# STM32-PROX.net
KiCad netlist of a schematic drawn in EAGLE
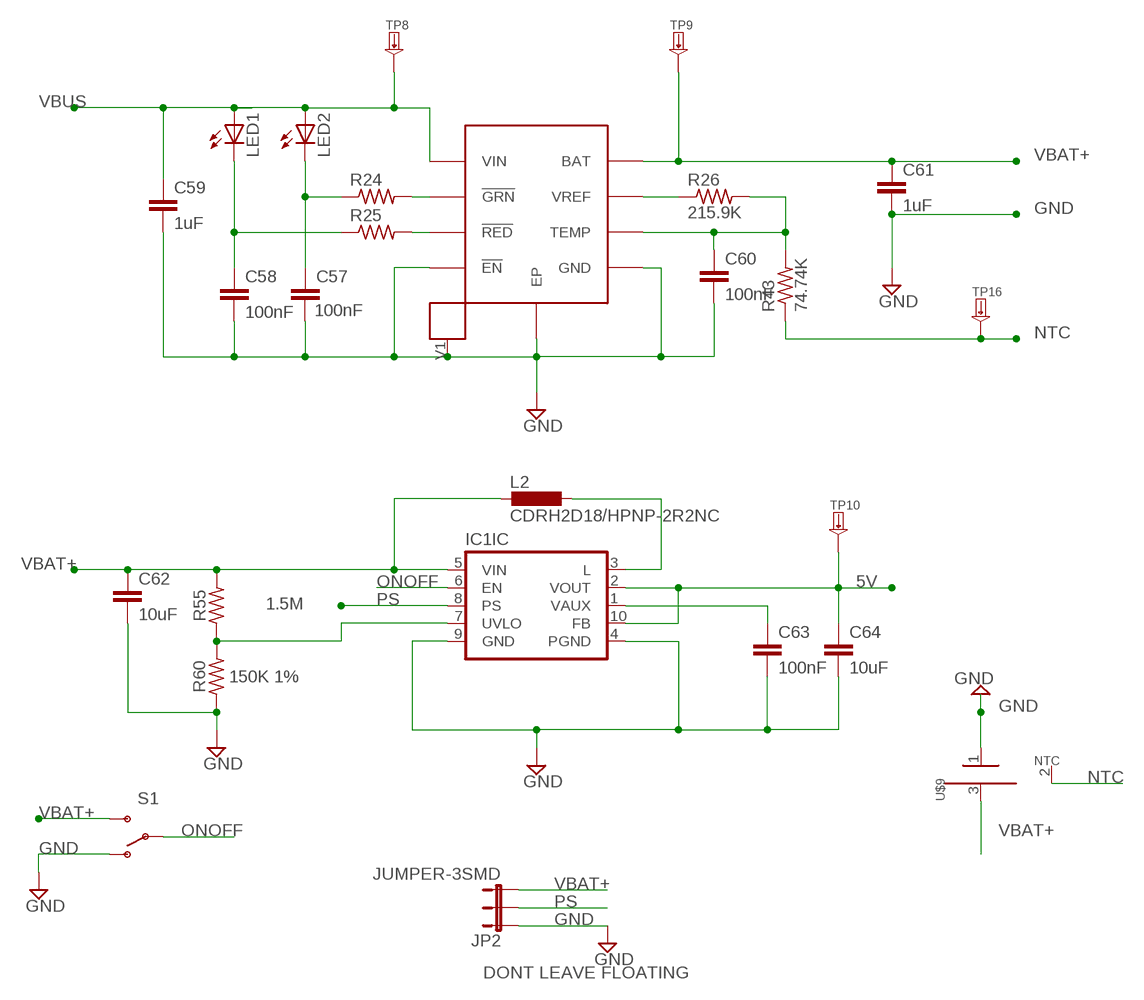
[diagram p0: schematic, sheet 1]
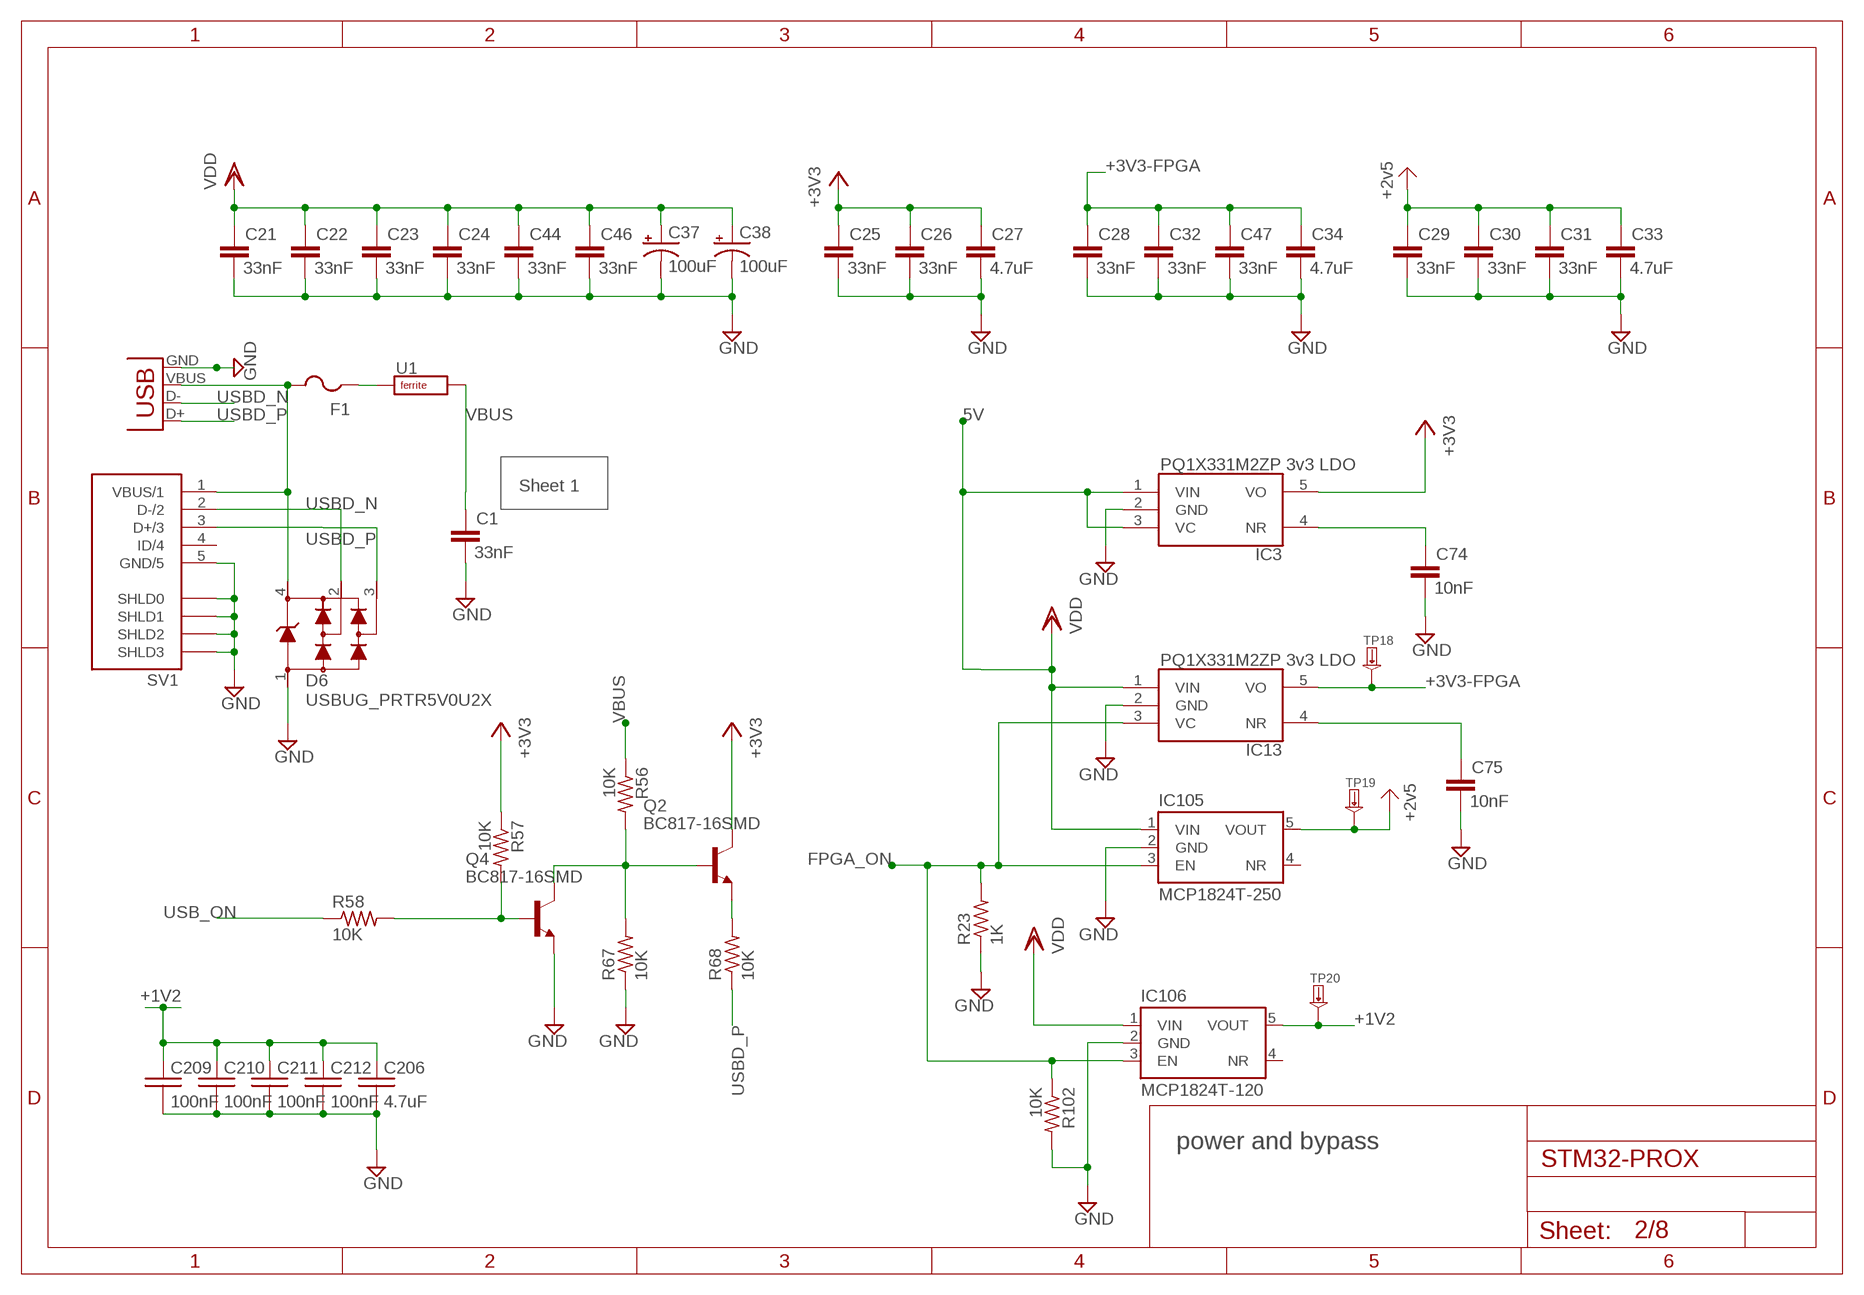
[diagram p1: schematic, sheet 2]
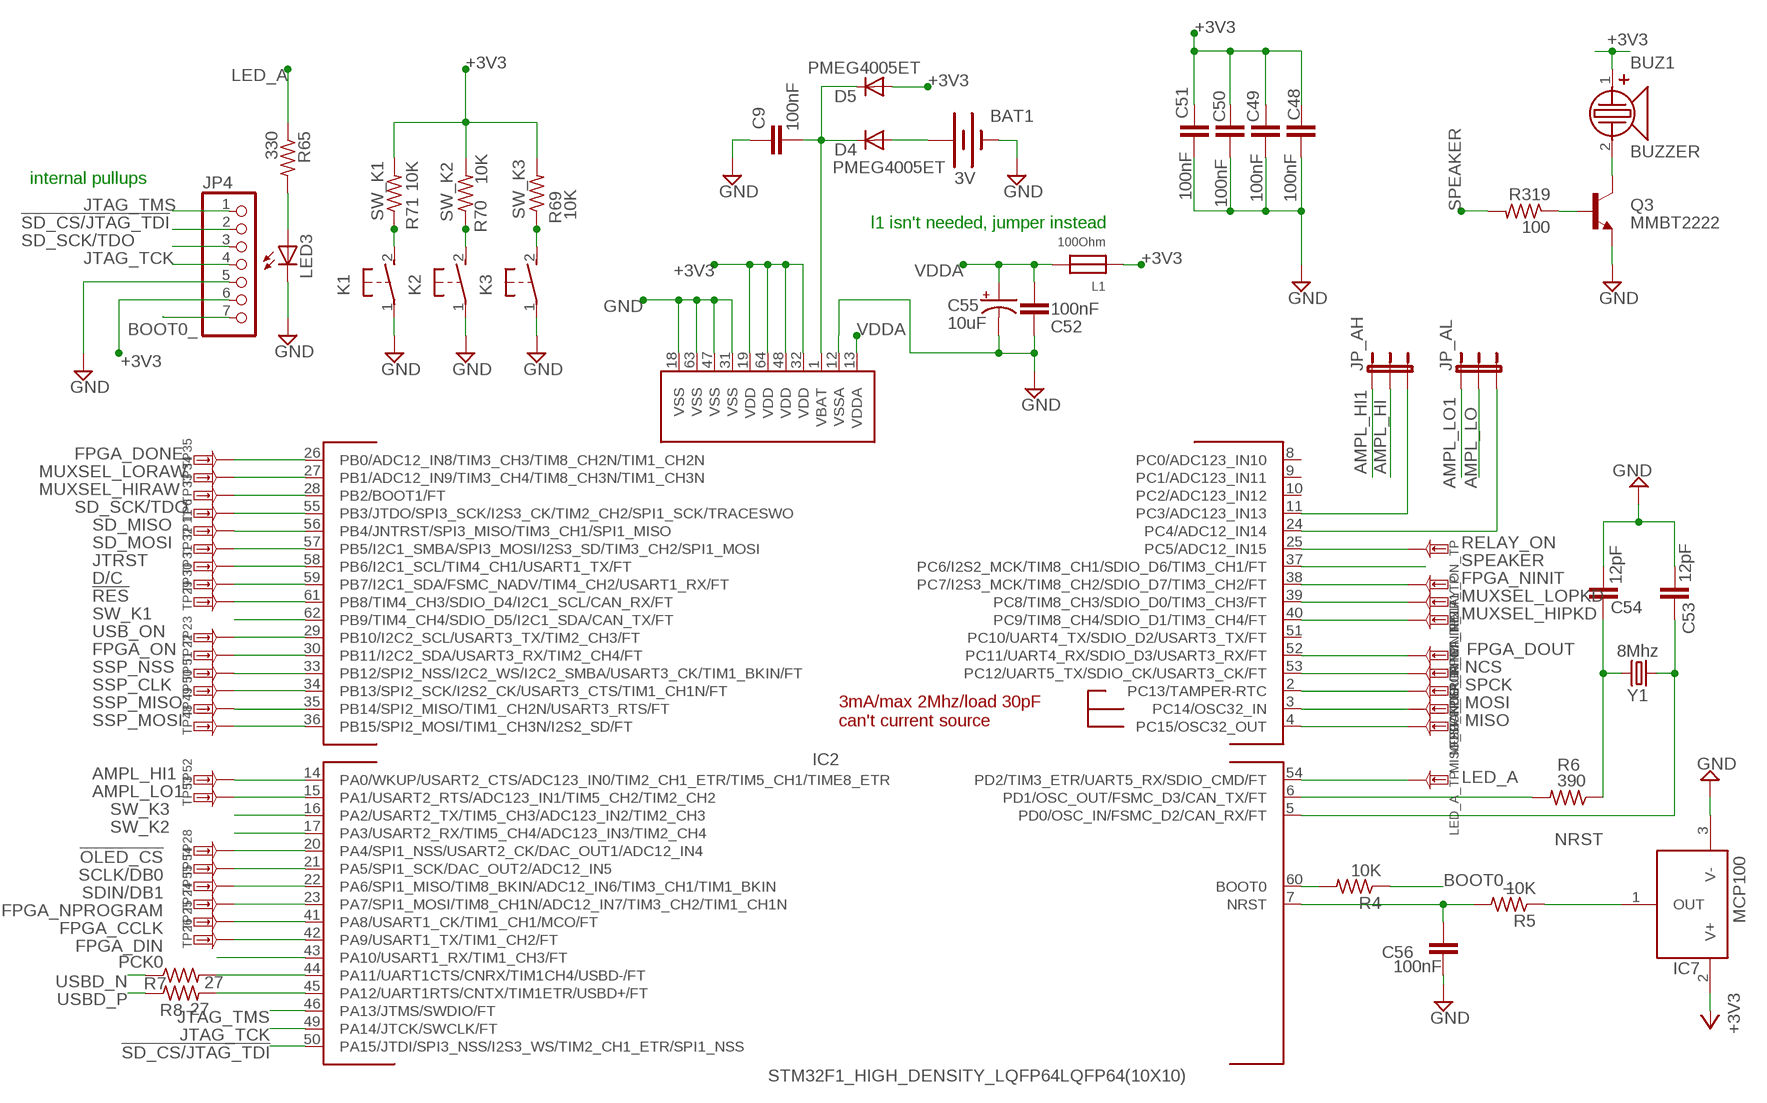
[diagram p2: schematic, sheet 3]
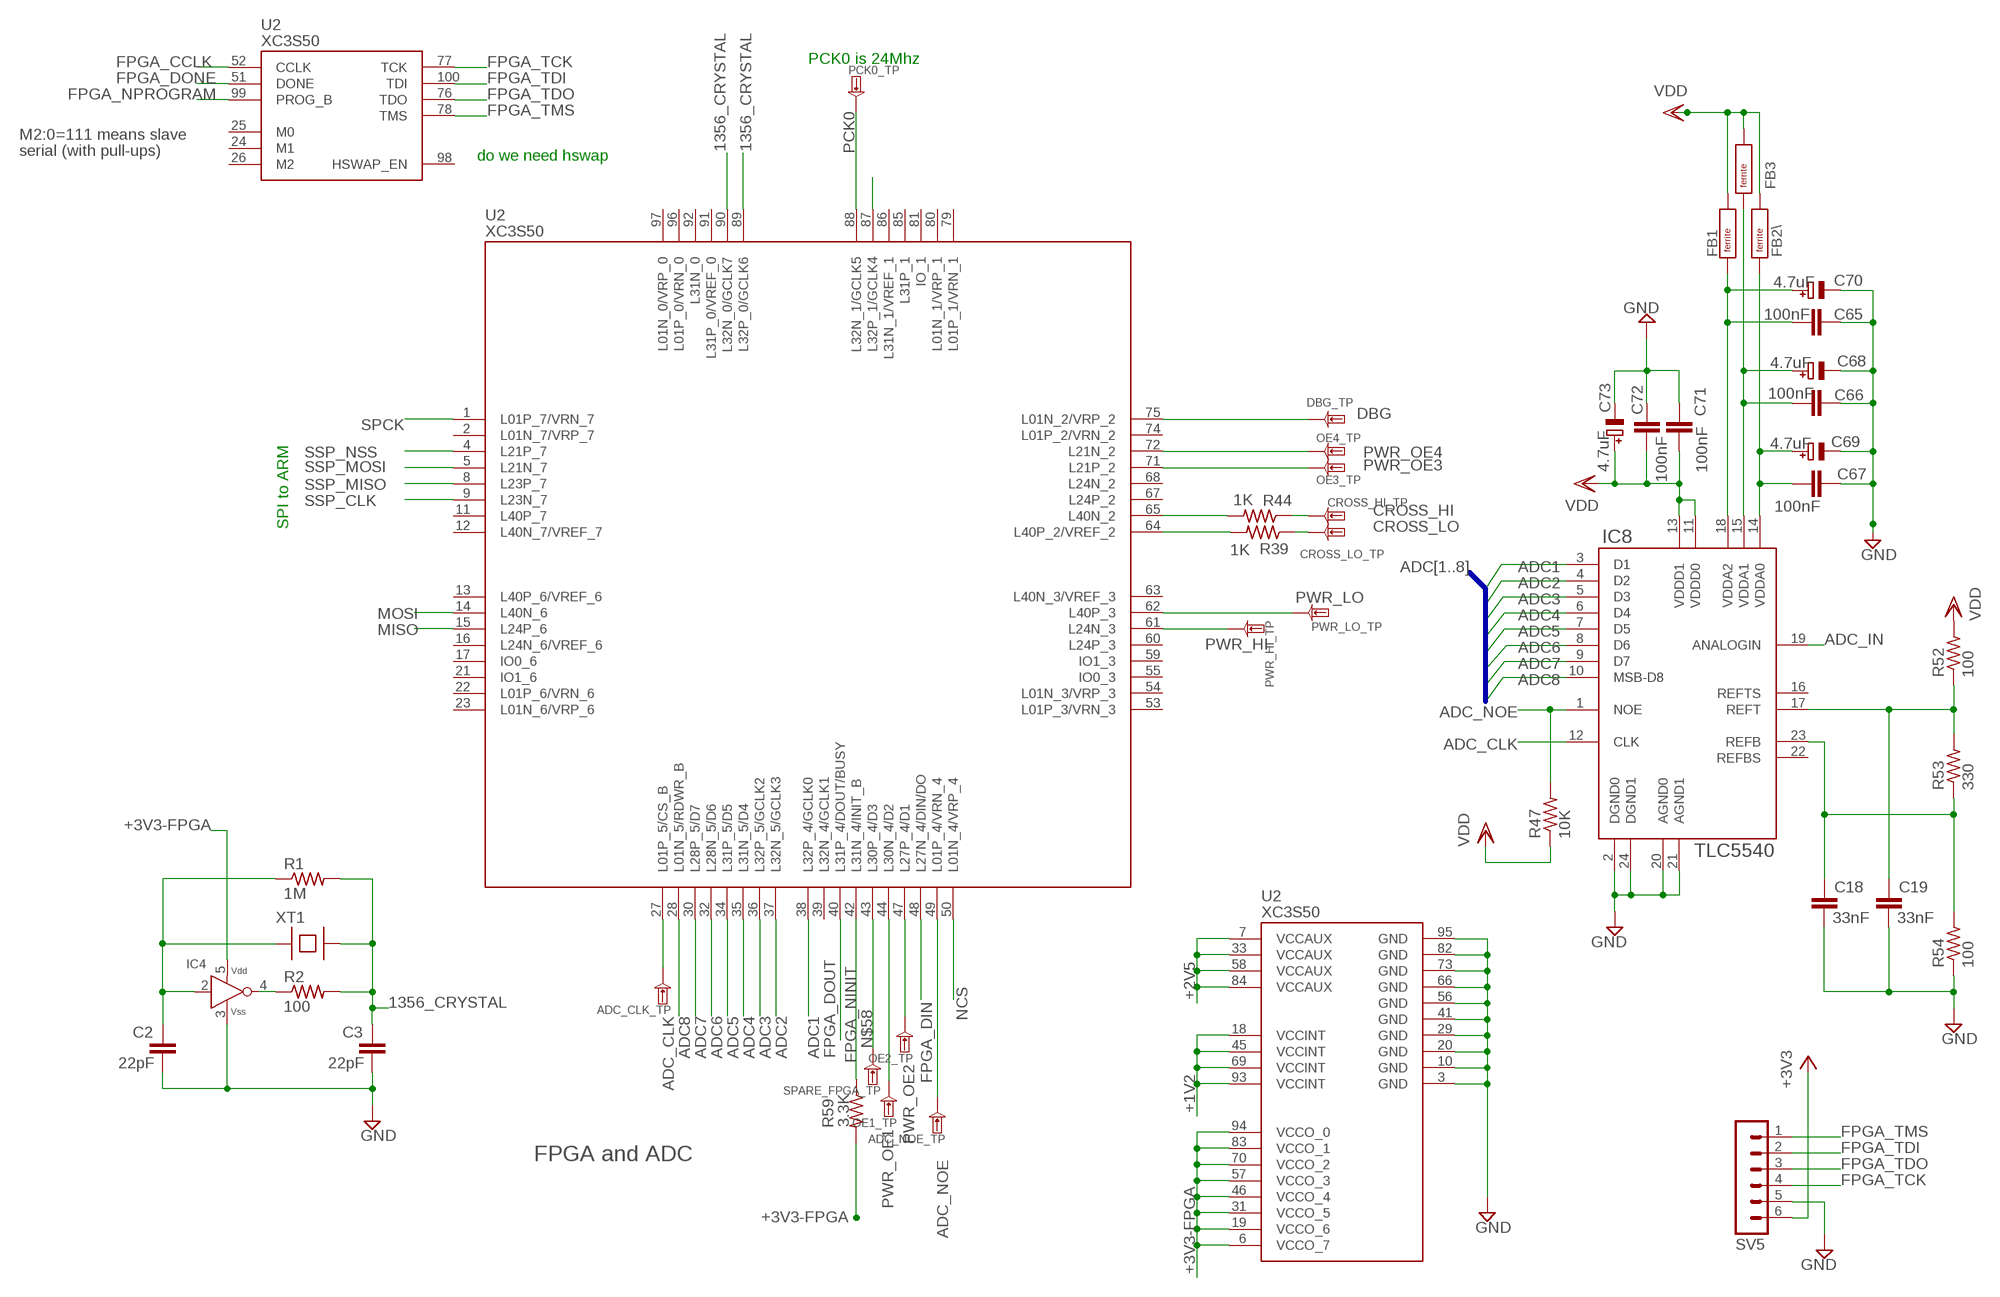
[diagram p3: schematic, sheet 4]
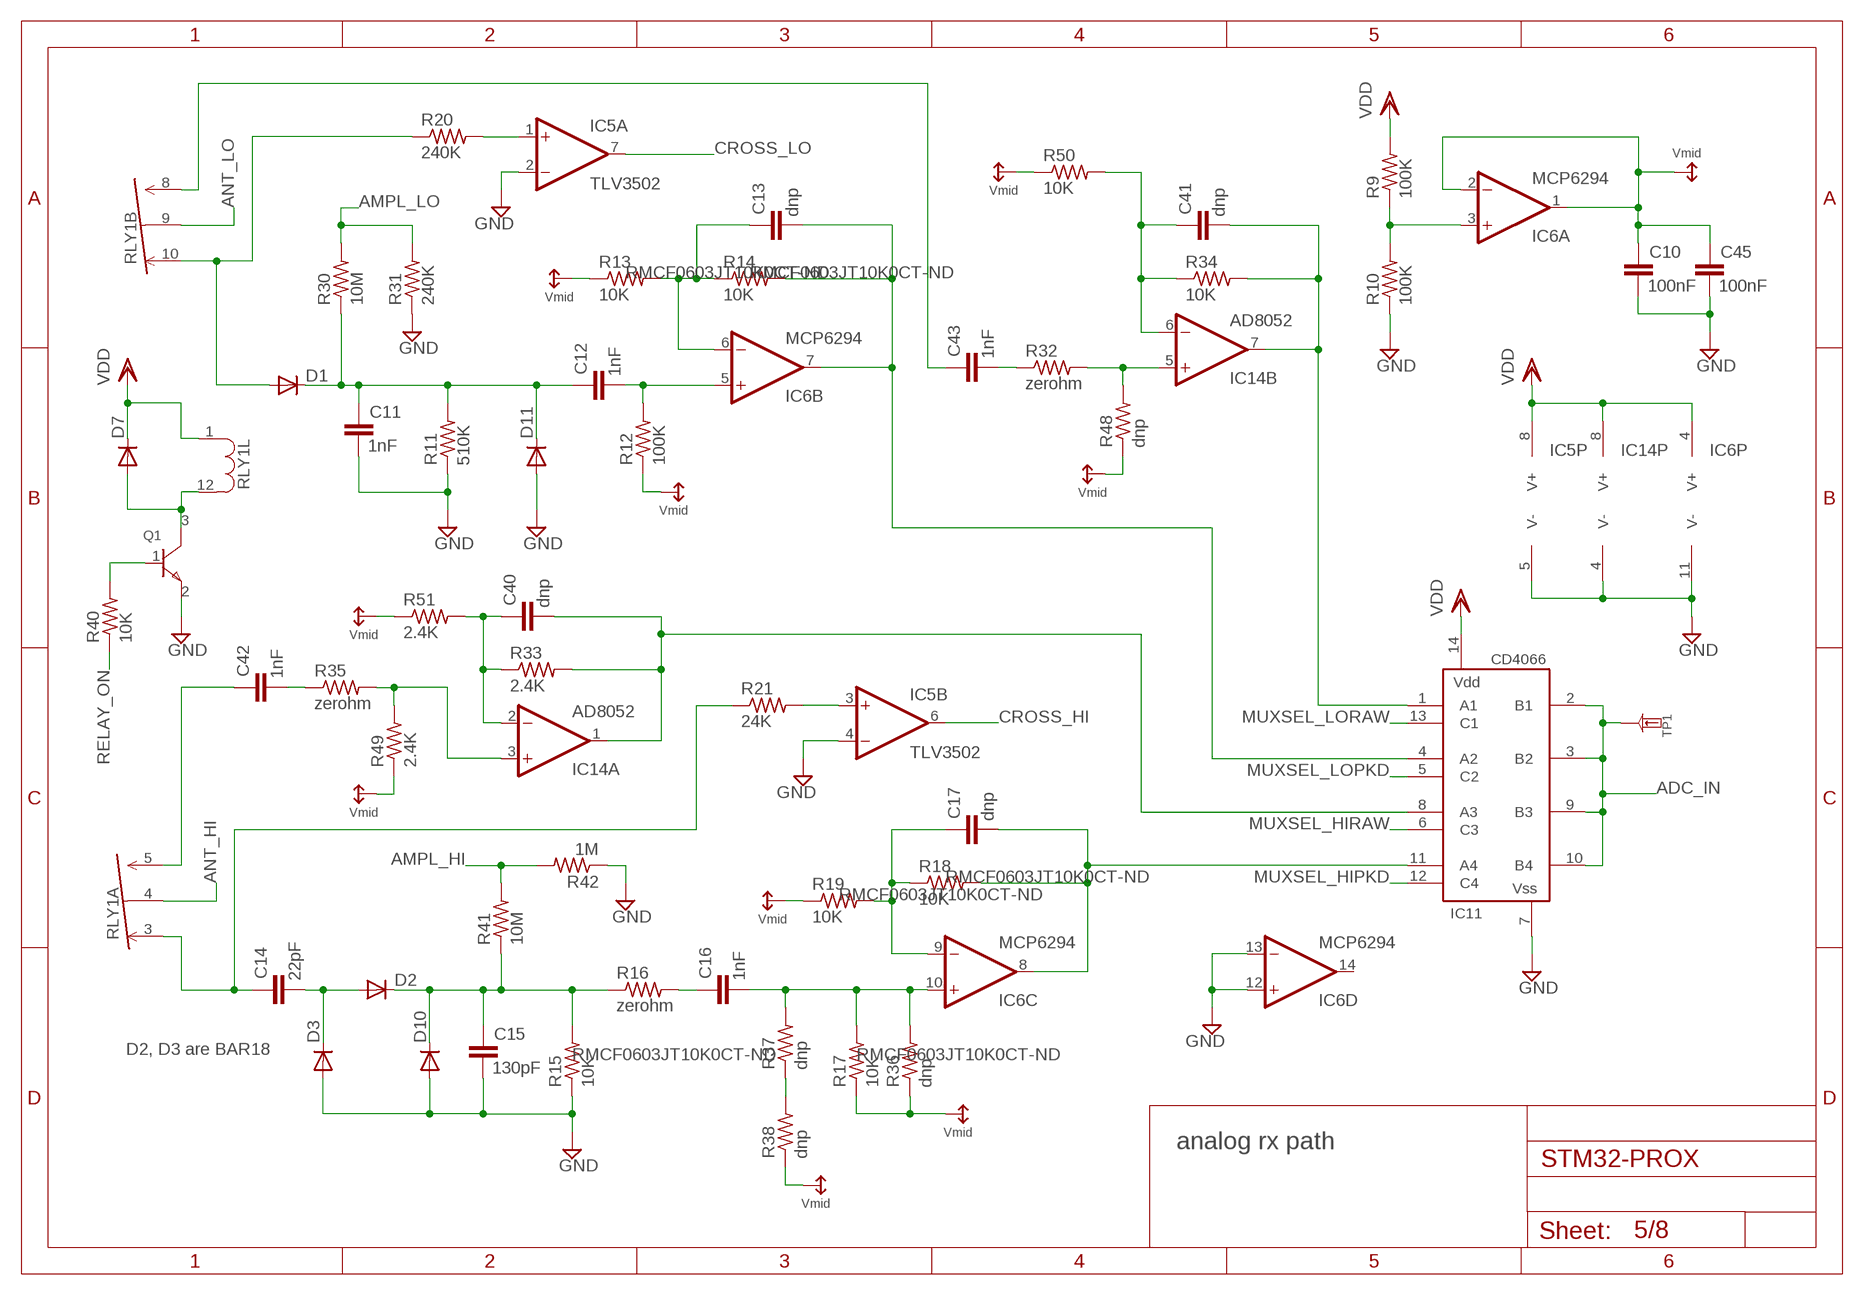
[diagram p4: schematic, sheet 5]
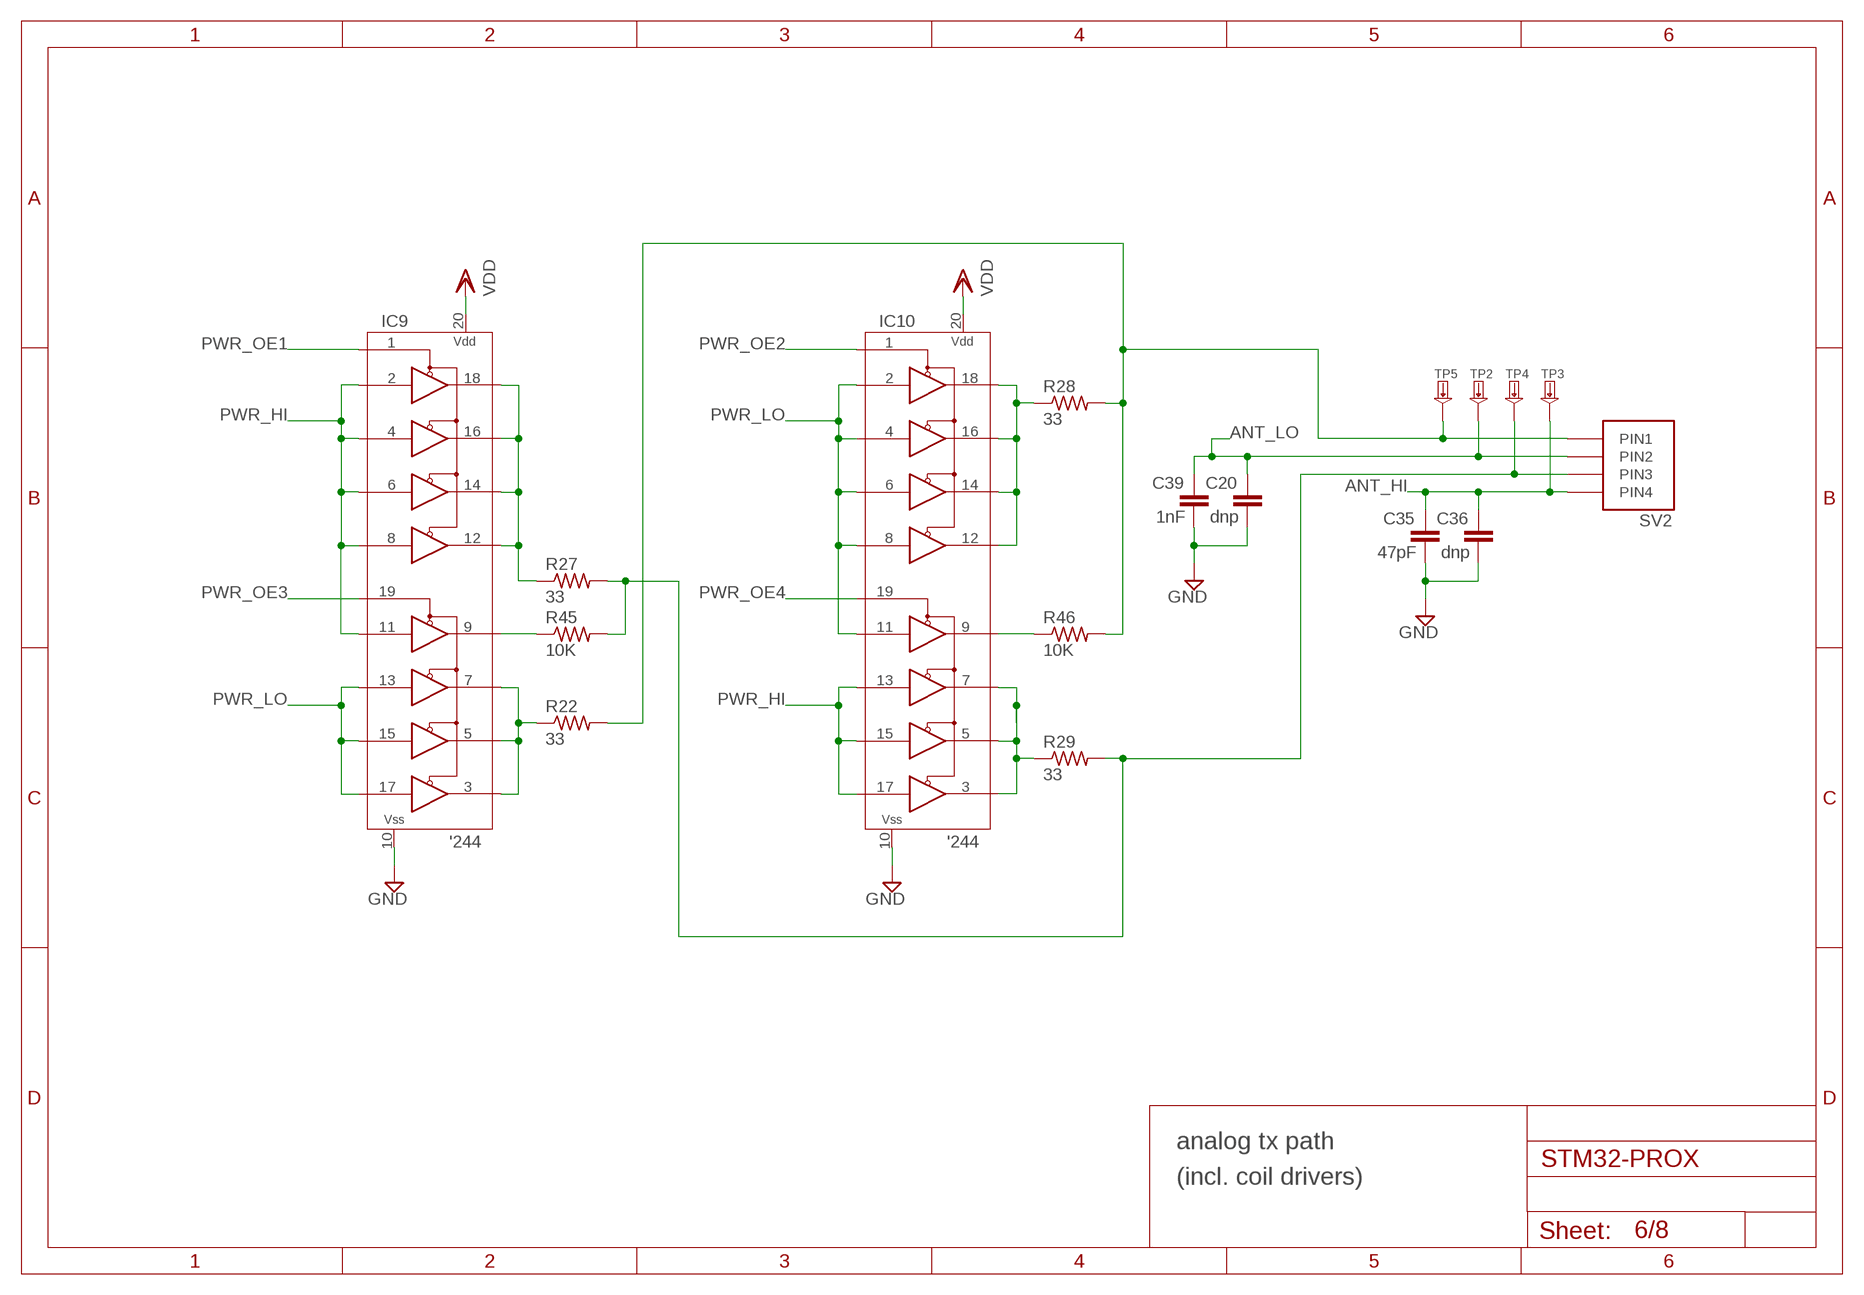
[diagram p5: schematic, sheet 6]
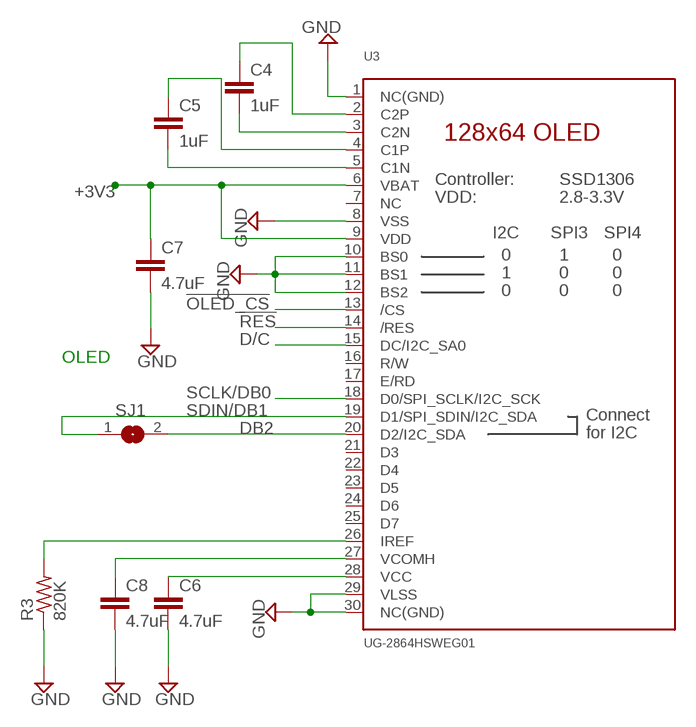
[diagram p6: schematic, sheet 7]
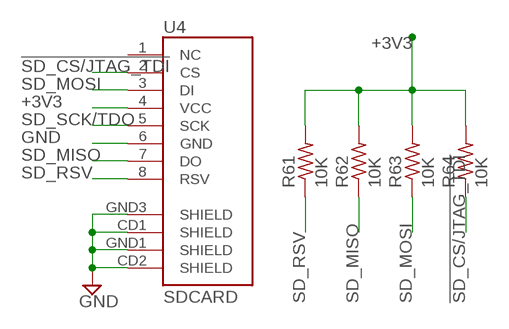
[diagram p7: schematic, sheet 8]

(export (version "E")
  (design (tool "Eeschema 10.0.6"))
  (components
    (comp (ref "ADC_CLK_TP")
      (value "TESTPAD")
      (footprint "eagle-import:SMD-TESTPOINT")
      (libsource (lib "eagle-import") (part "TESTPAD"))
    )
    (comp (ref "ADC_NOE_TP")
      (value "TESTPAD")
      (footprint "eagle-import:SMD-TESTPOINT")
      (libsource (lib "eagle-import") (part "TESTPAD"))
    )
    (comp (ref "C2")
      (value "22pF")
      (footprint "eagle-import:RLC_0603")
      (fields (field (name "MPN") "C1608C0G1H220J080AA"))
      (libsource (lib "eagle-import") (part "CAPACITORRLC_0603"))
    )
    (comp (ref "C3")
      (value "22pF")
      (footprint "eagle-import:RLC_0603")
      (fields (field (name "MPN") "C1608C0G1H220J080AA"))
      (libsource (lib "eagle-import") (part "CAPACITORRLC_0603"))
    )
    (comp (ref "C18")
      (value "33nF")
      (footprint "eagle-import:RLC_0603")
      (fields (field (name "MPN") "CC0603KRX7R9BB333"))
      (libsource (lib "eagle-import") (part "CAPACITORRLC_0603"))
    )
    (comp (ref "C19")
      (value "33nF")
      (footprint "eagle-import:RLC_0603")
      (fields (field (name "MPN") "CC0603KRX7R9BB333"))
      (libsource (lib "eagle-import") (part "CAPACITORRLC_0603"))
    )
    (comp (ref "C65")
      (value "100nF")
      (footprint "eagle-import:RLC_0603")
      (fields (field (name "MPN") "CC0603KRX7R9BB333"))
      (libsource (lib "eagle-import") (part "CAPACITORRLC_0603"))
    )
    (comp (ref "C66")
      (value "100nF")
      (footprint "eagle-import:RLC_0603")
      (fields (field (name "MPN") "CC0603KRX7R9BB333"))
      (libsource (lib "eagle-import") (part "CAPACITORRLC_0603"))
    )
    (comp (ref "C67")
      (value "100nF")
      (footprint "eagle-import:RLC_0603")
      (fields (field (name "MPN") "CC0603KRX7R9BB333"))
      (libsource (lib "eagle-import") (part "CAPACITORRLC_0603"))
    )
    (comp (ref "C68")
      (value "4.7uF")
      (footprint "eagle-import:EIA3216-18_A-R")
      (libsource (lib "eagle-import") (part "CAP_TANTALUMA/3216_REFLOW"))
    )
    (comp (ref "C69")
      (value "4.7uF")
      (footprint "eagle-import:EIA3216-18_A-R")
      (libsource (lib "eagle-import") (part "CAP_TANTALUMA/3216_REFLOW"))
    )
    (comp (ref "C70")
      (value "4.7uF")
      (footprint "eagle-import:EIA3216-18_A-R")
      (libsource (lib "eagle-import") (part "CAP_TANTALUMA/3216_REFLOW"))
    )
    (comp (ref "C71")
      (value "100nF")
      (footprint "eagle-import:RLC_0603")
      (fields (field (name "MPN") "CC0603KRX7R9BB333"))
      (libsource (lib "eagle-import") (part "CAPACITORRLC_0603"))
    )
    (comp (ref "C72")
      (value "100nF")
      (footprint "eagle-import:RLC_0603")
      (fields (field (name "MPN") "CC0603KRX7R9BB333"))
      (libsource (lib "eagle-import") (part "CAPACITORRLC_0603"))
    )
    (comp (ref "C73")
      (value "4.7uF")
      (footprint "eagle-import:EIA3216-18_A-R")
      (libsource (lib "eagle-import") (part "CAP_TANTALUMA/3216_REFLOW"))
    )
    (comp (ref "CROSS_HI_TP")
      (value "TESTPAD")
      (footprint "eagle-import:SMD-TESTPOINT")
      (libsource (lib "eagle-import") (part "TESTPAD"))
    )
    (comp (ref "CROSS_LO_TP")
      (value "TESTPAD")
      (footprint "eagle-import:SMD-TESTPOINT")
      (libsource (lib "eagle-import") (part "TESTPAD"))
    )
    (comp (ref "DBG_TP")
      (value "TESTPAD")
      (footprint "eagle-import:SMD-TESTPOINT")
      (libsource (lib "eagle-import") (part "TESTPAD"))
    )
    (comp (ref "FB1")
      (value "FERRITERLC_0603")
      (footprint "eagle-import:RLC_0603")
      (fields (field (name "PARTNO") "BLM31PG601SN1L"))
      (libsource (lib "eagle-import") (part "FERRITERLC_0603"))
    )
    (comp (ref "FB2\\")
      (value "FERRITERLC_0603")
      (footprint "eagle-import:RLC_0603")
      (fields (field (name "PARTNO") "BLM31PG601SN1L"))
      (libsource (lib "eagle-import") (part "FERRITERLC_0603"))
    )
    (comp (ref "FB3")
      (value "FERRITERLC_0603")
      (footprint "eagle-import:RLC_0603")
      (fields (field (name "PARTNO") "BLM31PG601SN1L"))
      (libsource (lib "eagle-import") (part "FERRITERLC_0603"))
    )
    (comp (ref "IC4")
      (value "HCU-INVERTER")
      (footprint "eagle-import:SMV-5")
      (fields (field (name "MF") "NC7SZ04M5X"))
      (libsource (lib "eagle-import") (part "HCU-INVERTER"))
    )
    (comp (ref "IC8")
      (value "TLC5540")
      (footprint "eagle-import:TSSOP-24")
      (fields (field (name "MPN") "TLC5540IPW"))
      (libsource (lib "eagle-import") (part "TLC5540"))
    )
    (comp (ref "OE1_TP")
      (value "TESTPAD")
      (footprint "eagle-import:SMD-TESTPOINT")
      (libsource (lib "eagle-import") (part "TESTPAD"))
    )
    (comp (ref "OE2_TP")
      (value "TESTPAD")
      (footprint "eagle-import:SMD-TESTPOINT")
      (libsource (lib "eagle-import") (part "TESTPAD"))
    )
    (comp (ref "OE3_TP")
      (value "TESTPAD")
      (footprint "eagle-import:SMD-TESTPOINT")
      (libsource (lib "eagle-import") (part "TESTPAD"))
    )
    (comp (ref "OE4_TP")
      (value "TESTPAD")
      (footprint "eagle-import:SMD-TESTPOINT")
      (libsource (lib "eagle-import") (part "TESTPAD"))
    )
    (comp (ref "PCK0_TP")
      (value "TESTPAD")
      (footprint "eagle-import:SMD-TESTPOINT")
      (libsource (lib "eagle-import") (part "TESTPAD"))
    )
    (comp (ref "PWR_HI_TP")
      (value "TESTPAD")
      (footprint "eagle-import:SMD-TESTPOINT")
      (libsource (lib "eagle-import") (part "TESTPAD"))
    )
    (comp (ref "PWR_LO_TP")
      (value "TESTPAD")
      (footprint "eagle-import:SMD-TESTPOINT")
      (libsource (lib "eagle-import") (part "TESTPAD"))
    )
    (comp (ref "R1")
      (value "1M")
      (footprint "eagle-import:RLC_0603")
      (fields (field (name "MPN") "RC0603JR-071ML"))
      (libsource (lib "eagle-import") (part "RESISTORRLC_0603"))
    )
    (comp (ref "R2")
      (value "100")
      (footprint "eagle-import:RLC_0603")
      (fields (field (name "MPN") "RMCF0603JT100R"))
      (libsource (lib "eagle-import") (part "RESISTORRLC_0603"))
    )
    (comp (ref "R39")
      (value "1K")
      (footprint "eagle-import:RLC_0603")
      (fields (field (name "MPN") "RMCF0603JT1K00"))
      (libsource (lib "eagle-import") (part "RESISTORRLC_0603"))
    )
    (comp (ref "R44")
      (value "1K")
      (footprint "eagle-import:RLC_0603")
      (fields (field (name "MPN") "RMCF0603JT1K00"))
      (libsource (lib "eagle-import") (part "RESISTORRLC_0603"))
    )
    (comp (ref "R47")
      (value "10K")
      (footprint "eagle-import:RLC_0603")
      (fields (field (name "MPN") "RMCF0603JT10K0"))
      (libsource (lib "eagle-import") (part "RESISTORRLC_0603"))
    )
    (comp (ref "R52")
      (value "100")
      (footprint "eagle-import:RLC_0603")
      (fields (field (name "MPN") "RMCF0603JT100R"))
      (libsource (lib "eagle-import") (part "RESISTORRLC_0603"))
    )
    (comp (ref "R53")
      (value "330")
      (footprint "eagle-import:RLC_0603")
      (fields (field (name "MPN") "RMCF0603JT330R"))
      (libsource (lib "eagle-import") (part "RESISTORRLC_0603"))
    )
    (comp (ref "R54")
      (value "100")
      (footprint "eagle-import:RLC_0603")
      (fields (field (name "MPN") "RMCF0603JT100R"))
      (libsource (lib "eagle-import") (part "RESISTORRLC_0603"))
    )
    (comp (ref "R59")
      (value "3.3K")
      (footprint "eagle-import:RLC_0603")
      (fields (field (name "MPN") "RMCF0603JT3K30"))
      (libsource (lib "eagle-import") (part "RESISTORRLC_0603"))
    )
    (comp (ref "SPARE_FPGA_TP")
      (value "TESTPAD")
      (footprint "eagle-import:SMD-TESTPOINT")
      (libsource (lib "eagle-import") (part "TESTPAD"))
    )
    (comp (ref "SV5")
      (value "HEADER-MALE-6X1")
      (footprint "eagle-import:HEADER-MALE-6X1-0.100-UNKEYED")
      (libsource (lib "eagle-import") (part "HEADER-MALE-6X1"))
    )
    (comp (ref "U2")
      (value "XC3S50")
      (footprint "eagle-import:VQ100")
      (fields
        (field (name "MPN") "XC3S50-5VQ100C (not on bom)")
        (field (name "OC_NEWARK") "unknown")
        (field (name "PARTNO") "XC3S50-5VQ100C (not on bom)")
      )
      (libsource (lib "eagle-import") (part "XC3S50"))
    )
    (comp (ref "XT1")
      (value "XTAL-SMD-CITIZEN-CS10")
      (footprint "eagle-import:XTAL-SMD-CITIZEN-CS10")
      (fields (field (name "MF") "ABM3-13.560MHZ-B2-T"))
      (libsource (lib "eagle-import") (part "XTAL-SMD-CITIZEN-CS10"))
    )
    (comp (ref "C20")
      (value "dnp")
      (footprint "eagle-import:RLC_0603")
      (libsource (lib "eagle-import") (part "CAPACITORRLC_0603"))
    )
    (comp (ref "C35")
      (value "47pF")
      (footprint "eagle-import:RLC_0603")
      (fields (field (name "MPN") "CL10C470JB8NNNC"))
      (libsource (lib "eagle-import") (part "CAPACITORRLC_0603"))
    )
    (comp (ref "C36")
      (value "dnp")
      (footprint "eagle-import:RLC_0603")
      (libsource (lib "eagle-import") (part "CAPACITORRLC_0603"))
    )
    (comp (ref "C39")
      (value "1nF")
      (footprint "eagle-import:RLC_0603")
      (fields (field (name "MPN") "GRM188R71H102KA01D"))
      (libsource (lib "eagle-import") (part "CAPACITORRLC_0603"))
    )
    (comp (ref "IC9")
      (value "74XX244")
      (footprint "eagle-import:TSSOP-20")
      (fields (field (name "MF") "74AC244TTR"))
      (libsource (lib "eagle-import") (part "74XX244-OCTAL-TRISTATE-BUFFERS"))
    )
    (comp (ref "IC10")
      (value "74XX244")
      (footprint "eagle-import:TSSOP-20")
      (fields (field (name "MF") "74AC244TTR"))
      (libsource (lib "eagle-import") (part "74XX244-OCTAL-TRISTATE-BUFFERS"))
    )
    (comp (ref "R22")
      (value "33")
      (footprint "eagle-import:RLC_0603")
      (fields (field (name "MPN") "RC0603JR-0733RL"))
      (libsource (lib "eagle-import") (part "RESISTORRLC_0603"))
    )
    (comp (ref "R27")
      (value "33")
      (footprint "eagle-import:RLC_0603")
      (fields (field (name "MPN") "RC0603JR-0733RL"))
      (libsource (lib "eagle-import") (part "RESISTORRLC_0603"))
    )
    (comp (ref "R28")
      (value "33")
      (footprint "eagle-import:RLC_0603")
      (fields (field (name "MPN") "RC0603JR-0733RL"))
      (libsource (lib "eagle-import") (part "RESISTORRLC_0603"))
    )
    (comp (ref "R29")
      (value "33")
      (footprint "eagle-import:RLC_0603")
      (fields (field (name "MPN") "RC0603JR-0733RL"))
      (libsource (lib "eagle-import") (part "RESISTORRLC_0603"))
    )
    (comp (ref "R45")
      (value "10K")
      (footprint "eagle-import:RLC_0603")
      (fields (field (name "MPN") "RMCF0603JT10K0"))
      (libsource (lib "eagle-import") (part "RESISTORRLC_0603"))
    )
    (comp (ref "R46")
      (value "10K")
      (footprint "eagle-import:RLC_0603")
      (fields (field (name "MPN") "RMCF0603JT10K0"))
      (libsource (lib "eagle-import") (part "RESISTORRLC_0603"))
    )
    (comp (ref "SV2")
      (value "HIROSE-MQ172-4POS")
      (footprint "eagle-import:HIROSE-MQ172-4POS")
      (fields (field (name "MF") "MQ172X-4PA(66)"))
      (libsource (lib "eagle-import") (part "HIROSE-MQ172-4POS"))
    )
    (comp (ref "TP2")
      (value "TESTPADKEYSTONE-SMD")
      (footprint "eagle-import:KEYSTONE-SMD-TESTPOINT-5015")
      (libsource (lib "eagle-import") (part "TESTPADKEYSTONE-SMD"))
    )
    (comp (ref "TP3")
      (value "TESTPADKEYSTONE-SMD")
      (footprint "eagle-import:KEYSTONE-SMD-TESTPOINT-5015")
      (libsource (lib "eagle-import") (part "TESTPADKEYSTONE-SMD"))
    )
    (comp (ref "TP4")
      (value "TESTPADKEYSTONE-SMD")
      (footprint "eagle-import:KEYSTONE-SMD-TESTPOINT-5015")
      (libsource (lib "eagle-import") (part "TESTPADKEYSTONE-SMD"))
    )
    (comp (ref "TP5")
      (value "TESTPADKEYSTONE-SMD")
      (footprint "eagle-import:KEYSTONE-SMD-TESTPOINT-5015")
      (libsource (lib "eagle-import") (part "TESTPADKEYSTONE-SMD"))
    )
    (comp (ref "C4")
      (value "1uF")
      (footprint "eagle-import:0603-CAP")
      (fields (field (name "MPN") "CC0805ZRY5V8BB105"))
      (libsource (lib "eagle-import") (part "CAP0603-CAP"))
    )
    (comp (ref "C5")
      (value "1uF")
      (footprint "eagle-import:0603-CAP")
      (fields (field (name "MPN") "CC0805ZRY5V8BB105"))
      (libsource (lib "eagle-import") (part "CAP0603-CAP"))
    )
    (comp (ref "C6")
      (value "4.7uF")
      (footprint "eagle-import:0603-CAP")
      (fields (field (name "MPN") "CL21A475KOFNNNE"))
      (libsource (lib "eagle-import") (part "CAP0603-CAP"))
    )
    (comp (ref "C7")
      (value "4.7uF")
      (footprint "eagle-import:0603-CAP")
      (fields (field (name "MPN") "CL21A475KOFNNNE"))
      (libsource (lib "eagle-import") (part "CAP0603-CAP"))
    )
    (comp (ref "C8")
      (value "4.7uF")
      (footprint "eagle-import:0603-CAP")
      (fields (field (name "MPN") "CL21A475KOFNNNE"))
      (libsource (lib "eagle-import") (part "CAP0603-CAP"))
    )
    (comp (ref "R3")
      (value "820K")
      (footprint "eagle-import:RLC_0603")
      (fields (field (name "MPN") "RC0603JR-07820KL"))
      (libsource (lib "eagle-import") (part "RESISTORRLC_0603"))
    )
    (comp (ref "SJ1")
      (value "SOLDERJUMPERREFLOW")
      (footprint "eagle-import:SOLDERJUMPER_REFLOW")
      (fields (field (name "MPN") "NONE"))
      (libsource (lib "eagle-import") (part "SOLDERJUMPERREFLOW"))
    )
    (comp (ref "U3")
      (value "UG-2864HSWEG01")
      (footprint "eagle-import:MICROBUILDER_UG-2864HSWEG01_0.96IN_WRAPAROUND")
      (libsource (lib "eagle-import") (part "MICROBUILDER_DISP_OLED_UG-2864HSWEG010.96{dblquote}"))
    )
    (comp (ref "C57")
      (value "100nF")
      (footprint "eagle-import:RLC_0603")
      (fields (field (name "MPN") "CL10B104KO8NNNC"))
      (libsource (lib "eagle-import") (part "CAPACITORRLC_0603"))
    )
    (comp (ref "C58")
      (value "100nF")
      (footprint "eagle-import:SPARKFUN_0603-CAP")
      (fields (field (name "MPN") "CL10B104KO8NNNC"))
      (libsource (lib "eagle-import") (part "SPARKFUN_CAP0603-CAP"))
    )
    (comp (ref "C59")
      (value "1uF")
      (footprint "eagle-import:SPARKFUN_0603-CAP")
      (fields (field (name "MPN") "CC0603ZRY5V7BB105"))
      (libsource (lib "eagle-import") (part "SPARKFUN_CAP0603-CAP"))
    )
    (comp (ref "C60")
      (value "100nF")
      (footprint "eagle-import:SPARKFUN_0603-CAP")
      (fields (field (name "MPN") "CL10B104KO8NNNC"))
      (libsource (lib "eagle-import") (part "SPARKFUN_CAP0603-CAP"))
    )
    (comp (ref "C61")
      (value "1uF")
      (footprint "eagle-import:SPARKFUN_0603-CAP")
      (fields (field (name "MPN") "CC0603ZRY5V7BB105"))
      (libsource (lib "eagle-import") (part "SPARKFUN_CAP0603-CAP"))
    )
    (comp (ref "C62")
      (value "10uF")
      (footprint "eagle-import:SPARKFUN_0603-CAP")
      (fields (field (name "MPN") "C1608X5R1C106M080AB"))
      (libsource (lib "eagle-import") (part "SPARKFUN_CAP0603-CAP"))
    )
    (comp (ref "C63")
      (value "100nF")
      (footprint "eagle-import:SPARKFUN_0603-CAP")
      (fields (field (name "MPN") "CL10B104KO8NNNC"))
      (libsource (lib "eagle-import") (part "SPARKFUN_CAP0603-CAP"))
    )
    (comp (ref "C64")
      (value "10uF")
      (footprint "eagle-import:SPARKFUN_0603-CAP")
      (fields (field (name "MPN") "C1608X5R1C106M080AB"))
      (libsource (lib "eagle-import") (part "SPARKFUN_CAP0603-CAP"))
    )
    (comp (ref "IC1")
      (value "IC_TPS6120XQFN10")
      (footprint "eagle-import:QFN-10")
      (fields (field (name "MPN") "TPS61202DRCT"))
      (libsource (lib "eagle-import") (part "IC_TPS6120XQFN10"))
    )
    (comp (ref "JP2")
      (value "JUMPER-3SMD")
      (footprint "eagle-import:SJ_3")
      (fields (field (name "MPN") "NONE"))
      (libsource (lib "eagle-import") (part "JUMPER-3SMD"))
    )
    (comp (ref "L2")
      (value "CDRH2D18/HPNP-2R2NC")
      (footprint "eagle-import:CDRH2D18")
      (libsource (lib "eagle-import") (part "CDRH2D18"))
    )
    (comp (ref "LED1")
      (value "LED_LEDSML0603")
      (footprint "eagle-import:LED_SML0603")
      (fields (field (name "MF") "LG Q971-KN-1"))
      (libsource (lib "eagle-import") (part "LED_LEDSML0603"))
    )
    (comp (ref "LED2")
      (value "LED_LEDSML0603")
      (footprint "eagle-import:LED_SML0603")
      (fields (field (name "MF") "LS Q971-KN-1"))
      (libsource (lib "eagle-import") (part "LED_LEDSML0603"))
    )
    (comp (ref "R24")
      (value "RESISTORRLC_0603")
      (footprint "eagle-import:RLC_0603")
      (libsource (lib "eagle-import") (part "RESISTORRLC_0603"))
    )
    (comp (ref "R25")
      (value "RESISTORRLC_0603")
      (footprint "eagle-import:RLC_0603")
      (libsource (lib "eagle-import") (part "RESISTORRLC_0603"))
    )
    (comp (ref "R26")
      (value "215.9K")
      (footprint "eagle-import:RLC_0603")
      (fields (field (name "MPN") "CRCW0603215KFKEA"))
      (libsource (lib "eagle-import") (part "RESISTORRLC_0603"))
    )
    (comp (ref "R43")
      (value "74.74K")
      (footprint "eagle-import:RLC_0603")
      (fields (field (name "MPN") "RMCF0603JT75K0"))
      (libsource (lib "eagle-import") (part "RESISTORRLC_0603"))
    )
    (comp (ref "R55")
      (value "1.5M")
      (footprint "eagle-import:RLC_0603")
      (fields (field (name "MPN") "ESR03EZPJ155") (field (name "TOLERANCE") "5%"))
      (libsource (lib "eagle-import") (part "RESISTORRLC_0603"))
    )
    (comp (ref "R60")
      (value "150K 1%")
      (footprint "eagle-import:RLC_0603")
      (fields (field (name "MPN") "ESR03EZPF1503") (field (name "TOLERANCE") "1%"))
      (libsource (lib "eagle-import") (part "RESISTORRLC_0603"))
    )
    (comp (ref "S1")
      (value "SWITCH-SPDT-SMD-A")
      (footprint "eagle-import:SWITCH-SPST-SMD-A")
      (libsource (lib "eagle-import") (part "SWITCH-SPDT-SMD-A"))
    )
    (comp (ref "TP8")
      (value "TESTPAD0.7MM-ROUND-DRILLED")
      (footprint "eagle-import:TESTPAD-PTH-0.7MM")
      (fields (field (name "MPN") "NONE"))
      (libsource (lib "eagle-import") (part "TESTPAD0.7MM-ROUND-DRILLED"))
    )
    (comp (ref "TP9")
      (value "TESTPADKEYSTONE-SMD")
      (footprint "eagle-import:--MERGED_KEYSTONE-SMD-TESTPOINT-5015")
      (fields (field (name "MPN") "NONE"))
      (libsource (lib "eagle-import") (part "--MERGED_TESTPADKEYSTONE-SMD"))
    )
    (comp (ref "TP10")
      (value "TESTPADKEYSTONE-SMD")
      (footprint "eagle-import:--MERGED_KEYSTONE-SMD-TESTPOINT-5015")
      (fields (field (name "MPN") "NONE"))
      (libsource (lib "eagle-import") (part "--MERGED_TESTPADKEYSTONE-SMD"))
    )
    (comp (ref "TP16")
      (value "TESTPAD")
      (footprint "eagle-import:SMD-TESTPOINT")
      (libsource (lib "eagle-import") (part "TESTPAD"))
    )
    (comp (ref "U$7")
      (value "MC34674")
      (footprint "eagle-import:UDFN-EP")
      (fields
        (field (name "DIGIKEY") "MC34674AEPR2TR-ND")
        (field (name "MF") "MC34674AEPR2")
        (field (name "MOUSER") "841-MC34674AEPR2")
        (field (name "MPN") "MC34674AEPR2")
        (field (name "OC_NEWARK") "unknown")
        (field (name "PARTNO") "MC34674AEPR2")
      )
      (libsource (lib "eagle-import") (part "MC34674"))
    )
    (comp (ref "U$9")
      (value "BATT")
      (footprint "eagle-import:BATT")
      (fields (field (name "MF") "MC34674AEPR2"))
      (libsource (lib "eagle-import") (part "BATT"))
    )
    (comp (ref "BAT1")
      (value "3V")
      (footprint "eagle-import:NSL_SPARKFUN_BATTCON_12MM")
      (fields (field (name "MPN") "BK-885-TR"))
      (libsource (lib "eagle-import") (part "NSL_SPARKFUN_BATTERY12MM"))
    )
    (comp (ref "BUZ1")
      (value "BUZZER")
      (footprint "eagle-import:BUZZER")
      (fields (field (name "MF") "CCV-084B16"))
      (libsource (lib "eagle-import") (part "BUZZER"))
    )
    (comp (ref "C9")
      (value "100nF")
      (footprint "eagle-import:RLC_0603")
      (fields (field (name "MPN") "CL21F104ZBCNNNC"))
      (libsource (lib "eagle-import") (part "CAPACITORRLC_0603"))
    )
    (comp (ref "C48")
      (value "100nF")
      (footprint "eagle-import:RLC_0603")
      (fields (field (name "MPN") "CL21F104ZBCNNNC"))
      (libsource (lib "eagle-import") (part "CAPACITORRLC_0603"))
    )
    (comp (ref "C49")
      (value "100nF")
      (footprint "eagle-import:RLC_0603")
      (fields (field (name "MPN") "CL21F104ZBCNNNC"))
      (libsource (lib "eagle-import") (part "CAPACITORRLC_0603"))
    )
    (comp (ref "C50")
      (value "100nF")
      (footprint "eagle-import:RLC_0603")
      (fields (field (name "MPN") "CL21F104ZBCNNNC"))
      (libsource (lib "eagle-import") (part "CAPACITORRLC_0603"))
    )
    (comp (ref "C51")
      (value "100nF")
      (footprint "eagle-import:RLC_0603")
      (fields (field (name "MPN") "CL21F104ZBCNNNC"))
      (libsource (lib "eagle-import") (part "CAPACITORRLC_0603"))
    )
    (comp (ref "C52")
      (value "100nF")
      (footprint "eagle-import:RLC_0603")
      (fields (field (name "MPN") "CL21F104ZBCNNNC"))
      (libsource (lib "eagle-import") (part "CAPACITORRLC_0603"))
    )
    (comp (ref "C53")
      (value "12pF")
      (footprint "eagle-import:RLC_0603")
      (fields (field (name "MPN") "CL21C120JBANNNC"))
      (libsource (lib "eagle-import") (part "CAPACITORRLC_0603"))
    )
    (comp (ref "C54")
      (value "12pF")
      (footprint "eagle-import:RLC_0603")
      (fields (field (name "MPN") "CL21C120JBANNNC"))
      (libsource (lib "eagle-import") (part "CAPACITORRLC_0603"))
    )
    (comp (ref "C55")
      (value "10uF")
      (footprint "eagle-import:EIA3216-KIT")
      (fields (field (name "MF") "TAJA106M006RNJ"))
      (libsource (lib "eagle-import") (part "CAP_POL1206-KIT"))
    )
    (comp (ref "C56")
      (value "100nF")
      (footprint "eagle-import:RLC_0603")
      (fields (field (name "MPN") "CL21F104ZBCNNNC"))
      (libsource (lib "eagle-import") (part "CAPACITORRLC_0603"))
    )
    (comp (ref "D4")
      (value "PMEG4005ET")
      (footprint "eagle-import:SOT23-3")
      (fields (field (name "MPN") "PMEG4005ET,215"))
      (libsource (lib "eagle-import") (part "DIODESOT23"))
    )
    (comp (ref "D5")
      (value "PMEG4005ET")
      (footprint "eagle-import:SOT23-3")
      (fields (field (name "MPN") "PMEG4005ET,215"))
      (libsource (lib "eagle-import") (part "DIODESOT23"))
    )
    (comp (ref "FPGA_DOUT_TP")
      (value "TESTPAD")
      (footprint "eagle-import:SMD-TESTPOINT")
      (libsource (lib "eagle-import") (part "TESTPAD"))
    )
    (comp (ref "FPGA_NINIT_TP")
      (value "TESTPAD")
      (footprint "eagle-import:SMD-TESTPOINT")
      (libsource (lib "eagle-import") (part "TESTPAD"))
    )
    (comp (ref "FPGA_NINIT_TP1")
      (value "TESTPAD")
      (footprint "eagle-import:SMD-TESTPOINT")
      (libsource (lib "eagle-import") (part "TESTPAD"))
    )
    (comp (ref "FPGA_NINIT_TP2")
      (value "TESTPAD")
      (footprint "eagle-import:SMD-TESTPOINT")
      (libsource (lib "eagle-import") (part "TESTPAD"))
    )
    (comp (ref "IC2")
      (value "STM32F1_HIGH_DENSITY_LQFP64LQFP64(10X10)")
      (footprint "eagle-import:LQFP64A_PACKAGE")
      (libsource (lib "eagle-import") (part "STM32F1_HIGH_DENSITY_LQFP64LQFP64(10X10)"))
    )
    (comp (ref "IC7")
      (value "MCP100")
      (footprint "eagle-import:SOT23-3LEAD")
      (fields (field (name "MPN") "MCP100T-270I/TT"))
      (libsource (lib "eagle-import") (part "MCP100"))
    )
    (comp (ref "JP4")
      (value "HEADER-1X7ROUND")
      (footprint "eagle-import:1X07_ROUND")
      (libsource (lib "eagle-import") (part "HEADER-1X7ROUND"))
    )
    (comp (ref "JP_AH")
      (value "JUMPER-3SMD")
      (footprint "eagle-import:SJ_3")
      (libsource (lib "eagle-import") (part "JUMPER-3SMD"))
    )
    (comp (ref "JP_AL")
      (value "JUMPER-3SMD")
      (footprint "eagle-import:SJ_3")
      (libsource (lib "eagle-import") (part "JUMPER-3SMD"))
    )
    (comp (ref "K1")
      (value "5-XX")
      (footprint "eagle-import:B3F-5XX")
      (fields (field (name "MF") "PTS635SL50 LFS"))
      (libsource (lib "eagle-import") (part "5-XX"))
    )
    (comp (ref "K2")
      (value "5-XX")
      (footprint "eagle-import:B3F-5XX")
      (fields (field (name "MF") "PTS635SL50 LFS"))
      (libsource (lib "eagle-import") (part "5-XX"))
    )
    (comp (ref "K3")
      (value "5-XX")
      (footprint "eagle-import:B3F-5XX")
      (fields (field (name "MF") "PTS635SL50 LFS"))
      (libsource (lib "eagle-import") (part "5-XX"))
    )
    (comp (ref "L1")
      (value "100Ohm")
      (footprint "eagle-import:0603")
      (fields (field (name "MPN") "NONE"))
      (libsource (lib "eagle-import") (part "FERRITE1"))
    )
    (comp (ref "LED3")
      (value "LED_LEDSML0603")
      (footprint "eagle-import:LED_SML0603")
      (fields (field (name "MF") "LY Q976-P1S2-36"))
      (libsource (lib "eagle-import") (part "LED_LEDSML0603"))
    )
    (comp (ref "LED_A_TP")
      (value "TESTPAD")
      (footprint "eagle-import:SMD-TESTPOINT")
      (libsource (lib "eagle-import") (part "TESTPAD"))
    )
    (comp (ref "MISO_TP")
      (value "TESTPAD")
      (footprint "eagle-import:SMD-TESTPOINT")
      (libsource (lib "eagle-import") (part "TESTPAD"))
    )
    (comp (ref "MOSI_TP")
      (value "TESTPAD")
      (footprint "eagle-import:SMD-TESTPOINT")
      (libsource (lib "eagle-import") (part "TESTPAD"))
    )
    (comp (ref "NCS_TP")
      (value "TESTPAD")
      (footprint "eagle-import:SMD-TESTPOINT")
      (libsource (lib "eagle-import") (part "TESTPAD"))
    )
    (comp (ref "Q3")
      (value "MMBT2222")
      (footprint "eagle-import:SOT-23-3")
      (fields (field (name "MPN") "MMBT2222A-7-F"))
      (libsource (lib "eagle-import") (part "TRANSISTOR_NPNSOT23"))
    )
    (comp (ref "R4")
      (value "10K")
      (footprint "eagle-import:RLC_0603")
      (fields (field (name "DIGIKEY") "RMCF0603JT10K0CT-ND") (field (name "MPN") "RMCF0603JT10K0"))
      (libsource (lib "eagle-import") (part "RESISTORRLC_0603"))
    )
    (comp (ref "R5")
      (value "10K")
      (footprint "eagle-import:RLC_0603")
      (fields (field (name "DIGIKEY") "RMCF0603JT10K0CT-ND") (field (name "MPN") "RMCF0603JT10K0"))
      (libsource (lib "eagle-import") (part "RESISTORRLC_0603"))
    )
    (comp (ref "R6")
      (value "390")
      (footprint "eagle-import:RLC_0603")
      (fields (field (name "MPN") "RMCF0603JT390R"))
      (libsource (lib "eagle-import") (part "RESISTORRLC_0603"))
    )
    (comp (ref "R7")
      (value "27")
      (footprint "eagle-import:RLC_0603")
      (fields (field (name "MPN") "RMCF0603JT27R0"))
      (libsource (lib "eagle-import") (part "RESISTORRLC_0603"))
    )
    (comp (ref "R8")
      (value "27")
      (footprint "eagle-import:RLC_0603")
      (fields (field (name "MPN") "RMCF0603JT27R0"))
      (libsource (lib "eagle-import") (part "RESISTORRLC_0603"))
    )
    (comp (ref "R65")
      (value "330")
      (footprint "eagle-import:RLC_0603")
      (fields (field (name "MPN") "RMCF0603JT330R"))
      (libsource (lib "eagle-import") (part "RESISTORRLC_0603"))
    )
    (comp (ref "R69")
      (value "10K")
      (footprint "eagle-import:RLC_0603")
      (fields (field (name "MPN") "RMCF0603JT10K0"))
      (libsource (lib "eagle-import") (part "RESISTORRLC_0603"))
    )
    (comp (ref "R70")
      (value "10K")
      (footprint "eagle-import:RLC_0603")
      (fields (field (name "MPN") "RMCF0603JT10K0"))
      (libsource (lib "eagle-import") (part "RESISTORRLC_0603"))
    )
    (comp (ref "R71")
      (value "10K")
      (footprint "eagle-import:RLC_0603")
      (fields (field (name "MPN") "RMCF0603JT10K0"))
      (libsource (lib "eagle-import") (part "RESISTORRLC_0603"))
    )
    (comp (ref "R319")
      (value "100")
      (footprint "eagle-import:RLC_0603")
      (fields (field (name "MPN") "RMCF0603JT100R"))
      (libsource (lib "eagle-import") (part "RESISTORRLC_0603"))
    )
    (comp (ref "RELAY_ON_TP")
      (value "TESTPAD")
      (footprint "eagle-import:SMD-TESTPOINT")
      (libsource (lib "eagle-import") (part "TESTPAD"))
    )
    (comp (ref "SPCK_TP")
      (value "TESTPAD")
      (footprint "eagle-import:SMD-TESTPOINT")
      (libsource (lib "eagle-import") (part "TESTPAD"))
    )
    (comp (ref "TP6")
      (value "TESTPAD")
      (footprint "eagle-import:SMD-TESTPOINT")
      (libsource (lib "eagle-import") (part "TESTPAD"))
    )
    (comp (ref "TP11")
      (value "TESTPAD")
      (footprint "eagle-import:SMD-TESTPOINT")
      (libsource (lib "eagle-import") (part "TESTPAD"))
    )
    (comp (ref "TP22")
      (value "TESTPAD")
      (footprint "eagle-import:SMD-TESTPOINT")
      (libsource (lib "eagle-import") (part "TESTPAD"))
    )
    (comp (ref "TP23")
      (value "TESTPAD")
      (footprint "eagle-import:SMD-TESTPOINT")
      (libsource (lib "eagle-import") (part "TESTPAD"))
    )
    (comp (ref "TP24")
      (value "TESTPAD")
      (footprint "eagle-import:SMD-TESTPOINT")
      (libsource (lib "eagle-import") (part "TESTPAD"))
    )
    (comp (ref "TP25")
      (value "TESTPAD")
      (footprint "eagle-import:SMD-TESTPOINT")
      (libsource (lib "eagle-import") (part "TESTPAD"))
    )
    (comp (ref "TP26")
      (value "TESTPAD")
      (footprint "eagle-import:SMD-TESTPOINT")
      (libsource (lib "eagle-import") (part "TESTPAD"))
    )
    (comp (ref "TP28")
      (value "TESTPAD")
      (footprint "eagle-import:SMD-TESTPOINT")
      (libsource (lib "eagle-import") (part "TESTPAD"))
    )
    (comp (ref "TP29")
      (value "TESTPAD")
      (footprint "eagle-import:SMD-TESTPOINT")
      (libsource (lib "eagle-import") (part "TESTPAD"))
    )
    (comp (ref "TP30")
      (value "TESTPAD")
      (footprint "eagle-import:SMD-TESTPOINT")
      (libsource (lib "eagle-import") (part "TESTPAD"))
    )
    (comp (ref "TP31")
      (value "TESTPAD")
      (footprint "eagle-import:SMD-TESTPOINT")
      (libsource (lib "eagle-import") (part "TESTPAD"))
    )
    (comp (ref "TP32")
      (value "TESTPAD")
      (footprint "eagle-import:SMD-TESTPOINT")
      (libsource (lib "eagle-import") (part "TESTPAD"))
    )
    (comp (ref "TP33")
      (value "TESTPAD")
      (footprint "eagle-import:SMD-TESTPOINT")
      (libsource (lib "eagle-import") (part "TESTPAD"))
    )
    (comp (ref "TP34")
      (value "TESTPAD")
      (footprint "eagle-import:SMD-TESTPOINT")
      (libsource (lib "eagle-import") (part "TESTPAD"))
    )
    (comp (ref "TP35")
      (value "TESTPAD")
      (footprint "eagle-import:SMD-TESTPOINT")
      (libsource (lib "eagle-import") (part "TESTPAD"))
    )
    (comp (ref "TP48")
      (value "TESTPAD")
      (footprint "eagle-import:SMD-TESTPOINT")
      (libsource (lib "eagle-import") (part "TESTPAD"))
    )
    (comp (ref "TP49")
      (value "TESTPAD")
      (footprint "eagle-import:SMD-TESTPOINT")
      (libsource (lib "eagle-import") (part "TESTPAD"))
    )
    (comp (ref "TP50")
      (value "TESTPAD")
      (footprint "eagle-import:SMD-TESTPOINT")
      (libsource (lib "eagle-import") (part "TESTPAD"))
    )
    (comp (ref "TP51")
      (value "TESTPAD")
      (footprint "eagle-import:SMD-TESTPOINT")
      (libsource (lib "eagle-import") (part "TESTPAD"))
    )
    (comp (ref "TP52")
      (value "TESTPAD")
      (footprint "eagle-import:SMD-TESTPOINT")
      (libsource (lib "eagle-import") (part "TESTPAD"))
    )
    (comp (ref "TP53")
      (value "TESTPAD")
      (footprint "eagle-import:SMD-TESTPOINT")
      (libsource (lib "eagle-import") (part "TESTPAD"))
    )
    (comp (ref "TP54")
      (value "TESTPAD")
      (footprint "eagle-import:SMD-TESTPOINT")
      (libsource (lib "eagle-import") (part "TESTPAD"))
    )
    (comp (ref "TP55")
      (value "TESTPAD")
      (footprint "eagle-import:SMD-TESTPOINT")
      (libsource (lib "eagle-import") (part "TESTPAD"))
    )
    (comp (ref "Y1")
      (value "8Mhz")
      (footprint "eagle-import:CRYSTAL-TXC-7A")
      (fields (field (name "MPN") "7A-8.000MAAE-T"))
      (libsource (lib "eagle-import") (part "CRYSTALTXC-7A"))
    )
    (comp (ref "C1")
      (value "33nF")
      (footprint "eagle-import:RLC_0603")
      (fields (field (name "MPN") "CC0603KRX7R9BB333"))
      (libsource (lib "eagle-import") (part "CAPACITORRLC_0603"))
    )
    (comp (ref "C21")
      (value "33nF")
      (footprint "eagle-import:RLC_0603")
      (fields (field (name "MPN") "CC0603KRX7R9BB333"))
      (libsource (lib "eagle-import") (part "CAPACITORRLC_0603"))
    )
    (comp (ref "C22")
      (value "33nF")
      (footprint "eagle-import:RLC_0603")
      (fields (field (name "MPN") "CC0603KRX7R9BB333"))
      (libsource (lib "eagle-import") (part "CAPACITORRLC_0603"))
    )
    (comp (ref "C23")
      (value "33nF")
      (footprint "eagle-import:RLC_0603")
      (fields (field (name "MPN") "CC0603KRX7R9BB333"))
      (libsource (lib "eagle-import") (part "CAPACITORRLC_0603"))
    )
    (comp (ref "C24")
      (value "33nF")
      (footprint "eagle-import:RLC_0603")
      (fields (field (name "MPN") "CC0603KRX7R9BB333"))
      (libsource (lib "eagle-import") (part "CAPACITORRLC_0603"))
    )
    (comp (ref "C25")
      (value "33nF")
      (footprint "eagle-import:RLC_0603")
      (fields (field (name "MPN") "CC0603KRX7R9BB333"))
      (libsource (lib "eagle-import") (part "CAPACITORRLC_0603"))
    )
    (comp (ref "C26")
      (value "33nF")
      (footprint "eagle-import:RLC_0603")
      (fields (field (name "MPN") "CC0603KRX7R9BB333"))
      (libsource (lib "eagle-import") (part "CAPACITORRLC_0603"))
    )
    (comp (ref "C27")
      (value "4.7uF")
      (footprint "eagle-import:RLC_1210")
      (fields (field (name "MPN") "CL32B475KOINNNE"))
      (libsource (lib "eagle-import") (part "CAPACITOR1210"))
    )
    (comp (ref "C28")
      (value "33nF")
      (footprint "eagle-import:RLC_0603")
      (fields (field (name "MPN") "CC0603KRX7R9BB333"))
      (libsource (lib "eagle-import") (part "CAPACITORRLC_0603"))
    )
    (comp (ref "C29")
      (value "33nF")
      (footprint "eagle-import:RLC_0603")
      (fields (field (name "MPN") "CC0603KRX7R9BB333"))
      (libsource (lib "eagle-import") (part "CAPACITORRLC_0603"))
    )
    (comp (ref "C30")
      (value "33nF")
      (footprint "eagle-import:RLC_0603")
      (fields (field (name "MPN") "CC0603KRX7R9BB333"))
      (libsource (lib "eagle-import") (part "CAPACITORRLC_0603"))
    )
    (comp (ref "C31")
      (value "33nF")
      (footprint "eagle-import:RLC_0603")
      (fields (field (name "MPN") "CC0603KRX7R9BB333"))
      (libsource (lib "eagle-import") (part "CAPACITORRLC_0603"))
    )
    (comp (ref "C32")
      (value "33nF")
      (footprint "eagle-import:RLC_0603")
      (fields (field (name "MPN") "CC0603KRX7R9BB333"))
      (libsource (lib "eagle-import") (part "CAPACITORRLC_0603"))
    )
    (comp (ref "C33")
      (value "4.7uF")
      (footprint "eagle-import:RLC_1210")
      (fields (field (name "MPN") "CL32B475KOINNNE"))
      (libsource (lib "eagle-import") (part "CAPACITOR1210"))
    )
    (comp (ref "C34")
      (value "4.7uF")
      (footprint "eagle-import:RLC_1210")
      (fields (field (name "MPN") "CL32B475KOINNNE"))
      (libsource (lib "eagle-import") (part "CAPACITOR1210"))
    )
    (comp (ref "C37")
      (value "100uF")
      (footprint "eagle-import:D_7343-31R")
      (fields (field (name "MPN") "T491D107K010AT"))
      (libsource (lib "eagle-import") (part "CPOL-USD/7343-31R"))
    )
    (comp (ref "C38")
      (value "100uF")
      (footprint "eagle-import:D_7343-31R")
      (fields (field (name "MPN") "T491D107K010AT"))
      (libsource (lib "eagle-import") (part "CPOL-USD/7343-31R"))
    )
    (comp (ref "C44")
      (value "33nF")
      (footprint "eagle-import:RLC_0603")
      (fields (field (name "MPN") "CC0603KRX7R9BB333"))
      (libsource (lib "eagle-import") (part "CAPACITORRLC_0603"))
    )
    (comp (ref "C46")
      (value "33nF")
      (footprint "eagle-import:RLC_0603")
      (fields (field (name "MPN") "CC0603KRX7R9BB333"))
      (libsource (lib "eagle-import") (part "CAPACITORRLC_0603"))
    )
    (comp (ref "C47")
      (value "33nF")
      (footprint "eagle-import:RLC_0603")
      (fields (field (name "MPN") "CC0603KRX7R9BB333"))
      (libsource (lib "eagle-import") (part "CAPACITORRLC_0603"))
    )
    (comp (ref "C74")
      (value "10nF")
      (footprint "eagle-import:RLC_0603")
      (fields (field (name "MPN") "C0603C103K5RACTU"))
      (libsource (lib "eagle-import") (part "CAPACITORRLC_0603"))
    )
    (comp (ref "C75")
      (value "10nF")
      (footprint "eagle-import:RLC_0603")
      (fields (field (name "MPN") "C0603C103K5RACTU"))
      (libsource (lib "eagle-import") (part "CAPACITORRLC_0603"))
    )
    (comp (ref "C206")
      (value "4.7uF")
      (footprint "eagle-import:RLC_0603")
      (fields (field (name "MPN") "EMK107ABJ475KA-T"))
      (libsource (lib "eagle-import") (part "C-EU"))
    )
    (comp (ref "C209")
      (value "100nF")
      (footprint "eagle-import:RLC_0603")
      (fields (field (name "MPN") "CL10B104KO8NNNC"))
      (libsource (lib "eagle-import") (part "C-EU"))
    )
    (comp (ref "C210")
      (value "100nF")
      (footprint "eagle-import:RLC_0603")
      (fields (field (name "MPN") "CL10B104KO8NNNC"))
      (libsource (lib "eagle-import") (part "C-EU"))
    )
    (comp (ref "C211")
      (value "100nF")
      (footprint "eagle-import:RLC_0603")
      (fields (field (name "MPN") "CL10B104KO8NNNC"))
      (libsource (lib "eagle-import") (part "C-EU"))
    )
    (comp (ref "C212")
      (value "100nF")
      (footprint "eagle-import:RLC_0603")
      (fields (field (name "MPN") "CL10B104KO8NNNC"))
      (libsource (lib "eagle-import") (part "C-EU"))
    )
    (comp (ref "D6")
      (value "USBUG_PRTR5V0U2X")
      (footprint "eagle-import:USBUG_SOT143B")
      (libsource (lib "eagle-import") (part "USBUG_PRTR5V0U2X"))
    )
    (comp (ref "F1")
      (value "PTCFUSE-1812")
      (footprint "eagle-import:1812")
      (fields (field (name "MPN") "MICROSMD050F-2"))
      (libsource (lib "eagle-import") (part "PTCFUSE-1812"))
    )
    (comp (ref "IC3")
      (value "PQ1X331M2ZP-3V3-LDO-SOT-23-5")
      (footprint "eagle-import:SOT-23-5")
      (fields (field (name "MPN") "LP2985-33DBVR"))
      (libsource (lib "eagle-import") (part "PQ1X331M2ZP-3V3-LDO-SOT-23-5"))
    )
    (comp (ref "IC13")
      (value "PQ1X331M2ZP-3V3-LDO-SOT-23-5")
      (footprint "eagle-import:SOT-23-5")
      (fields (field (name "MPN") "LP2985-33DBVR"))
      (libsource (lib "eagle-import") (part "PQ1X331M2ZP-3V3-LDO-SOT-23-5"))
    )
    (comp (ref "IC105")
      (value "MCP1824T-250")
      (footprint "eagle-import:SOT-23-5")
      (fields (field (name "MPN") "MCP1824T-2502E/OT"))
      (libsource (lib "eagle-import") (part "TPS79925"))
    )
    (comp (ref "IC106")
      (value "MCP1824T-120")
      (footprint "eagle-import:SOT-23-5")
      (fields (field (name "MPN") "MCP1824T-1202E/OT"))
      (libsource (lib "eagle-import") (part "TPS79912"))
    )
    (comp (ref "Q2")
      (value "BC817-16SMD")
      (footprint "eagle-import:SOT23-BEC")
      (libsource (lib "eagle-import") (part "BC817SMD-16"))
    )
    (comp (ref "Q4")
      (value "BC817-16SMD")
      (footprint "eagle-import:SOT23-BEC")
      (libsource (lib "eagle-import") (part "BC817SMD-16"))
    )
    (comp (ref "R23")
      (value "1K")
      (footprint "eagle-import:RLC_0603")
      (fields (field (name "MPN") "RMCF0603JT1K00"))
      (libsource (lib "eagle-import") (part "RESISTORRLC_0603"))
    )
    (comp (ref "R56")
      (value "10K")
      (footprint "eagle-import:RLC_0603")
      (fields (field (name "MPN") "RMCF0603JT10K0"))
      (libsource (lib "eagle-import") (part "RESISTORRLC_0603"))
    )
    (comp (ref "R57")
      (value "10K")
      (footprint "eagle-import:RLC_0603")
      (fields (field (name "MPN") "RMCF0603JT10K0"))
      (libsource (lib "eagle-import") (part "RESISTORRLC_0603"))
    )
    (comp (ref "R58")
      (value "10K")
      (footprint "eagle-import:RLC_0603")
      (fields (field (name "MPN") "RMCF0603JT10K0"))
      (libsource (lib "eagle-import") (part "RESISTORRLC_0603"))
    )
    (comp (ref "R67")
      (value "10K")
      (footprint "eagle-import:RLC_0603")
      (fields (field (name "MPN") "RMCF0603JT10K0"))
      (libsource (lib "eagle-import") (part "RESISTORRLC_0603"))
    )
    (comp (ref "R68")
      (value "10K")
      (footprint "eagle-import:RLC_0603")
      (fields (field (name "MPN") "RMCF0603JT10K0"))
      (libsource (lib "eagle-import") (part "RESISTORRLC_0603"))
    )
    (comp (ref "R102")
      (value "10K")
      (footprint "eagle-import:RLC_0603")
      (fields (field (name "MPN") "RMCF0603JT10K0"))
      (libsource (lib "eagle-import") (part "RESISTORRLC_0603"))
    )
    (comp (ref "SV1")
      (value "USB-MINIB")
      (footprint "eagle-import:USB-MINIB-SMD")
      (libsource (lib "eagle-import") (part "USB-MINIB"))
    )
    (comp (ref "TP18")
      (value "TESTPAD")
      (footprint "eagle-import:SMD-TESTPOINT")
      (libsource (lib "eagle-import") (part "TESTPAD"))
    )
    (comp (ref "TP19")
      (value "TESTPAD")
      (footprint "eagle-import:SMD-TESTPOINT")
      (libsource (lib "eagle-import") (part "TESTPAD"))
    )
    (comp (ref "TP20")
      (value "TESTPAD")
      (footprint "eagle-import:SMD-TESTPOINT")
      (libsource (lib "eagle-import") (part "TESTPAD"))
    )
    (comp (ref "U1")
      (value "FERRITE0805")
      (footprint "eagle-import:RLC_0805")
      (fields (field (name "MF") "MPZ2012S300A"))
      (libsource (lib "eagle-import") (part "FERRITE0805"))
    )
    (comp (ref "USB-MICRO")
      (value "USB-MICROB")
      (footprint "eagle-import:USB-MICROB")
      (fields (field (name "MF") "1981568-1"))
      (libsource (lib "eagle-import") (part "USB-MICROB"))
    )
    (comp (ref "R61")
      (value "10K")
      (footprint "eagle-import:RLC_0603")
      (fields (field (name "MPN") "RMCF0603JT10K0"))
      (libsource (lib "eagle-import") (part "RESISTORRLC_0603"))
    )
    (comp (ref "R62")
      (value "10K")
      (footprint "eagle-import:RLC_0603")
      (fields (field (name "MPN") "RMCF0603JT10K0"))
      (libsource (lib "eagle-import") (part "RESISTORRLC_0603"))
    )
    (comp (ref "R63")
      (value "10K")
      (footprint "eagle-import:RLC_0603")
      (fields (field (name "MPN") "RMCF0603JT10K0"))
      (libsource (lib "eagle-import") (part "RESISTORRLC_0603"))
    )
    (comp (ref "R64")
      (value "10K")
      (footprint "eagle-import:RLC_0603")
      (fields (field (name "MPN") "RMCF0603JT10K0"))
      (libsource (lib "eagle-import") (part "RESISTORRLC_0603"))
    )
    (comp (ref "U4")
      (value "SDCARD")
      (footprint "eagle-import:MICRO-SD-SOCKET-PP")
      (libsource (lib "eagle-import") (part "USD-SOCKETNEW"))
    )
    (comp (ref "C10")
      (value "100nF")
      (footprint "eagle-import:RLC_0603")
      (fields (field (name "MPN") "CL10B104KO8NNNC"))
      (libsource (lib "eagle-import") (part "CAPACITORRLC_0603"))
    )
    (comp (ref "C11")
      (value "1nF")
      (footprint "eagle-import:RLC_0603")
      (fields (field (name "MPN") "GRM188R71H102KA01D"))
      (libsource (lib "eagle-import") (part "CAPACITORRLC_0603"))
    )
    (comp (ref "C12")
      (value "1nF")
      (footprint "eagle-import:RLC_0603")
      (fields (field (name "MPN") "GRM188R71H102KA01D"))
      (libsource (lib "eagle-import") (part "CAPACITORRLC_0603"))
    )
    (comp (ref "C13")
      (value "dnp")
      (footprint "eagle-import:RLC_0603")
      (libsource (lib "eagle-import") (part "CAPACITORRLC_0603"))
    )
    (comp (ref "C14")
      (value "22pF")
      (footprint "eagle-import:RLC_0603")
      (fields (field (name "MPN") "C1608C0G1H220J080AA"))
      (libsource (lib "eagle-import") (part "CAPACITORRLC_0603"))
    )
    (comp (ref "C15")
      (value "130pF")
      (footprint "eagle-import:RLC_0603")
      (fields (field (name "MPN") "GRM1885C1H131JA01D"))
      (libsource (lib "eagle-import") (part "CAPACITORRLC_0603"))
    )
    (comp (ref "C16")
      (value "1nF")
      (footprint "eagle-import:RLC_0603")
      (fields (field (name "MPN") "GRM188R71H102KA01D"))
      (libsource (lib "eagle-import") (part "CAPACITORRLC_0603"))
    )
    (comp (ref "C17")
      (value "dnp")
      (footprint "eagle-import:RLC_0603")
      (libsource (lib "eagle-import") (part "CAPACITORRLC_0603"))
    )
    (comp (ref "C40")
      (value "dnp")
      (footprint "eagle-import:RLC_0603")
      (libsource (lib "eagle-import") (part "CAPACITORRLC_0603"))
    )
    (comp (ref "C41")
      (value "dnp")
      (footprint "eagle-import:RLC_0603")
      (libsource (lib "eagle-import") (part "CAPACITORRLC_0603"))
    )
    (comp (ref "C42")
      (value "1nF")
      (footprint "eagle-import:RLC_0603")
      (fields (field (name "MPN") "GRM188R71H102KA01D"))
      (libsource (lib "eagle-import") (part "CAPACITORRLC_0603"))
    )
    (comp (ref "C43")
      (value "1nF")
      (footprint "eagle-import:RLC_0603")
      (fields (field (name "MPN") "GRM188R71H102KA01D"))
      (libsource (lib "eagle-import") (part "CAPACITORRLC_0603"))
    )
    (comp (ref "C45")
      (value "100nF")
      (footprint "eagle-import:RLC_0603")
      (fields (field (name "MPN") "CL10B104KO8NNNC"))
      (libsource (lib "eagle-import") (part "CAPACITORRLC_0603"))
    )
    (comp (ref "D1")
      (value "DIODE-SMD-SOT23")
      (footprint "eagle-import:SOT23-3LEAD")
      (fields (field (name "MF") "BAS 21 E6327"))
      (libsource (lib "eagle-import") (part "DIODE-SMD-SOT23"))
    )
    (comp (ref "D2")
      (value "DIODE-SMD-SOT23")
      (footprint "eagle-import:SOT23-3LEAD")
      (fields (field (name "MF") "BAS 21 E6327"))
      (libsource (lib "eagle-import") (part "DIODE-SMD-SOT23"))
    )
    (comp (ref "D3")
      (value "DIODE-SMD-SOT23")
      (footprint "eagle-import:SOT23-3LEAD")
      (fields (field (name "MF") "BAS 21 E6327"))
      (libsource (lib "eagle-import") (part "DIODE-SMD-SOT23"))
    )
    (comp (ref "D7")
      (value "DIODE-SMD-SOT23")
      (footprint "eagle-import:SOT23-3LEAD")
      (libsource (lib "eagle-import") (part "DIODE-SMD-SOT23"))
    )
    (comp (ref "D10")
      (value "DIODE-SMD-SOT23")
      (footprint "eagle-import:SOT23-3LEAD")
      (libsource (lib "eagle-import") (part "DIODE-SMD-SOT23"))
    )
    (comp (ref "D11")
      (value "DIODE-SMD-SOT23")
      (footprint "eagle-import:SOT23-3LEAD")
      (libsource (lib "eagle-import") (part "DIODE-SMD-SOT23"))
    )
    (comp (ref "IC5")
      (value "TLV3502")
      (footprint "eagle-import:SOT-23-8-OR-MSOP-8")
      (fields
        (field (name "MPN") "TLV3502AIDCNT")
        (field (name "DIGIKEY") "296-18147-1-ND")
        (field (name "OC_NEWARK") "unknown")
        (field (name "PARTNO") "TLV3502AIDCNT")
      )
      (libsource (lib "eagle-import") (part "COMP-TLV3502SOT-23-8-OR-MSOP-8"))
    )
    (comp (ref "IC6")
      (value "MCP6294")
      (footprint "eagle-import:TSSOP-14")
      (fields
        (field (name "DIGIKEY") "MCP6294-E/ST-ND")
        (field (name "MPN") "MCP6294-E/ST")
        (field (name "OC_NEWARK") "unknown")
        (field (name "PARTNO") "MCP6294-E/ST")
      )
      (libsource (lib "eagle-import") (part "OPAMP-TLC2274"))
    )
    (comp (ref "IC11")
      (value "CD4066")
      (footprint "eagle-import:TSSOP-14")
      (fields (field (name "MPN") "CD4066BPWR"))
      (libsource (lib "eagle-import") (part "CD4066"))
    )
    (comp (ref "IC14")
      (value "AD8052")
      (footprint "eagle-import:MSOP8")
      (fields
        (field (name "MPN") "AD8052ARMZ")
        (field (name "DIGIKEY") "AD8052ARMZ-ND")
        (field (name "OC_NEWARK") "unknown")
        (field (name "PARTNO") "AD8052ARMZ")
      )
      (libsource (lib "eagle-import") (part "OPAMP-AD8052"))
    )
    (comp (ref "Q1")
      (value "NPN-SOT23-2N3904")
      (footprint "eagle-import:SOT23-3LEAD")
      (fields (field (name "MF") "PMBT3904,215"))
      (libsource (lib "eagle-import") (part "NPN-SOT23-2N3904"))
    )
    (comp (ref "R9")
      (value "100K")
      (footprint "eagle-import:RLC_0603")
      (fields (field (name "MPN") "RC0603JR-07100KL"))
      (libsource (lib "eagle-import") (part "RESISTORRLC_0603"))
    )
    (comp (ref "R10")
      (value "100K")
      (footprint "eagle-import:RLC_0603")
      (fields (field (name "MPN") "RC0603JR-07100KL"))
      (libsource (lib "eagle-import") (part "RESISTORRLC_0603"))
    )
    (comp (ref "R11")
      (value "510K")
      (footprint "eagle-import:RLC_0603")
      (fields (field (name "MPN") "ERJ-3GEYJ514V"))
      (libsource (lib "eagle-import") (part "RESISTORRLC_0603"))
    )
    (comp (ref "R12")
      (value "100K")
      (footprint "eagle-import:RLC_0603")
      (fields (field (name "MPN") "RC0603JR-07100KL"))
      (libsource (lib "eagle-import") (part "RESISTORRLC_0603"))
    )
    (comp (ref "R13")
      (value "10K")
      (footprint "eagle-import:RLC_0603")
      (fields (field (name "DIGIKEY") "RMCF0603JT10K0CT-ND") (field (name "MPN") "RMCF0603JT10K0"))
      (libsource (lib "eagle-import") (part "RESISTORRLC_0603"))
    )
    (comp (ref "R14")
      (value "10K")
      (footprint "eagle-import:RLC_0603")
      (fields (field (name "DIGIKEY") "RMCF0603JT10K0CT-ND") (field (name "MPN") "RMCF0603JT10K0"))
      (libsource (lib "eagle-import") (part "RESISTORRLC_0603"))
    )
    (comp (ref "R15")
      (value "10K")
      (footprint "eagle-import:RLC_0603")
      (fields (field (name "DIGIKEY") "RMCF0603JT10K0CT-ND") (field (name "MPN") "RMCF0603JT10K0"))
      (libsource (lib "eagle-import") (part "RESISTORRLC_0603"))
    )
    (comp (ref "R16")
      (value "zerohm")
      (footprint "eagle-import:RLC_0603")
      (libsource (lib "eagle-import") (part "RESISTORRLC_0603"))
    )
    (comp (ref "R17")
      (value "10K")
      (footprint "eagle-import:RLC_0603")
      (fields (field (name "DIGIKEY") "RMCF0603JT10K0CT-ND") (field (name "MPN") "RMCF0603JT10K0"))
      (libsource (lib "eagle-import") (part "RESISTORRLC_0603"))
    )
    (comp (ref "R18")
      (value "10K")
      (footprint "eagle-import:RLC_0603")
      (fields (field (name "DIGIKEY") "RMCF0603JT10K0CT-ND") (field (name "MPN") "RMCF0603JT10K0"))
      (libsource (lib "eagle-import") (part "RESISTORRLC_0603"))
    )
    (comp (ref "R19")
      (value "10K")
      (footprint "eagle-import:RLC_0603")
      (fields (field (name "DIGIKEY") "RMCF0603JT10K0CT-ND") (field (name "MPN") "RMCF0603JT10K0"))
      (libsource (lib "eagle-import") (part "RESISTORRLC_0603"))
    )
    (comp (ref "R20")
      (value "240K")
      (footprint "eagle-import:RLC_0603")
      (fields (field (name "MPN") "RC1608J244CS"))
      (libsource (lib "eagle-import") (part "RESISTORRLC_0603"))
    )
    (comp (ref "R21")
      (value "24K")
      (footprint "eagle-import:RLC_0603")
      (fields (field (name "MPN") "RC0603JR-0724KL"))
      (libsource (lib "eagle-import") (part "RESISTORRLC_0603"))
    )
    (comp (ref "R30")
      (value "10M")
      (footprint "eagle-import:RLC_0603")
      (fields (field (name "MPN") "RC0603JR-0710ML"))
      (libsource (lib "eagle-import") (part "RESISTORRLC_0603"))
    )
    (comp (ref "R31")
      (value "240K")
      (footprint "eagle-import:RLC_0603")
      (fields (field (name "MPN") "RC1608J244CS"))
      (libsource (lib "eagle-import") (part "RESISTORRLC_0603"))
    )
    (comp (ref "R32")
      (value "zerohm")
      (footprint "eagle-import:RLC_0603")
      (libsource (lib "eagle-import") (part "RESISTORRLC_0603"))
    )
    (comp (ref "R33")
      (value "2.4K")
      (footprint "eagle-import:RLC_0603")
      (fields (field (name "MPN") "RC0603FR-072K4L"))
      (libsource (lib "eagle-import") (part "RESISTORRLC_0603"))
    )
    (comp (ref "R34")
      (value "10K")
      (footprint "eagle-import:RLC_0603")
      (fields (field (name "MPN") "RMCF0603JT10K0"))
      (libsource (lib "eagle-import") (part "RESISTORRLC_0603"))
    )
    (comp (ref "R35")
      (value "zerohm")
      (footprint "eagle-import:RLC_0603")
      (libsource (lib "eagle-import") (part "RESISTORRLC_0603"))
    )
    (comp (ref "R36")
      (value "dnp")
      (footprint "eagle-import:RLC_0603")
      (libsource (lib "eagle-import") (part "RESISTORRLC_0603"))
    )
    (comp (ref "R37")
      (value "dnp")
      (footprint "eagle-import:RLC_0603")
      (libsource (lib "eagle-import") (part "RESISTORRLC_0603"))
    )
    (comp (ref "R38")
      (value "dnp")
      (footprint "eagle-import:RLC_0603")
      (libsource (lib "eagle-import") (part "RESISTORRLC_0603"))
    )
    (comp (ref "R40")
      (value "10K")
      (footprint "eagle-import:RLC_0603")
      (fields (field (name "MPN") "RMCF0603JT10K0"))
      (libsource (lib "eagle-import") (part "RESISTORRLC_0603"))
    )
    (comp (ref "R41")
      (value "10M")
      (footprint "eagle-import:RLC_0603")
      (fields (field (name "MPN") "RC0603JR-0710ML"))
      (libsource (lib "eagle-import") (part "RESISTORRLC_0603"))
    )
    (comp (ref "R42")
      (value "1M")
      (footprint "eagle-import:RLC_0603")
      (fields (field (name "MPN") "RC0603JR-071ML"))
      (libsource (lib "eagle-import") (part "RESISTORRLC_0603"))
    )
    (comp (ref "R48")
      (value "dnp")
      (footprint "eagle-import:RLC_0603")
      (libsource (lib "eagle-import") (part "RESISTORRLC_0603"))
    )
    (comp (ref "R49")
      (value "2.4K")
      (footprint "eagle-import:RLC_0603")
      (fields (field (name "MPN") "RC0603FR-072K4L"))
      (libsource (lib "eagle-import") (part "RESISTORRLC_0603"))
    )
    (comp (ref "R50")
      (value "10K")
      (footprint "eagle-import:RLC_0603")
      (fields (field (name "MPN") "RMCF0603JT10K0"))
      (libsource (lib "eagle-import") (part "RESISTORRLC_0603"))
    )
    (comp (ref "R51")
      (value "2.4K")
      (footprint "eagle-import:RLC_0603")
      (fields (field (name "MPN") "RC0603FR-072K4L"))
      (libsource (lib "eagle-import") (part "RESISTORRLC_0603"))
    )
    (comp (ref "RLY1")
      (value "G6S-2H")
      (footprint "eagle-import:G6S-2F")
      (libsource (lib "eagle-import") (part "G6S-2H"))
    )
    (comp (ref "TP1")
      (value "TESTPAD")
      (footprint "eagle-import:SMD-TESTPOINT")
      (libsource (lib "eagle-import") (part "TESTPAD"))
    )
  )
  (nets
    (net (code "1") (name "+1V2") (class "Default")
      (node (ref "C206") (pin "1") (pinfunction "1_1") (pintype "passive"))
      (node (ref "C209") (pin "1") (pinfunction "1_1") (pintype "passive"))
      (node (ref "C210") (pin "1") (pinfunction "1_1") (pintype "passive"))
      (node (ref "C211") (pin "1") (pinfunction "1_1") (pintype "passive"))
      (node (ref "C212") (pin "1") (pinfunction "1_1") (pintype "passive"))
      (node (ref "IC106") (pin "5") (pinfunction "VOUT_5") (pintype "bidirectional"))
      (node (ref "TP20") (pin "1") (pinfunction "P$1_1") (pintype "bidirectional"))
      (node (ref "U2") (pin "18") (pinfunction "VCCINT_18") (pintype "power_in"))
      (node (ref "U2") (pin "45") (pinfunction "VCCINT_45") (pintype "power_in"))
      (node (ref "U2") (pin "69") (pinfunction "VCCINT_69") (pintype "power_in"))
      (node (ref "U2") (pin "93") (pinfunction "VCCINT_93") (pintype "power_in"))
    )
    (net (code "2") (name "+2V5") (class "Default")
      (node (ref "C29") (pin "1") (pinfunction "1_1") (pintype "passive"))
      (node (ref "C30") (pin "1") (pinfunction "1_1") (pintype "passive"))
      (node (ref "C31") (pin "1") (pinfunction "1_1") (pintype "passive"))
      (node (ref "C33") (pin "1") (pinfunction "1_1") (pintype "passive"))
      (node (ref "IC105") (pin "5") (pinfunction "VOUT_5") (pintype "bidirectional"))
      (node (ref "TP19") (pin "1") (pinfunction "P$1_1") (pintype "bidirectional"))
      (node (ref "U2") (pin "33") (pinfunction "VCCAUX_33") (pintype "power_in"))
      (node (ref "U2") (pin "58") (pinfunction "VCCAUX_58") (pintype "power_in"))
      (node (ref "U2") (pin "7") (pinfunction "VCCAUX_7") (pintype "power_in"))
      (node (ref "U2") (pin "84") (pinfunction "VCCAUX_84") (pintype "power_in"))
    )
    (net (code "3") (name "+3V3") (class "Default")
      (node (ref "BUZ1") (pin "1") (pinfunction "1_1") (pintype "passive"))
      (node (ref "C25") (pin "1") (pinfunction "1_1") (pintype "passive"))
      (node (ref "C26") (pin "1") (pinfunction "1_1") (pintype "passive"))
      (node (ref "C27") (pin "1") (pinfunction "1_1") (pintype "passive"))
      (node (ref "C48") (pin "1") (pinfunction "1_1") (pintype "passive"))
      (node (ref "C49") (pin "1") (pinfunction "1_1") (pintype "passive"))
      (node (ref "C50") (pin "1") (pinfunction "1_1") (pintype "passive"))
      (node (ref "C51") (pin "1") (pinfunction "1_1") (pintype "passive"))
      (node (ref "C7") (pin "1") (pinfunction "1_1") (pintype "passive"))
      (node (ref "D5") (pin "1") (pinfunction "A_1") (pintype "passive"))
      (node (ref "IC2") (pin "19") (pinfunction "VDD_19") (pintype "power_in"))
      (node (ref "IC2") (pin "32") (pinfunction "VDD_32") (pintype "power_in"))
      (node (ref "IC2") (pin "48") (pinfunction "VDD_48") (pintype "power_in"))
      (node (ref "IC2") (pin "64") (pinfunction "VDD_64") (pintype "power_in"))
      (node (ref "IC3") (pin "5") (pinfunction "VO_5") (pintype "bidirectional"))
      (node (ref "IC7") (pin "2") (pinfunction "V+_2") (pintype "bidirectional"))
      (node (ref "JP4") (pin "6") (pinfunction "6_6") (pintype "passive"))
      (node (ref "L1") (pin "1") (pinfunction "P$1_1") (pintype "bidirectional"))
      (node (ref "Q2") (pin "C") (pinfunction "C_C") (pintype "passive"))
      (node (ref "R57") (pin "1") (pinfunction "1_1") (pintype "passive"))
      (node (ref "R61") (pin "2") (pinfunction "2_2") (pintype "passive"))
      (node (ref "R62") (pin "2") (pinfunction "2_2") (pintype "passive"))
      (node (ref "R63") (pin "2") (pinfunction "2_2") (pintype "passive"))
      (node (ref "R64") (pin "2") (pinfunction "2_2") (pintype "passive"))
      (node (ref "R69") (pin "2") (pinfunction "2_2") (pintype "passive"))
      (node (ref "R70") (pin "2") (pinfunction "2_2") (pintype "passive"))
      (node (ref "R71") (pin "2") (pinfunction "2_2") (pintype "passive"))
      (node (ref "SV5") (pin "6") (pinfunction "6_6") (pintype "passive"))
      (node (ref "U3") (pin "6") (pinfunction "VBAT_6") (pintype "input"))
      (node (ref "U3") (pin "9") (pinfunction "VDD_9") (pintype "power_in"))
      (node (ref "U4") (pin "4") (pinfunction "VCC_4") (pintype "bidirectional"))
    )
    (net (code "4") (name "+3V3-FPGA") (class "Default")
      (node (ref "C28") (pin "1") (pinfunction "1_1") (pintype "passive"))
      (node (ref "C32") (pin "1") (pinfunction "1_1") (pintype "passive"))
      (node (ref "C34") (pin "1") (pinfunction "1_1") (pintype "passive"))
      (node (ref "C47") (pin "1") (pinfunction "1_1") (pintype "passive"))
      (node (ref "IC13") (pin "5") (pinfunction "VO_5") (pintype "bidirectional"))
      (node (ref "IC4") (pin "5") (pinfunction "VDD_5") (pintype "bidirectional"))
      (node (ref "R59") (pin "2") (pinfunction "2_2") (pintype "passive"))
      (node (ref "TP18") (pin "1") (pinfunction "P$1_1") (pintype "bidirectional"))
      (node (ref "U2") (pin "19") (pinfunction "VCCO_6_19") (pintype "bidirectional"))
      (node (ref "U2") (pin "31") (pinfunction "VCCO_5_31") (pintype "bidirectional"))
      (node (ref "U2") (pin "46") (pinfunction "VCCO_4_46") (pintype "bidirectional"))
      (node (ref "U2") (pin "57") (pinfunction "VCCO_3_57") (pintype "bidirectional"))
      (node (ref "U2") (pin "6") (pinfunction "VCCO_7_6") (pintype "bidirectional"))
      (node (ref "U2") (pin "70") (pinfunction "VCCO_2_70") (pintype "bidirectional"))
      (node (ref "U2") (pin "83") (pinfunction "VCCO_1_83") (pintype "bidirectional"))
      (node (ref "U2") (pin "94") (pinfunction "VCCO_0_94") (pintype "bidirectional"))
    )
    (net (code "6") (name "5V") (class "Default")
      (node (ref "C21") (pin "1") (pinfunction "1_1") (pintype "passive"))
      (node (ref "C22") (pin "1") (pinfunction "1_1") (pintype "passive"))
      (node (ref "C23") (pin "1") (pinfunction "1_1") (pintype "passive"))
      (node (ref "C24") (pin "1") (pinfunction "1_1") (pintype "passive"))
      (node (ref "C37") (pin "+") (pinfunction "+_+") (pintype "passive"))
      (node (ref "C38") (pin "+") (pinfunction "+_+") (pintype "passive"))
      (node (ref "C44") (pin "1") (pinfunction "1_1") (pintype "passive"))
      (node (ref "C46") (pin "1") (pinfunction "1_1") (pintype "passive"))
      (node (ref "C64") (pin "1") (pinfunction "1_1") (pintype "passive"))
      (node (ref "C71") (pin "1") (pinfunction "1_1") (pintype "passive"))
      (node (ref "C72") (pin "1") (pinfunction "1_1") (pintype "passive"))
      (node (ref "C73") (pin "+") (pinfunction "+_+") (pintype "passive"))
      (node (ref "D7") (pin "3") (pinfunction "C_3") (pintype "passive"))
      (node (ref "FB1") (pin "2") (pinfunction "B_2") (pintype "bidirectional"))
      (node (ref "FB2\\") (pin "2") (pinfunction "B_2") (pintype "bidirectional"))
      (node (ref "FB3") (pin "2") (pinfunction "B_2") (pintype "bidirectional"))
      (node (ref "IC1") (pin "10") (pinfunction "FB_10") (pintype "input"))
      (node (ref "IC1") (pin "2") (pinfunction "VOUT_2") (pintype "output"))
      (node (ref "IC10") (pin "20") (pinfunction "VDD_20") (pintype "bidirectional"))
      (node (ref "IC105") (pin "1") (pinfunction "VIN_1") (pintype "bidirectional"))
      (node (ref "IC106") (pin "1") (pinfunction "VIN_1") (pintype "bidirectional"))
      (node (ref "IC11") (pin "14") (pinfunction "VDD_14") (pintype "bidirectional"))
      (node (ref "IC13") (pin "1") (pinfunction "VIN_1") (pintype "bidirectional"))
      (node (ref "IC14") (pin "8") (pinfunction "V+_8") (pintype "bidirectional"))
      (node (ref "IC3") (pin "1") (pinfunction "VIN_1") (pintype "bidirectional"))
      (node (ref "IC3") (pin "3") (pinfunction "VC_3") (pintype "bidirectional"))
      (node (ref "IC5") (pin "8") (pinfunction "V+_8") (pintype "bidirectional"))
      (node (ref "IC6") (pin "4") (pinfunction "V+_4") (pintype "bidirectional"))
      (node (ref "IC8") (pin "11") (pinfunction "VDDD0_11") (pintype "bidirectional"))
      (node (ref "IC8") (pin "13") (pinfunction "VDDD1_13") (pintype "bidirectional"))
      (node (ref "IC9") (pin "20") (pinfunction "VDD_20") (pintype "bidirectional"))
      (node (ref "R47") (pin "1") (pinfunction "1_1") (pintype "passive"))
      (node (ref "R52") (pin "2") (pinfunction "2_2") (pintype "passive"))
      (node (ref "R9") (pin "2") (pinfunction "2_2") (pintype "passive"))
      (node (ref "RLY1") (pin "1") (pinfunction "P$1_1") (pintype "passive"))
      (node (ref "TP10") (pin "1") (pinfunction "P$1_1") (pintype "bidirectional"))
    )
    (net (code "7") (name "1356_CRYSTAL") (class "Default")
      (node (ref "C3") (pin "1") (pinfunction "1_1") (pintype "passive"))
      (node (ref "R1") (pin "2") (pinfunction "2_2") (pintype "passive"))
      (node (ref "R2") (pin "2") (pinfunction "2_2") (pintype "passive"))
      (node (ref "U2") (pin "89") (pinfunction "L32P_0/GCLK6_89") (pintype "bidirectional"))
      (node (ref "U2") (pin "90") (pinfunction "L32N_0/GCLK7_90") (pintype "bidirectional"))
      (node (ref "XT1") (pin "B") (pinfunction "B_B") (pintype "bidirectional"))
    )
    (net (code "8") (name "ADC1") (class "Default")
      (node (ref "IC8") (pin "3") (pinfunction "D1_3") (pintype "bidirectional"))
      (node (ref "U2") (pin "38") (pinfunction "L32P_4/GCLK0_38") (pintype "bidirectional"))
    )
    (net (code "9") (name "ADC2") (class "Default")
      (node (ref "IC8") (pin "4") (pinfunction "D2_4") (pintype "bidirectional"))
      (node (ref "U2") (pin "37") (pinfunction "L32N_5/GCLK3_37") (pintype "bidirectional"))
    )
    (net (code "10") (name "ADC3") (class "Default")
      (node (ref "IC8") (pin "5") (pinfunction "D3_5") (pintype "bidirectional"))
      (node (ref "U2") (pin "36") (pinfunction "L32P_5/GCLK2_36") (pintype "bidirectional"))
    )
    (net (code "11") (name "ADC4") (class "Default")
      (node (ref "IC8") (pin "6") (pinfunction "D4_6") (pintype "bidirectional"))
      (node (ref "U2") (pin "35") (pinfunction "L31N_5/D4_35") (pintype "bidirectional"))
    )
    (net (code "12") (name "ADC5") (class "Default")
      (node (ref "IC8") (pin "7") (pinfunction "D5_7") (pintype "bidirectional"))
      (node (ref "U2") (pin "34") (pinfunction "L31P_5/D5_34") (pintype "bidirectional"))
    )
    (net (code "13") (name "ADC6") (class "Default")
      (node (ref "IC8") (pin "8") (pinfunction "D6_8") (pintype "bidirectional"))
      (node (ref "U2") (pin "32") (pinfunction "L28N_5/D6_32") (pintype "bidirectional"))
    )
    (net (code "14") (name "ADC7") (class "Default")
      (node (ref "IC8") (pin "9") (pinfunction "D7_9") (pintype "bidirectional"))
      (node (ref "U2") (pin "30") (pinfunction "L28P_5/D7_30") (pintype "bidirectional"))
    )
    (net (code "15") (name "ADC8") (class "Default")
      (node (ref "IC8") (pin "10") (pinfunction "MSB-D8_10") (pintype "bidirectional"))
      (node (ref "U2") (pin "28") (pinfunction "L01N_5/RDWR_B_28") (pintype "bidirectional"))
    )
    (net (code "16") (name "ADC_CLK") (class "Default")
      (node (ref "ADC_CLK_TP") (pin "1") (pinfunction "P$1_1") (pintype "bidirectional"))
      (node (ref "IC8") (pin "12") (pinfunction "CLK_12") (pintype "bidirectional"))
      (node (ref "U2") (pin "27") (pinfunction "L01P_5/CS_B_27") (pintype "bidirectional"))
    )
    (net (code "17") (name "ADC_IN") (class "Default")
      (node (ref "IC11") (pin "10") (pinfunction "B4_10") (pintype "passive"))
      (node (ref "IC11") (pin "2") (pinfunction "B1_2") (pintype "passive"))
      (node (ref "IC11") (pin "3") (pinfunction "B2_3") (pintype "passive"))
      (node (ref "IC11") (pin "9") (pinfunction "B3_9") (pintype "passive"))
      (node (ref "IC8") (pin "19") (pinfunction "ANALOGIN_19") (pintype "bidirectional"))
      (node (ref "TP1") (pin "1") (pinfunction "P$1_1") (pintype "bidirectional"))
    )
    (net (code "18") (name "ADC_NOE") (class "Default")
      (node (ref "ADC_NOE_TP") (pin "1") (pinfunction "P$1_1") (pintype "bidirectional"))
      (node (ref "IC8") (pin "1") (pinfunction "NOE_1") (pintype "bidirectional"))
      (node (ref "R47") (pin "2") (pinfunction "2_2") (pintype "passive"))
      (node (ref "U2") (pin "49") (pinfunction "L01P_4/VRN_4_49") (pintype "bidirectional"))
    )
    (net (code "19") (name "AMPL_HI") (class "Default")
      (node (ref "JP_AH") (pin "2") (pinfunction "2_2") (pintype "passive"))
      (node (ref "R41") (pin "2") (pinfunction "2_2") (pintype "passive"))
      (node (ref "R42") (pin "2") (pinfunction "2_2") (pintype "passive"))
    )
    (net (code "20") (name "AMPL_HI1") (class "Default")
      (node (ref "IC2") (pin "14") (pinfunction "PA0/WKUP/USART2_CTS/ADC123_IN0/TIM2_CH1_ETR/TIM5_CH1/TIME8_ETR_14") (pintype "bidirectional"))
      (node (ref "JP_AH") (pin "1") (pinfunction "1_1") (pintype "passive"))
      (node (ref "TP52") (pin "1") (pinfunction "P$1_1") (pintype "bidirectional"))
    )
    (net (code "21") (name "AMPL_LO") (class "Default")
      (node (ref "JP_AL") (pin "2") (pinfunction "2_2") (pintype "passive"))
      (node (ref "R30") (pin "2") (pinfunction "2_2") (pintype "passive"))
      (node (ref "R31") (pin "2") (pinfunction "2_2") (pintype "passive"))
    )
    (net (code "22") (name "AMPL_LO1") (class "Default")
      (node (ref "IC2") (pin "15") (pinfunction "PA1/USART2_RTS/ADC123_IN1/TIM5_CH2/TIM2_CH2_15") (pintype "bidirectional"))
      (node (ref "JP_AL") (pin "1") (pinfunction "1_1") (pintype "passive"))
      (node (ref "TP53") (pin "1") (pinfunction "P$1_1") (pintype "bidirectional"))
    )
    (net (code "23") (name "ANT_HI") (class "Default")
      (node (ref "C35") (pin "1") (pinfunction "1_1") (pintype "passive"))
      (node (ref "C36") (pin "1") (pinfunction "1_1") (pintype "passive"))
      (node (ref "RLY1") (pin "4") (pinfunction "COM_4") (pintype "passive"))
      (node (ref "SV2") (pin "4") (pinfunction "PIN4_4") (pintype "passive"))
      (node (ref "TP3") (pin "1") (pinfunction "P$1_1") (pintype "bidirectional"))
    )
    (net (code "24") (name "ANT_LO") (class "Default")
      (node (ref "C20") (pin "1") (pinfunction "1_1") (pintype "passive"))
      (node (ref "C39") (pin "1") (pinfunction "1_1") (pintype "passive"))
      (node (ref "RLY1") (pin "9") (pinfunction "COM_9") (pintype "passive"))
      (node (ref "SV2") (pin "2") (pinfunction "PIN2_2") (pintype "passive"))
      (node (ref "TP2") (pin "1") (pinfunction "P$1_1") (pintype "bidirectional"))
    )
    (net (code "25") (name "BOOT0_") (class "Default")
      (node (ref "JP4") (pin "7") (pinfunction "7_7") (pintype "passive"))
      (node (ref "R4") (pin "1") (pinfunction "1_1") (pintype "passive"))
    )
    (net (code "26") (name "CROSS_HI") (class "Default")
      (node (ref "CROSS_HI_TP") (pin "1") (pinfunction "P$1_1") (pintype "bidirectional"))
      (node (ref "IC5") (pin "6") (pinfunction "OUT_6") (pintype "output"))
      (node (ref "R44") (pin "1") (pinfunction "1_1") (pintype "passive"))
    )
    (net (code "27") (name "CROSS_LO") (class "Default")
      (node (ref "CROSS_LO_TP") (pin "1") (pinfunction "P$1_1") (pintype "bidirectional"))
      (node (ref "IC5") (pin "7") (pinfunction "OUT_7") (pintype "output"))
      (node (ref "R39") (pin "1") (pinfunction "1_1") (pintype "passive"))
    )
    (net (code "28") (name "DB2") (class "Default")
      (node (ref "SJ1") (pin "2") (pinfunction "2_2") (pintype "passive"))
      (node (ref "U3") (pin "20") (pinfunction "D2/I2C_SDA_20") (pintype "bidirectional"))
    )
    (net (code "29") (name "DBG") (class "Default")
      (node (ref "DBG_TP") (pin "1") (pinfunction "P$1_1") (pintype "bidirectional"))
      (node (ref "U2") (pin "75") (pinfunction "L01N_2/VRP_2_75") (pintype "bidirectional"))
    )
    (net (code "30") (name "D{slash}C") (class "Default")
      (node (ref "IC2") (pin "59") (pinfunction "PB7/I2C1_SDA/FSMC_NADV/TIM4_CH2/USART1_RX/FT_59") (pintype "bidirectional"))
      (node (ref "TP30") (pin "1") (pinfunction "P$1_1") (pintype "bidirectional"))
      (node (ref "U3") (pin "15") (pinfunction "DC/I2C_SA0_15") (pintype "input"))
    )
    (net (code "31") (name "FPGA_CCLK") (class "Default")
      (node (ref "IC2") (pin "41") (pinfunction "PA8/USART1_CK/TIM1_CH1/MCO/FT_41") (pintype "bidirectional"))
      (node (ref "TP25") (pin "1") (pinfunction "P$1_1") (pintype "bidirectional"))
      (node (ref "U2") (pin "52") (pinfunction "CCLK_52") (pintype "bidirectional"))
    )
    (net (code "32") (name "FPGA_DIN") (class "Default")
      (node (ref "IC2") (pin "42") (pinfunction "PA9/USART1_TX/TIM1_CH2/FT_42") (pintype "bidirectional"))
      (node (ref "TP26") (pin "1") (pinfunction "P$1_1") (pintype "bidirectional"))
      (node (ref "U2") (pin "48") (pinfunction "L27N_4/DIN/DO_48") (pintype "bidirectional"))
    )
    (net (code "33") (name "FPGA_DONE") (class "Default")
      (node (ref "IC2") (pin "26") (pinfunction "PB0/ADC12_IN8/TIM3_CH3/TIM8_CH2N/TIM1_CH2N_26") (pintype "bidirectional"))
      (node (ref "TP35") (pin "1") (pinfunction "P$1_1") (pintype "bidirectional"))
      (node (ref "U2") (pin "51") (pinfunction "DONE_51") (pintype "bidirectional"))
    )
    (net (code "34") (name "FPGA_DOUT") (class "Default")
      (node (ref "FPGA_DOUT_TP") (pin "1") (pinfunction "P$1_1") (pintype "bidirectional"))
      (node (ref "IC2") (pin "52") (pinfunction "PC11/UART4_RX/SDIO_D3/USART3_RX/FT_52") (pintype "bidirectional"))
      (node (ref "U2") (pin "40") (pinfunction "L31P_4/DOUT/BUSY_40") (pintype "bidirectional"))
    )
    (net (code "35") (name "FPGA_NINIT") (class "Default")
      (node (ref "FPGA_NINIT_TP") (pin "1") (pinfunction "P$1_1") (pintype "bidirectional"))
      (node (ref "IC2") (pin "38") (pinfunction "PC7/I2S3_MCK/TIM8_CH2/SDIO_D7/TIM3_CH2/FT_38") (pintype "bidirectional"))
      (node (ref "R59") (pin "1") (pinfunction "1_1") (pintype "passive"))
      (node (ref "U2") (pin "42") (pinfunction "L31N_4/INIT_B_42") (pintype "bidirectional"))
    )
    (net (code "36") (name "FPGA_NPROGRAM") (class "Default")
      (node (ref "IC2") (pin "23") (pinfunction "PA7/SPI1_MOSI/TIM8_CH1N/ADC12_IN7/TIM3_CH2/TIM1_CH1N_23") (pintype "bidirectional"))
      (node (ref "TP24") (pin "1") (pinfunction "P$1_1") (pintype "bidirectional"))
      (node (ref "U2") (pin "99") (pinfunction "PROG_B_99") (pintype "bidirectional"))
    )
    (net (code "37") (name "FPGA_ON") (class "Default")
      (node (ref "IC105") (pin "3") (pinfunction "EN_3") (pintype "bidirectional"))
      (node (ref "IC106") (pin "3") (pinfunction "EN_3") (pintype "bidirectional"))
      (node (ref "IC13") (pin "3") (pinfunction "VC_3") (pintype "bidirectional"))
      (node (ref "IC2") (pin "30") (pinfunction "PB11/I2C2_SDA/USART3_RX/TIM2_CH4/FT_30") (pintype "bidirectional"))
      (node (ref "R102") (pin "1") (pinfunction "1_1") (pintype "passive"))
      (node (ref "R23") (pin "2") (pinfunction "2_2") (pintype "passive"))
      (node (ref "TP22") (pin "1") (pinfunction "P$1_1") (pintype "bidirectional"))
    )
    (net (code "38") (name "FPGA_TCK") (class "Default")
      (node (ref "SV5") (pin "4") (pinfunction "4_4") (pintype "passive"))
      (node (ref "U2") (pin "77") (pinfunction "TCK_77") (pintype "bidirectional"))
    )
    (net (code "39") (name "FPGA_TDI") (class "Default")
      (node (ref "SV5") (pin "2") (pinfunction "2_2") (pintype "passive"))
      (node (ref "U2") (pin "100") (pinfunction "TDI_100") (pintype "bidirectional"))
    )
    (net (code "40") (name "FPGA_TDO") (class "Default")
      (node (ref "SV5") (pin "3") (pinfunction "3_3") (pintype "passive"))
      (node (ref "U2") (pin "76") (pinfunction "TDO_76") (pintype "bidirectional"))
    )
    (net (code "41") (name "FPGA_TMS") (class "Default")
      (node (ref "SV5") (pin "1") (pinfunction "1_1") (pintype "passive"))
      (node (ref "U2") (pin "78") (pinfunction "TMS_78") (pintype "bidirectional"))
    )
    (net (code "42") (name "GND") (class "Default")
      (node (ref "BAT1") (pin "GND") (pinfunction "-_GND") (pintype "power_in"))
      (node (ref "C1") (pin "2") (pinfunction "2_2") (pintype "passive"))
      (node (ref "C10") (pin "2") (pinfunction "2_2") (pintype "passive"))
      (node (ref "C11") (pin "2") (pinfunction "2_2") (pintype "passive"))
      (node (ref "C15") (pin "2") (pinfunction "2_2") (pintype "passive"))
      (node (ref "C18") (pin "2") (pinfunction "2_2") (pintype "passive"))
      (node (ref "C19") (pin "2") (pinfunction "2_2") (pintype "passive"))
      (node (ref "C2") (pin "2") (pinfunction "2_2") (pintype "passive"))
      (node (ref "C20") (pin "2") (pinfunction "2_2") (pintype "passive"))
      (node (ref "C206") (pin "2") (pinfunction "2_2") (pintype "passive"))
      (node (ref "C209") (pin "2") (pinfunction "2_2") (pintype "passive"))
      (node (ref "C21") (pin "2") (pinfunction "2_2") (pintype "passive"))
      (node (ref "C210") (pin "2") (pinfunction "2_2") (pintype "passive"))
      (node (ref "C211") (pin "2") (pinfunction "2_2") (pintype "passive"))
      (node (ref "C212") (pin "2") (pinfunction "2_2") (pintype "passive"))
      (node (ref "C22") (pin "2") (pinfunction "2_2") (pintype "passive"))
      (node (ref "C23") (pin "2") (pinfunction "2_2") (pintype "passive"))
      (node (ref "C24") (pin "2") (pinfunction "2_2") (pintype "passive"))
      (node (ref "C25") (pin "2") (pinfunction "2_2") (pintype "passive"))
      (node (ref "C26") (pin "2") (pinfunction "2_2") (pintype "passive"))
      (node (ref "C27") (pin "2") (pinfunction "2_2") (pintype "passive"))
      (node (ref "C28") (pin "2") (pinfunction "2_2") (pintype "passive"))
      (node (ref "C29") (pin "2") (pinfunction "2_2") (pintype "passive"))
      (node (ref "C3") (pin "2") (pinfunction "2_2") (pintype "passive"))
      (node (ref "C30") (pin "2") (pinfunction "2_2") (pintype "passive"))
      (node (ref "C31") (pin "2") (pinfunction "2_2") (pintype "passive"))
      (node (ref "C32") (pin "2") (pinfunction "2_2") (pintype "passive"))
      (node (ref "C33") (pin "2") (pinfunction "2_2") (pintype "passive"))
      (node (ref "C34") (pin "2") (pinfunction "2_2") (pintype "passive"))
      (node (ref "C35") (pin "2") (pinfunction "2_2") (pintype "passive"))
      (node (ref "C36") (pin "2") (pinfunction "2_2") (pintype "passive"))
      (node (ref "C37") (pin "-") (pinfunction "-_-") (pintype "passive"))
      (node (ref "C38") (pin "-") (pinfunction "-_-") (pintype "passive"))
      (node (ref "C39") (pin "2") (pinfunction "2_2") (pintype "passive"))
      (node (ref "C44") (pin "2") (pinfunction "2_2") (pintype "passive"))
      (node (ref "C45") (pin "2") (pinfunction "2_2") (pintype "passive"))
      (node (ref "C46") (pin "2") (pinfunction "2_2") (pintype "passive"))
      (node (ref "C47") (pin "2") (pinfunction "2_2") (pintype "passive"))
      (node (ref "C48") (pin "2") (pinfunction "2_2") (pintype "passive"))
      (node (ref "C49") (pin "2") (pinfunction "2_2") (pintype "passive"))
      (node (ref "C50") (pin "2") (pinfunction "2_2") (pintype "passive"))
      (node (ref "C51") (pin "2") (pinfunction "2_2") (pintype "passive"))
      (node (ref "C52") (pin "2") (pinfunction "2_2") (pintype "passive"))
      (node (ref "C53") (pin "1") (pinfunction "1_1") (pintype "passive"))
      (node (ref "C54") (pin "1") (pinfunction "1_1") (pintype "passive"))
      (node (ref "C55") (pin "C") (pinfunction "-_C") (pintype "passive"))
      (node (ref "C56") (pin "2") (pinfunction "2_2") (pintype "passive"))
      (node (ref "C57") (pin "2") (pinfunction "2_2") (pintype "passive"))
      (node (ref "C58") (pin "2") (pinfunction "2_2") (pintype "passive"))
      (node (ref "C59") (pin "2") (pinfunction "2_2") (pintype "passive"))
      (node (ref "C6") (pin "2") (pinfunction "2_2") (pintype "passive"))
      (node (ref "C60") (pin "2") (pinfunction "2_2") (pintype "passive"))
      (node (ref "C61") (pin "2") (pinfunction "2_2") (pintype "passive"))
      (node (ref "C62") (pin "2") (pinfunction "2_2") (pintype "passive"))
      (node (ref "C63") (pin "2") (pinfunction "2_2") (pintype "passive"))
      (node (ref "C64") (pin "2") (pinfunction "2_2") (pintype "passive"))
      (node (ref "C65") (pin "2") (pinfunction "2_2") (pintype "passive"))
      (node (ref "C66") (pin "2") (pinfunction "2_2") (pintype "passive"))
      (node (ref "C67") (pin "2") (pinfunction "2_2") (pintype "passive"))
      (node (ref "C68") (pin "-") (pinfunction "-_-") (pintype "passive"))
      (node (ref "C69") (pin "-") (pinfunction "-_-") (pintype "passive"))
      (node (ref "C7") (pin "2") (pinfunction "2_2") (pintype "passive"))
      (node (ref "C70") (pin "-") (pinfunction "-_-") (pintype "passive"))
      (node (ref "C71") (pin "2") (pinfunction "2_2") (pintype "passive"))
      (node (ref "C72") (pin "2") (pinfunction "2_2") (pintype "passive"))
      (node (ref "C73") (pin "-") (pinfunction "-_-") (pintype "passive"))
      (node (ref "C74") (pin "2") (pinfunction "2_2") (pintype "passive"))
      (node (ref "C75") (pin "2") (pinfunction "2_2") (pintype "passive"))
      (node (ref "C8") (pin "2") (pinfunction "2_2") (pintype "passive"))
      (node (ref "C9") (pin "1") (pinfunction "1_1") (pintype "passive"))
      (node (ref "D10") (pin "1") (pinfunction "A_1") (pintype "passive"))
      (node (ref "D11") (pin "1") (pinfunction "A_1") (pintype "passive"))
      (node (ref "D3") (pin "1") (pinfunction "A_1") (pintype "passive"))
      (node (ref "D6") (pin "1") (pinfunction "P$1_1") (pintype "passive"))
      (node (ref "IC1") (pin "4") (pinfunction "PGND_4") (pintype "power_in"))
      (node (ref "IC1") (pin "9") (pinfunction "GND_9") (pintype "power_in"))
      (node (ref "IC10") (pin "10") (pinfunction "VSS_10") (pintype "bidirectional"))
      (node (ref "IC105") (pin "2") (pinfunction "GND_2") (pintype "bidirectional"))
      (node (ref "IC106") (pin "2") (pinfunction "GND_2") (pintype "bidirectional"))
      (node (ref "IC11") (pin "7") (pinfunction "VSS_7") (pintype "bidirectional"))
      (node (ref "IC13") (pin "2") (pinfunction "GND_2") (pintype "bidirectional"))
      (node (ref "IC14") (pin "4") (pinfunction "V-_4") (pintype "bidirectional"))
      (node (ref "IC2") (pin "12") (pinfunction "VSSA_12") (pintype "power_in"))
      (node (ref "IC2") (pin "18") (pinfunction "VSS_18") (pintype "power_in"))
      (node (ref "IC2") (pin "31") (pinfunction "VSS_31") (pintype "power_in"))
      (node (ref "IC2") (pin "47") (pinfunction "VSS_47") (pintype "power_in"))
      (node (ref "IC2") (pin "63") (pinfunction "VSS_63") (pintype "power_in"))
      (node (ref "IC3") (pin "2") (pinfunction "GND_2") (pintype "bidirectional"))
      (node (ref "IC4") (pin "3") (pinfunction "VSS_3") (pintype "bidirectional"))
      (node (ref "IC5") (pin "2") (pinfunction "-IN_2") (pintype "input"))
      (node (ref "IC5") (pin "4") (pinfunction "-IN_4") (pintype "input"))
      (node (ref "IC5") (pin "5") (pinfunction "V-_5") (pintype "bidirectional"))
      (node (ref "IC6") (pin "11") (pinfunction "V-_11") (pintype "bidirectional"))
      (node (ref "IC6") (pin "12") (pinfunction "+IN_12") (pintype "input"))
      (node (ref "IC6") (pin "13") (pinfunction "-IN_13") (pintype "input"))
      (node (ref "IC7") (pin "3") (pinfunction "V-_3") (pintype "bidirectional"))
      (node (ref "IC8") (pin "2") (pinfunction "DGND0_2") (pintype "bidirectional"))
      (node (ref "IC8") (pin "20") (pinfunction "AGND0_20") (pintype "bidirectional"))
      (node (ref "IC8") (pin "21") (pinfunction "AGND1_21") (pintype "bidirectional"))
      (node (ref "IC8") (pin "24") (pinfunction "DGND1_24") (pintype "bidirectional"))
      (node (ref "IC9") (pin "10") (pinfunction "VSS_10") (pintype "bidirectional"))
      (node (ref "JP2") (pin "1") (pinfunction "1_1") (pintype "passive"))
      (node (ref "JP4") (pin "5") (pinfunction "5_5") (pintype "passive"))
      (node (ref "K1") (pin "1") (pinfunction "P_1") (pintype "passive"))
      (node (ref "K2") (pin "1") (pinfunction "P_1") (pintype "passive"))
      (node (ref "K3") (pin "1") (pinfunction "P_1") (pintype "passive"))
      (node (ref "LED3") (pin "C") (pinfunction "C_C") (pintype "passive"))
      (node (ref "Q1") (pin "2") (pinfunction "E_2") (pintype "bidirectional"))
      (node (ref "Q3") (pin "2") (pinfunction "E_2") (pintype "passive"))
      (node (ref "Q4") (pin "E") (pinfunction "E_E") (pintype "passive"))
      (node (ref "R10") (pin "1") (pinfunction "1_1") (pintype "passive"))
      (node (ref "R102") (pin "2") (pinfunction "2_2") (pintype "passive"))
      (node (ref "R11") (pin "1") (pinfunction "1_1") (pintype "passive"))
      (node (ref "R15") (pin "1") (pinfunction "1_1") (pintype "passive"))
      (node (ref "R23") (pin "1") (pinfunction "1_1") (pintype "passive"))
      (node (ref "R3") (pin "1") (pinfunction "1_1") (pintype "passive"))
      (node (ref "R31") (pin "1") (pinfunction "1_1") (pintype "passive"))
      (node (ref "R42") (pin "1") (pinfunction "1_1") (pintype "passive"))
      (node (ref "R54") (pin "1") (pinfunction "1_1") (pintype "passive"))
      (node (ref "R60") (pin "1") (pinfunction "1_1") (pintype "passive"))
      (node (ref "R67") (pin "1") (pinfunction "1_1") (pintype "passive"))
      (node (ref "S1") (pin "1") (pinfunction "O_1") (pintype "passive"))
      (node (ref "SV1") (pin "5") (pinfunction "GND/5_5") (pintype "bidirectional"))
      (node (ref "SV1") (pin "TAB0") (pinfunction "SHLD0_TAB0") (pintype "bidirectional"))
      (node (ref "SV1") (pin "TAB1") (pinfunction "SHLD1_TAB1") (pintype "bidirectional"))
      (node (ref "SV1") (pin "TAB2") (pinfunction "SHLD2_TAB2") (pintype "bidirectional"))
      (node (ref "SV1") (pin "TAB3") (pinfunction "SHLD3_TAB3") (pintype "bidirectional"))
      (node (ref "SV5") (pin "5") (pinfunction "5_5") (pintype "passive"))
      (node (ref "U$7") (pin "4") (pinfunction "~{EN}_4") (pintype "bidirectional"))
      (node (ref "U$7") (pin "5") (pinfunction "GND_5") (pintype "power_in"))
      (node (ref "U$7") (pin "9") (pinfunction "EP_9") (pintype "power_in"))
      (node (ref "U$7") (pin "V1") (pinfunction "V1_V1") (pintype "power_in"))
      (node (ref "U$9") (pin "1") (pinfunction "NEG_1") (pintype "power_in"))
      (node (ref "U2") (pin "10") (pinfunction "GND_10") (pintype "power_in"))
      (node (ref "U2") (pin "20") (pinfunction "GND_20") (pintype "power_in"))
      (node (ref "U2") (pin "29") (pinfunction "GND_29") (pintype "power_in"))
      (node (ref "U2") (pin "3") (pinfunction "GND_3") (pintype "power_in"))
      (node (ref "U2") (pin "41") (pinfunction "GND_41") (pintype "power_in"))
      (node (ref "U2") (pin "56") (pinfunction "GND_56") (pintype "power_in"))
      (node (ref "U2") (pin "66") (pinfunction "GND_66") (pintype "power_in"))
      (node (ref "U2") (pin "73") (pinfunction "GND_73") (pintype "power_in"))
      (node (ref "U2") (pin "82") (pinfunction "GND_82") (pintype "power_in"))
      (node (ref "U2") (pin "95") (pinfunction "GND_95") (pintype "power_in"))
      (node (ref "U3") (pin "1") (pinfunction "NC(GND)_1") (pintype "input"))
      (node (ref "U3") (pin "10") (pinfunction "BS0_10") (pintype "input"))
      (node (ref "U3") (pin "11") (pinfunction "BS1_11") (pintype "input"))
      (node (ref "U3") (pin "12") (pinfunction "BS2_12") (pintype "input"))
      (node (ref "U3") (pin "29") (pinfunction "VLSS_29") (pintype "power_in"))
      (node (ref "U3") (pin "30") (pinfunction "NC(GND)_30") (pintype "input"))
      (node (ref "U3") (pin "8") (pinfunction "VSS_8") (pintype "power_in"))
      (node (ref "U4") (pin "6") (pinfunction "GND_6") (pintype "bidirectional"))
      (node (ref "U4") (pin "CD1") (pinfunction "SHIELD_CD1") (pintype "bidirectional"))
      (node (ref "U4") (pin "CD2") (pinfunction "SHIELD_CD2") (pintype "bidirectional"))
      (node (ref "U4") (pin "GND1") (pinfunction "SHIELD_GND1") (pintype "bidirectional"))
      (node (ref "U4") (pin "GND3") (pinfunction "SHIELD_GND3") (pintype "bidirectional"))
      (node (ref "USB-MICRO") (pin "GND") (pinfunction "GND_GND") (pintype "bidirectional"))
    )
    (net (code "43") (name "JTAG_TCK") (class "Default")
      (node (ref "IC2") (pin "49") (pinfunction "PA14/JTCK/SWCLK/FT_49") (pintype "input"))
      (node (ref "JP4") (pin "4") (pinfunction "4_4") (pintype "passive"))
    )
    (net (code "44") (name "JTAG_TMS") (class "Default")
      (node (ref "IC2") (pin "46") (pinfunction "PA13/JTMS/SWDIO/FT_46") (pintype "input"))
      (node (ref "JP4") (pin "1") (pinfunction "1_1") (pintype "passive"))
    )
    (net (code "45") (name "JTRST") (class "Default")
      (node (ref "IC2") (pin "58") (pinfunction "PB6/I2C1_SCL/TIM4_CH1/USART1_TX/FT_58") (pintype "bidirectional"))
      (node (ref "TP31") (pin "1") (pinfunction "P$1_1") (pintype "bidirectional"))
    )
    (net (code "46") (name "LED_A") (class "Default")
      (node (ref "IC2") (pin "54") (pinfunction "PD2/TIM3_ETR/UART5_RX/SDIO_CMD/FT_54") (pintype "bidirectional"))
      (node (ref "LED_A_TP") (pin "1") (pinfunction "P$1_1") (pintype "bidirectional"))
      (node (ref "R65") (pin "1") (pinfunction "1_1") (pintype "passive"))
    )
    (net (code "47") (name "MISO") (class "Default")
      (node (ref "IC2") (pin "4") (pinfunction "PC15/OSC32_OUT_4") (pintype "bidirectional"))
      (node (ref "MISO_TP") (pin "1") (pinfunction "P$1_1") (pintype "bidirectional"))
      (node (ref "U2") (pin "15") (pinfunction "L24P_6_15") (pintype "bidirectional"))
    )
    (net (code "48") (name "MOSI") (class "Default")
      (node (ref "IC2") (pin "3") (pinfunction "PC14/OSC32_IN_3") (pintype "bidirectional"))
      (node (ref "MOSI_TP") (pin "1") (pinfunction "P$1_1") (pintype "bidirectional"))
      (node (ref "U2") (pin "14") (pinfunction "L40N_6_14") (pintype "bidirectional"))
    )
    (net (code "49") (name "MUXSEL_HIPKD") (class "Default")
      (node (ref "FPGA_NINIT_TP2") (pin "1") (pinfunction "P$1_1") (pintype "bidirectional"))
      (node (ref "IC11") (pin "12") (pinfunction "C4_12") (pintype "input"))
      (node (ref "IC2") (pin "40") (pinfunction "PC9/TIM8_CH4/SDIO_D1/TIM3_CH4/FT_40") (pintype "bidirectional"))
    )
    (net (code "50") (name "MUXSEL_HIRAW") (class "Default")
      (node (ref "IC11") (pin "6") (pinfunction "C3_6") (pintype "input"))
      (node (ref "IC2") (pin "28") (pinfunction "PB2/BOOT1/FT_28") (pintype "bidirectional"))
      (node (ref "TP33") (pin "1") (pinfunction "P$1_1") (pintype "bidirectional"))
    )
    (net (code "51") (name "MUXSEL_LOPKD") (class "Default")
      (node (ref "FPGA_NINIT_TP1") (pin "1") (pinfunction "P$1_1") (pintype "bidirectional"))
      (node (ref "IC11") (pin "5") (pinfunction "C2_5") (pintype "input"))
      (node (ref "IC2") (pin "39") (pinfunction "PC8/TIM8_CH3/SDIO_D0/TIM3_CH3/FT_39") (pintype "bidirectional"))
    )
    (net (code "52") (name "MUXSEL_LORAW") (class "Default")
      (node (ref "IC11") (pin "13") (pinfunction "C1_13") (pintype "input"))
      (node (ref "IC2") (pin "27") (pinfunction "PB1/ADC12_IN9/TIM3_CH4/TIM8_CH3N/TIM1_CH3N_27") (pintype "bidirectional"))
      (node (ref "TP34") (pin "1") (pinfunction "P$1_1") (pintype "bidirectional"))
    )
    (net (code "53") (name "N$58") (class "Default")
      (node (ref "SPARE_FPGA_TP") (pin "1") (pinfunction "P$1_1") (pintype "bidirectional"))
      (node (ref "U2") (pin "43") (pinfunction "L30P_4/D3_43") (pintype "bidirectional"))
    )
    (net (code "54") (name "NCS") (class "Default")
      (node (ref "IC2") (pin "53") (pinfunction "PC12/UART5_TX/SDIO_CK/USART3_CK/FT_53") (pintype "bidirectional"))
      (node (ref "NCS_TP") (pin "1") (pinfunction "P$1_1") (pintype "bidirectional"))
      (node (ref "U2") (pin "50") (pinfunction "L01N_4/VRP_4_50") (pintype "bidirectional"))
    )
    (net (code "55") (name "NRST") (class "Default")
      (node (ref "C56") (pin "1") (pinfunction "1_1") (pintype "passive"))
      (node (ref "IC2") (pin "7") (pinfunction "NRST_7") (pintype "input"))
      (node (ref "R5") (pin "2") (pinfunction "2_2") (pintype "passive"))
    )
    (net (code "56") (name "NTC") (class "Default")
      (node (ref "R43") (pin "1") (pinfunction "1_1") (pintype "passive"))
      (node (ref "TP16") (pin "1") (pinfunction "P$1_1") (pintype "bidirectional"))
      (node (ref "U$9") (pin "2") (pinfunction "NTC_2") (pintype "power_in"))
    )
    (net (code "57") (name "Net-(BAT1-+)") (class "Default")
      (node (ref "BAT1") (pin "PWR@1") (pinfunction "+_PWR@1") (pintype "power_in"))
      (node (ref "D4") (pin "1") (pinfunction "A_1") (pintype "passive"))
    )
    (net (code "58") (name "Net-(C16-Pad1)") (class "Default")
      (node (ref "C16") (pin "1") (pinfunction "1_1") (pintype "passive"))
      (node (ref "R16") (pin "2") (pinfunction "2_2") (pintype "passive"))
    )
    (net (code "59") (name "Net-(C42-Pad2)") (class "Default")
      (node (ref "C42") (pin "2") (pinfunction "2_2") (pintype "passive"))
      (node (ref "R35") (pin "1") (pinfunction "1_1") (pintype "passive"))
    )
    (net (code "60") (name "Net-(C43-Pad2)") (class "Default")
      (node (ref "C43") (pin "2") (pinfunction "2_2") (pintype "passive"))
      (node (ref "R32") (pin "1") (pinfunction "1_1") (pintype "passive"))
    )
    (net (code "61") (name "Net-(C57-Pad1)") (class "Default")
      (node (ref "C57") (pin "1") (pinfunction "1_1") (pintype "passive"))
      (node (ref "LED2") (pin "C") (pinfunction "C_C") (pintype "passive"))
      (node (ref "R24") (pin "1") (pinfunction "1_1") (pintype "passive"))
    )
    (net (code "62") (name "Net-(C58-Pad1)") (class "Default")
      (node (ref "C58") (pin "1") (pinfunction "1_1") (pintype "passive"))
      (node (ref "LED1") (pin "C") (pinfunction "C_C") (pintype "passive"))
      (node (ref "R25") (pin "1") (pinfunction "1_1") (pintype "passive"))
    )
    (net (code "63") (name "Net-(D1-A)") (class "Default")
      (node (ref "D1") (pin "1") (pinfunction "A_1") (pintype "passive"))
      (node (ref "R20") (pin "1") (pinfunction "1_1") (pintype "passive"))
      (node (ref "RLY1") (pin "10") (pinfunction "NC_10") (pintype "passive"))
    )
    (net (code "64") (name "Net-(D1-C)") (class "Default")
      (node (ref "C11") (pin "1") (pinfunction "1_1") (pintype "passive"))
      (node (ref "C12") (pin "1") (pinfunction "1_1") (pintype "passive"))
      (node (ref "D1") (pin "3") (pinfunction "C_3") (pintype "passive"))
      (node (ref "D11") (pin "3") (pinfunction "C_3") (pintype "passive"))
      (node (ref "R11") (pin "2") (pinfunction "2_2") (pintype "passive"))
      (node (ref "R30") (pin "1") (pinfunction "1_1") (pintype "passive"))
    )
    (net (code "65") (name "Net-(D2-A)") (class "Default")
      (node (ref "C14") (pin "2") (pinfunction "2_2") (pintype "passive"))
      (node (ref "D2") (pin "1") (pinfunction "A_1") (pintype "passive"))
      (node (ref "D3") (pin "3") (pinfunction "C_3") (pintype "passive"))
    )
    (net (code "66") (name "Net-(D4-C)") (class "Default")
      (node (ref "C9") (pin "2") (pinfunction "2_2") (pintype "passive"))
      (node (ref "D4") (pin "3") (pinfunction "C_3") (pintype "passive"))
      (node (ref "D5") (pin "3") (pinfunction "C_3") (pintype "passive"))
      (node (ref "IC2") (pin "1") (pinfunction "VBAT_1") (pintype "passive"))
    )
    (net (code "67") (name "Net-(D6-P$4)") (class "Default")
      (node (ref "D6") (pin "4") (pinfunction "P$4_4") (pintype "passive"))
      (node (ref "F1") (pin "2") (pinfunction "2_2") (pintype "passive"))
      (node (ref "SV1") (pin "1") (pinfunction "VBUS/1_1") (pintype "bidirectional"))
      (node (ref "USB-MICRO") (pin "VBUS") (pinfunction "VBUS_VBUS") (pintype "bidirectional"))
    )
    (net (code "68") (name "Net-(D7-A)") (class "Default")
      (node (ref "D7") (pin "1") (pinfunction "A_1") (pintype "passive"))
      (node (ref "Q1") (pin "3") (pinfunction "C_3") (pintype "bidirectional"))
      (node (ref "RLY1") (pin "12") (pinfunction "P$2_12") (pintype "passive"))
    )
    (net (code "69") (name "Net-(D10-C)") (class "Default")
      (node (ref "C15") (pin "1") (pinfunction "1_1") (pintype "passive"))
      (node (ref "D10") (pin "3") (pinfunction "C_3") (pintype "passive"))
      (node (ref "D2") (pin "3") (pinfunction "C_3") (pintype "passive"))
      (node (ref "R15") (pin "2") (pinfunction "2_2") (pintype "passive"))
      (node (ref "R16") (pin "1") (pinfunction "1_1") (pintype "passive"))
      (node (ref "R41") (pin "1") (pinfunction "1_1") (pintype "passive"))
    )
    (net (code "70") (name "Net-(FB1-A)") (class "Default")
      (node (ref "C65") (pin "1") (pinfunction "1_1") (pintype "passive"))
      (node (ref "C70") (pin "+") (pinfunction "+_+") (pintype "passive"))
      (node (ref "FB1") (pin "1") (pinfunction "A_1") (pintype "bidirectional"))
      (node (ref "IC8") (pin "18") (pinfunction "VDDA2_18") (pintype "bidirectional"))
    )
    (net (code "71") (name "Net-(FB2\\-A)") (class "Default")
      (node (ref "C67") (pin "1") (pinfunction "1_1") (pintype "passive"))
      (node (ref "C69") (pin "+") (pinfunction "+_+") (pintype "passive"))
      (node (ref "FB2\\") (pin "1") (pinfunction "A_1") (pintype "bidirectional"))
      (node (ref "IC8") (pin "14") (pinfunction "VDDA0_14") (pintype "bidirectional"))
    )
    (net (code "72") (name "Net-(FB3-A)") (class "Default")
      (node (ref "C66") (pin "1") (pinfunction "1_1") (pintype "passive"))
      (node (ref "C68") (pin "+") (pinfunction "+_+") (pintype "passive"))
      (node (ref "FB3") (pin "1") (pinfunction "A_1") (pintype "bidirectional"))
      (node (ref "IC8") (pin "15") (pinfunction "VDDA1_15") (pintype "bidirectional"))
    )
    (net (code "73") (name "Net-(IC1B-L)") (class "Default")
      (node (ref "IC1") (pin "3") (pinfunction "L_3") (pintype "input"))
      (node (ref "L2") (pin "P$2") (pinfunction "2_P$2") (pintype "passive"))
    )
    (net (code "74") (name "Net-(IC1B-UVLO)") (class "Default")
      (node (ref "IC1") (pin "7") (pinfunction "UVLO_7") (pintype "input"))
      (node (ref "R55") (pin "1") (pinfunction "1_1") (pintype "passive"))
      (node (ref "R60") (pin "2") (pinfunction "2_2") (pintype "passive"))
    )
    (net (code "75") (name "Net-(IC1B-VAUX)") (class "Default")
      (node (ref "C63") (pin "1") (pinfunction "1_1") (pintype "passive"))
      (node (ref "IC1") (pin "1") (pinfunction "VAUX_1") (pintype "bidirectional"))
    )
    (net (code "76") (name "Net-(IC2-BOOT0)") (class "Default")
      (node (ref "IC2") (pin "60") (pinfunction "BOOT0_60") (pintype "input"))
      (node (ref "R4") (pin "2") (pinfunction "2_2") (pintype "passive"))
    )
    (net (code "77") (name "Net-(IC2-PA11{slash}UART1CTS{slash}CNRX{slash}TIM1CH4{slash}USBD-{slash}FT)") (class "Default")
      (node (ref "IC2") (pin "44") (pinfunction "PA11/UART1CTS/CNRX/TIM1CH4/USBD-/FT_44") (pintype "bidirectional"))
      (node (ref "R7") (pin "2") (pinfunction "2_2") (pintype "passive"))
    )
    (net (code "78") (name "Net-(IC2-PA12{slash}UART1RTS{slash}CNTX{slash}TIM1ETR{slash}USBD+{slash}FT)") (class "Default")
      (node (ref "IC2") (pin "45") (pinfunction "PA12/UART1RTS/CNTX/TIM1ETR/USBD+/FT_45") (pintype "bidirectional"))
      (node (ref "R8") (pin "2") (pinfunction "2_2") (pintype "passive"))
    )
    (net (code "79") (name "Net-(IC2-PC3{slash}ADC123_IN13)") (class "Default")
      (node (ref "IC2") (pin "11") (pinfunction "PC3/ADC123_IN13_11") (pintype "bidirectional"))
      (node (ref "JP_AH") (pin "3") (pinfunction "3_3") (pintype "passive"))
    )
    (net (code "80") (name "Net-(IC2-PC4{slash}ADC12_IN14)") (class "Default")
      (node (ref "IC2") (pin "24") (pinfunction "PC4/ADC12_IN14_24") (pintype "bidirectional"))
      (node (ref "JP_AL") (pin "3") (pinfunction "3_3") (pintype "passive"))
    )
    (net (code "81") (name "Net-(IC2-PD0{slash}OSC_IN{slash}FSMC_D2{slash}CAN_RX{slash}FT)") (class "Default")
      (node (ref "C53") (pin "2") (pinfunction "2_2") (pintype "passive"))
      (node (ref "IC2") (pin "5") (pinfunction "PD0/OSC_IN/FSMC_D2/CAN_RX/FT_5") (pintype "bidirectional"))
      (node (ref "Y1") (pin "P$1") (pinfunction "1_P$1") (pintype "passive"))
    )
    (net (code "82") (name "Net-(IC2-PD1{slash}OSC_OUT{slash}FSMC_D3{slash}CAN_TX{slash}FT)") (class "Default")
      (node (ref "IC2") (pin "6") (pinfunction "PD1/OSC_OUT/FSMC_D3/CAN_TX/FT_6") (pintype "bidirectional"))
      (node (ref "R6") (pin "2") (pinfunction "2_2") (pintype "passive"))
    )
    (net (code "83") (name "Net-(IC3-NR)") (class "Default")
      (node (ref "C74") (pin "1") (pinfunction "1_1") (pintype "passive"))
      (node (ref "IC3") (pin "4") (pinfunction "NR_4") (pintype "bidirectional"))
    )
    (net (code "84") (name "Net-(IC4-A)") (class "Default")
      (node (ref "C2") (pin "1") (pinfunction "1_1") (pintype "passive"))
      (node (ref "IC4") (pin "2") (pinfunction "A_2") (pintype "bidirectional"))
      (node (ref "R1") (pin "1") (pinfunction "1_1") (pintype "passive"))
      (node (ref "XT1") (pin "A") (pinfunction "A_A") (pintype "bidirectional"))
    )
    (net (code "85") (name "Net-(IC4-Y)") (class "Default")
      (node (ref "IC4") (pin "4") (pinfunction "Y_4") (pintype "bidirectional"))
      (node (ref "R2") (pin "1") (pinfunction "1_1") (pintype "passive"))
    )
    (net (code "86") (name "Net-(IC5A-+IN)") (class "Default")
      (node (ref "IC5") (pin "1") (pinfunction "+IN_1") (pintype "input"))
      (node (ref "R20") (pin "2") (pinfunction "2_2") (pintype "passive"))
    )
    (net (code "87") (name "Net-(IC5B-+IN)") (class "Default")
      (node (ref "IC5") (pin "3") (pinfunction "+IN_3") (pintype "input"))
      (node (ref "R21") (pin "2") (pinfunction "2_2") (pintype "passive"))
    )
    (net (code "88") (name "Net-(IC6A-+IN)") (class "Default")
      (node (ref "IC6") (pin "3") (pinfunction "+IN_3") (pintype "input"))
      (node (ref "R10") (pin "2") (pinfunction "2_2") (pintype "passive"))
      (node (ref "R9") (pin "1") (pinfunction "1_1") (pintype "passive"))
    )
    (net (code "89") (name "Net-(IC6B-+IN)") (class "Default")
      (node (ref "C12") (pin "2") (pinfunction "2_2") (pintype "passive"))
      (node (ref "IC6") (pin "5") (pinfunction "+IN_5") (pintype "input"))
      (node (ref "R12") (pin "2") (pinfunction "2_2") (pintype "passive"))
    )
    (net (code "90") (name "Net-(IC6B--IN)") (class "Default")
      (node (ref "C13") (pin "1") (pinfunction "1_1") (pintype "passive"))
      (node (ref "IC6") (pin "6") (pinfunction "-IN_6") (pintype "input"))
      (node (ref "R13") (pin "2") (pinfunction "2_2") (pintype "passive"))
      (node (ref "R14") (pin "1") (pinfunction "1_1") (pintype "passive"))
    )
    (net (code "91") (name "Net-(IC6C-+IN)") (class "Default")
      (node (ref "C16") (pin "2") (pinfunction "2_2") (pintype "passive"))
      (node (ref "IC6") (pin "10") (pinfunction "+IN_10") (pintype "input"))
      (node (ref "R17") (pin "2") (pinfunction "2_2") (pintype "passive"))
      (node (ref "R36") (pin "2") (pinfunction "2_2") (pintype "passive"))
      (node (ref "R37") (pin "2") (pinfunction "2_2") (pintype "passive"))
    )
    (net (code "92") (name "Net-(IC6C--IN)") (class "Default")
      (node (ref "C17") (pin "1") (pinfunction "1_1") (pintype "passive"))
      (node (ref "IC6") (pin "9") (pinfunction "-IN_9") (pintype "input"))
      (node (ref "R18") (pin "1") (pinfunction "1_1") (pintype "passive"))
      (node (ref "R19") (pin "2") (pinfunction "2_2") (pintype "passive"))
    )
    (net (code "93") (name "Net-(IC7-OUT)") (class "Default")
      (node (ref "IC7") (pin "1") (pinfunction "OUT_1") (pintype "bidirectional"))
      (node (ref "R5") (pin "1") (pinfunction "1_1") (pintype "passive"))
    )
    (net (code "94") (name "Net-(IC8-REFB)") (class "Default")
      (node (ref "C18") (pin "1") (pinfunction "1_1") (pintype "passive"))
      (node (ref "IC8") (pin "23") (pinfunction "REFB_23") (pintype "bidirectional"))
      (node (ref "R53") (pin "1") (pinfunction "1_1") (pintype "passive"))
      (node (ref "R54") (pin "2") (pinfunction "2_2") (pintype "passive"))
    )
    (net (code "95") (name "Net-(IC8-REFT)") (class "Default")
      (node (ref "C19") (pin "1") (pinfunction "1_1") (pintype "passive"))
      (node (ref "IC8") (pin "17") (pinfunction "REFT_17") (pintype "bidirectional"))
      (node (ref "R52") (pin "1") (pinfunction "1_1") (pintype "passive"))
      (node (ref "R53") (pin "2") (pinfunction "2_2") (pintype "passive"))
    )
    (net (code "96") (name "Net-(IC9-1Y1)") (class "Default")
      (node (ref "IC9") (pin "12") (pinfunction "1Y4_12") (pintype "bidirectional"))
      (node (ref "IC9") (pin "14") (pinfunction "1Y3_14") (pintype "bidirectional"))
      (node (ref "IC9") (pin "16") (pinfunction "1Y2_16") (pintype "bidirectional"))
      (node (ref "IC9") (pin "18") (pinfunction "1Y1_18") (pintype "bidirectional"))
      (node (ref "R27") (pin "1") (pinfunction "1_1") (pintype "passive"))
    )
    (net (code "97") (name "Net-(IC9-2Y1)") (class "Default")
      (node (ref "IC9") (pin "9") (pinfunction "2Y1_9") (pintype "bidirectional"))
      (node (ref "R45") (pin "1") (pinfunction "1_1") (pintype "passive"))
    )
    (net (code "98") (name "Net-(IC9-2Y2)") (class "Default")
      (node (ref "IC9") (pin "3") (pinfunction "2Y4_3") (pintype "bidirectional"))
      (node (ref "IC9") (pin "5") (pinfunction "2Y3_5") (pintype "bidirectional"))
      (node (ref "IC9") (pin "7") (pinfunction "2Y2_7") (pintype "bidirectional"))
      (node (ref "R22") (pin "1") (pinfunction "1_1") (pintype "passive"))
    )
    (net (code "99") (name "Net-(IC10-1Y1)") (class "Default")
      (node (ref "IC10") (pin "12") (pinfunction "1Y4_12") (pintype "bidirectional"))
      (node (ref "IC10") (pin "14") (pinfunction "1Y3_14") (pintype "bidirectional"))
      (node (ref "IC10") (pin "16") (pinfunction "1Y2_16") (pintype "bidirectional"))
      (node (ref "IC10") (pin "18") (pinfunction "1Y1_18") (pintype "bidirectional"))
      (node (ref "R28") (pin "1") (pinfunction "1_1") (pintype "passive"))
    )
    (net (code "100") (name "Net-(IC10-2Y1)") (class "Default")
      (node (ref "IC10") (pin "9") (pinfunction "2Y1_9") (pintype "bidirectional"))
      (node (ref "R46") (pin "1") (pinfunction "1_1") (pintype "passive"))
    )
    (net (code "101") (name "Net-(IC10-2Y2)") (class "Default")
      (node (ref "IC10") (pin "3") (pinfunction "2Y4_3") (pintype "bidirectional"))
      (node (ref "IC10") (pin "5") (pinfunction "2Y3_5") (pintype "bidirectional"))
      (node (ref "IC10") (pin "7") (pinfunction "2Y2_7") (pintype "bidirectional"))
      (node (ref "R29") (pin "1") (pinfunction "1_1") (pintype "passive"))
    )
    (net (code "102") (name "Net-(IC11-A1)") (class "Default")
      (node (ref "C41") (pin "2") (pinfunction "2_2") (pintype "passive"))
      (node (ref "IC11") (pin "1") (pinfunction "A1_1") (pintype "passive"))
      (node (ref "IC14") (pin "7") (pinfunction "OUT_7") (pintype "output"))
      (node (ref "R34") (pin "2") (pinfunction "2_2") (pintype "passive"))
    )
    (net (code "103") (name "Net-(IC11-A2)") (class "Default")
      (node (ref "C13") (pin "2") (pinfunction "2_2") (pintype "passive"))
      (node (ref "IC11") (pin "4") (pinfunction "A2_4") (pintype "passive"))
      (node (ref "IC6") (pin "7") (pinfunction "OUT_7") (pintype "output"))
      (node (ref "R14") (pin "2") (pinfunction "2_2") (pintype "passive"))
    )
    (net (code "104") (name "Net-(IC11-A3)") (class "Default")
      (node (ref "C40") (pin "2") (pinfunction "2_2") (pintype "passive"))
      (node (ref "IC11") (pin "8") (pinfunction "A3_8") (pintype "passive"))
      (node (ref "IC14") (pin "1") (pinfunction "OUT_1") (pintype "output"))
      (node (ref "R33") (pin "2") (pinfunction "2_2") (pintype "passive"))
    )
    (net (code "105") (name "Net-(IC11-A4)") (class "Default")
      (node (ref "C17") (pin "2") (pinfunction "2_2") (pintype "passive"))
      (node (ref "IC11") (pin "11") (pinfunction "A4_11") (pintype "passive"))
      (node (ref "IC6") (pin "8") (pinfunction "OUT_8") (pintype "output"))
      (node (ref "R18") (pin "2") (pinfunction "2_2") (pintype "passive"))
    )
    (net (code "106") (name "Net-(IC13-NR)") (class "Default")
      (node (ref "C75") (pin "1") (pinfunction "1_1") (pintype "passive"))
      (node (ref "IC13") (pin "4") (pinfunction "NR_4") (pintype "bidirectional"))
    )
    (net (code "107") (name "Net-(IC14A-+IN)") (class "Default")
      (node (ref "IC14") (pin "3") (pinfunction "+IN_3") (pintype "input"))
      (node (ref "R35") (pin "2") (pinfunction "2_2") (pintype "passive"))
      (node (ref "R49") (pin "2") (pinfunction "2_2") (pintype "passive"))
    )
    (net (code "108") (name "Net-(IC14A--IN)") (class "Default")
      (node (ref "C40") (pin "1") (pinfunction "1_1") (pintype "passive"))
      (node (ref "IC14") (pin "2") (pinfunction "-IN_2") (pintype "input"))
      (node (ref "R33") (pin "1") (pinfunction "1_1") (pintype "passive"))
      (node (ref "R51") (pin "2") (pinfunction "2_2") (pintype "passive"))
    )
    (net (code "109") (name "Net-(IC14B-+IN)") (class "Default")
      (node (ref "IC14") (pin "5") (pinfunction "+IN_5") (pintype "input"))
      (node (ref "R32") (pin "2") (pinfunction "2_2") (pintype "passive"))
      (node (ref "R48") (pin "2") (pinfunction "2_2") (pintype "passive"))
    )
    (net (code "110") (name "Net-(IC14B--IN)") (class "Default")
      (node (ref "C41") (pin "1") (pinfunction "1_1") (pintype "passive"))
      (node (ref "IC14") (pin "6") (pinfunction "-IN_6") (pintype "input"))
      (node (ref "R34") (pin "1") (pinfunction "1_1") (pintype "passive"))
      (node (ref "R50") (pin "2") (pinfunction "2_2") (pintype "passive"))
    )
    (net (code "111") (name "Net-(LED3-PadA)") (class "Default")
      (node (ref "LED3") (pin "A") (pinfunction "A_A") (pintype "passive"))
      (node (ref "R65") (pin "2") (pinfunction "2_2") (pintype "passive"))
    )
    (net (code "112") (name "Net-(Q1-B)") (class "Default")
      (node (ref "Q1") (pin "1") (pinfunction "B_1") (pintype "bidirectional"))
      (node (ref "R40") (pin "2") (pinfunction "2_2") (pintype "passive"))
    )
    (net (code "113") (name "Net-(Q2-PadB)") (class "Default")
      (node (ref "Q2") (pin "B") (pinfunction "B_B") (pintype "passive"))
      (node (ref "Q4") (pin "C") (pinfunction "C_C") (pintype "passive"))
      (node (ref "R56") (pin "2") (pinfunction "2_2") (pintype "passive"))
      (node (ref "R67") (pin "2") (pinfunction "2_2") (pintype "passive"))
    )
    (net (code "114") (name "Net-(Q2-PadE)") (class "Default")
      (node (ref "Q2") (pin "E") (pinfunction "E_E") (pintype "passive"))
      (node (ref "R68") (pin "2") (pinfunction "2_2") (pintype "passive"))
    )
    (net (code "115") (name "Net-(Q3-B)") (class "Default")
      (node (ref "Q3") (pin "1") (pinfunction "B_1") (pintype "passive"))
      (node (ref "R319") (pin "1") (pinfunction "1_1") (pintype "passive"))
    )
    (net (code "116") (name "Net-(Q3-C)") (class "Default")
      (node (ref "BUZ1") (pin "2") (pinfunction "2_2") (pintype "passive"))
      (node (ref "Q3") (pin "3") (pinfunction "C_3") (pintype "passive"))
    )
    (net (code "117") (name "Net-(Q4-PadB)") (class "Default")
      (node (ref "Q4") (pin "B") (pinfunction "B_B") (pintype "passive"))
      (node (ref "R57") (pin "2") (pinfunction "2_2") (pintype "passive"))
      (node (ref "R58") (pin "2") (pinfunction "2_2") (pintype "passive"))
    )
    (net (code "118") (name "Net-(R37-Pad1)") (class "Default")
      (node (ref "R37") (pin "1") (pinfunction "1_1") (pintype "passive"))
      (node (ref "R38") (pin "2") (pinfunction "2_2") (pintype "passive"))
    )
    (net (code "119") (name "Net-(RLY1A-NC)") (class "Default")
      (node (ref "C14") (pin "1") (pinfunction "1_1") (pintype "passive"))
      (node (ref "R21") (pin "1") (pinfunction "1_1") (pintype "passive"))
      (node (ref "RLY1") (pin "3") (pinfunction "NC_3") (pintype "passive"))
    )
    (net (code "120") (name "Net-(RLY1A-NO)") (class "Default")
      (node (ref "C42") (pin "1") (pinfunction "1_1") (pintype "passive"))
      (node (ref "RLY1") (pin "5") (pinfunction "NO_5") (pintype "passive"))
    )
    (net (code "121") (name "Net-(RLY1B-NO)") (class "Default")
      (node (ref "C43") (pin "1") (pinfunction "1_1") (pintype "passive"))
      (node (ref "RLY1") (pin "8") (pinfunction "NO_8") (pintype "passive"))
    )
    (net (code "122") (name "Net-(SV2-PIN1)") (class "Default")
      (node (ref "R22") (pin "2") (pinfunction "2_2") (pintype "passive"))
      (node (ref "R28") (pin "2") (pinfunction "2_2") (pintype "passive"))
      (node (ref "R46") (pin "2") (pinfunction "2_2") (pintype "passive"))
      (node (ref "SV2") (pin "1") (pinfunction "PIN1_1") (pintype "passive"))
      (node (ref "TP5") (pin "1") (pinfunction "P$1_1") (pintype "bidirectional"))
    )
    (net (code "123") (name "Net-(SV2-PIN3)") (class "Default")
      (node (ref "R27") (pin "2") (pinfunction "2_2") (pintype "passive"))
      (node (ref "R29") (pin "2") (pinfunction "2_2") (pintype "passive"))
      (node (ref "R45") (pin "2") (pinfunction "2_2") (pintype "passive"))
      (node (ref "SV2") (pin "3") (pinfunction "PIN3_3") (pintype "passive"))
      (node (ref "TP4") (pin "1") (pinfunction "P$1_1") (pintype "bidirectional"))
    )
    (net (code "124") (name "Net-(U$7A-TEMP)") (class "Default")
      (node (ref "C60") (pin "1") (pinfunction "1_1") (pintype "passive"))
      (node (ref "R26") (pin "2") (pinfunction "2_2") (pintype "passive"))
      (node (ref "R43") (pin "2") (pinfunction "2_2") (pintype "passive"))
      (node (ref "U$7") (pin "6") (pinfunction "TEMP_6") (pintype "bidirectional"))
    )
    (net (code "125") (name "Net-(U$7A-VREF)") (class "Default")
      (node (ref "R26") (pin "1") (pinfunction "1_1") (pintype "passive"))
      (node (ref "U$7") (pin "7") (pinfunction "VREF_7") (pintype "bidirectional"))
    )
    (net (code "126") (name "Net-(U$7A-~{GRN})") (class "Default")
      (node (ref "R24") (pin "2") (pinfunction "2_2") (pintype "passive"))
      (node (ref "U$7") (pin "2") (pinfunction "~{GRN}_2") (pintype "bidirectional"))
    )
    (net (code "127") (name "Net-(U$7A-~{RED})") (class "Default")
      (node (ref "R25") (pin "2") (pinfunction "2_2") (pintype "passive"))
      (node (ref "U$7") (pin "3") (pinfunction "~{RED}_3") (pintype "bidirectional"))
    )
    (net (code "128") (name "Net-(U1-A)") (class "Default")
      (node (ref "F1") (pin "1") (pinfunction "1_1") (pintype "passive"))
      (node (ref "U1") (pin "1") (pinfunction "A_1") (pintype "bidirectional"))
    )
    (net (code "129") (name "Net-(U2A-L40N_2)") (class "Default")
      (node (ref "R44") (pin "2") (pinfunction "2_2") (pintype "passive"))
      (node (ref "U2") (pin "65") (pinfunction "L40N_2_65") (pintype "bidirectional"))
    )
    (net (code "130") (name "Net-(U2A-L40P_2{slash}VREF_2)") (class "Default")
      (node (ref "R39") (pin "2") (pinfunction "2_2") (pintype "passive"))
      (node (ref "U2") (pin "64") (pinfunction "L40P_2/VREF_2_64") (pintype "bidirectional"))
    )
    (net (code "131") (name "Net-(U3-C1N)") (class "Default")
      (node (ref "C5") (pin "2") (pinfunction "2_2") (pintype "passive"))
      (node (ref "U3") (pin "5") (pinfunction "C1N_5") (pintype "input"))
    )
    (net (code "132") (name "Net-(U3-C1P)") (class "Default")
      (node (ref "C5") (pin "1") (pinfunction "1_1") (pintype "passive"))
      (node (ref "U3") (pin "4") (pinfunction "C1P_4") (pintype "input"))
    )
    (net (code "133") (name "Net-(U3-C2N)") (class "Default")
      (node (ref "C4") (pin "2") (pinfunction "2_2") (pintype "passive"))
      (node (ref "U3") (pin "3") (pinfunction "C2N_3") (pintype "input"))
    )
    (net (code "134") (name "Net-(U3-C2P)") (class "Default")
      (node (ref "C4") (pin "1") (pinfunction "1_1") (pintype "passive"))
      (node (ref "U3") (pin "2") (pinfunction "C2P_2") (pintype "input"))
    )
    (net (code "135") (name "Net-(U3-IREF)") (class "Default")
      (node (ref "R3") (pin "2") (pinfunction "2_2") (pintype "passive"))
      (node (ref "U3") (pin "26") (pinfunction "IREF_26") (pintype "input"))
    )
    (net (code "136") (name "Net-(U3-VCC)") (class "Default")
      (node (ref "C6") (pin "1") (pinfunction "1_1") (pintype "passive"))
      (node (ref "U3") (pin "28") (pinfunction "VCC_28") (pintype "power_in"))
    )
    (net (code "137") (name "Net-(U3-VCOMH)") (class "Default")
      (node (ref "C8") (pin "1") (pinfunction "1_1") (pintype "passive"))
      (node (ref "U3") (pin "27") (pinfunction "VCOMH_27") (pintype "output"))
    )
    (net (code "138") (name "Net-(Y1-2)") (class "Default")
      (node (ref "C54") (pin "2") (pinfunction "2_2") (pintype "passive"))
      (node (ref "R6") (pin "1") (pinfunction "1_1") (pintype "passive"))
      (node (ref "Y1") (pin "P$2") (pinfunction "2_P$2") (pintype "passive"))
    )
    (net (code "139") (name "ONOFF") (class "Default")
      (node (ref "IC1") (pin "6") (pinfunction "EN_6") (pintype "input"))
      (node (ref "S1") (pin "2") (pinfunction "P_2") (pintype "passive"))
    )
    (net (code "140") (name "PCK0") (class "Default")
      (node (ref "IC2") (pin "43") (pinfunction "PA10/USART1_RX/TIM1_CH3/FT_43") (pintype "bidirectional"))
      (node (ref "PCK0_TP") (pin "1") (pinfunction "P$1_1") (pintype "bidirectional"))
      (node (ref "U2") (pin "88") (pinfunction "L32N_1/GCLK5_88") (pintype "bidirectional"))
    )
    (net (code "141") (name "PS") (class "Default")
      (node (ref "IC1") (pin "8") (pinfunction "PS_8") (pintype "input"))
      (node (ref "JP2") (pin "2") (pinfunction "2_2") (pintype "passive"))
    )
    (net (code "142") (name "PWR_HI") (class "Default")
      (node (ref "IC10") (pin "13") (pinfunction "2A2_13") (pintype "bidirectional"))
      (node (ref "IC10") (pin "15") (pinfunction "2A3_15") (pintype "bidirectional"))
      (node (ref "IC10") (pin "17") (pinfunction "2A4_17") (pintype "bidirectional"))
      (node (ref "IC9") (pin "11") (pinfunction "2A1_11") (pintype "bidirectional"))
      (node (ref "IC9") (pin "2") (pinfunction "1A1_2") (pintype "bidirectional"))
      (node (ref "IC9") (pin "4") (pinfunction "1A2_4") (pintype "bidirectional"))
      (node (ref "IC9") (pin "6") (pinfunction "1A3_6") (pintype "bidirectional"))
      (node (ref "IC9") (pin "8") (pinfunction "1A4_8") (pintype "bidirectional"))
      (node (ref "PWR_HI_TP") (pin "1") (pinfunction "P$1_1") (pintype "bidirectional"))
      (node (ref "U2") (pin "61") (pinfunction "L24N_3_61") (pintype "bidirectional"))
    )
    (net (code "143") (name "PWR_LO") (class "Default")
      (node (ref "IC10") (pin "11") (pinfunction "2A1_11") (pintype "bidirectional"))
      (node (ref "IC10") (pin "2") (pinfunction "1A1_2") (pintype "bidirectional"))
      (node (ref "IC10") (pin "4") (pinfunction "1A2_4") (pintype "bidirectional"))
      (node (ref "IC10") (pin "6") (pinfunction "1A3_6") (pintype "bidirectional"))
      (node (ref "IC10") (pin "8") (pinfunction "1A4_8") (pintype "bidirectional"))
      (node (ref "IC9") (pin "13") (pinfunction "2A2_13") (pintype "bidirectional"))
      (node (ref "IC9") (pin "15") (pinfunction "2A3_15") (pintype "bidirectional"))
      (node (ref "IC9") (pin "17") (pinfunction "2A4_17") (pintype "bidirectional"))
      (node (ref "PWR_LO_TP") (pin "1") (pinfunction "P$1_1") (pintype "bidirectional"))
      (node (ref "U2") (pin "62") (pinfunction "L40P_3_62") (pintype "bidirectional"))
    )
    (net (code "144") (name "PWR_OE1") (class "Default")
      (node (ref "IC9") (pin "1") (pinfunction "1NOE_1") (pintype "bidirectional"))
      (node (ref "OE1_TP") (pin "1") (pinfunction "P$1_1") (pintype "bidirectional"))
      (node (ref "U2") (pin "44") (pinfunction "L30N_4/D2_44") (pintype "bidirectional"))
    )
    (net (code "145") (name "PWR_OE2") (class "Default")
      (node (ref "IC10") (pin "1") (pinfunction "1NOE_1") (pintype "bidirectional"))
      (node (ref "OE2_TP") (pin "1") (pinfunction "P$1_1") (pintype "bidirectional"))
      (node (ref "U2") (pin "47") (pinfunction "L27P_4/D1_47") (pintype "bidirectional"))
    )
    (net (code "146") (name "PWR_OE3") (class "Default")
      (node (ref "IC9") (pin "19") (pinfunction "2NOE_19") (pintype "bidirectional"))
      (node (ref "OE3_TP") (pin "1") (pinfunction "P$1_1") (pintype "bidirectional"))
      (node (ref "U2") (pin "71") (pinfunction "L21P_2_71") (pintype "bidirectional"))
    )
    (net (code "147") (name "PWR_OE4") (class "Default")
      (node (ref "IC10") (pin "19") (pinfunction "2NOE_19") (pintype "bidirectional"))
      (node (ref "OE4_TP") (pin "1") (pinfunction "P$1_1") (pintype "bidirectional"))
      (node (ref "U2") (pin "72") (pinfunction "L21N_2_72") (pintype "bidirectional"))
    )
    (net (code "148") (name "RELAY_ON") (class "Default")
      (node (ref "IC2") (pin "25") (pinfunction "PC5/ADC12_IN15_25") (pintype "bidirectional"))
      (node (ref "R40") (pin "1") (pinfunction "1_1") (pintype "passive"))
      (node (ref "RELAY_ON_TP") (pin "1") (pinfunction "P$1_1") (pintype "bidirectional"))
    )
    (net (code "149") (name "SCLK{slash}DB0") (class "Default")
      (node (ref "IC2") (pin "21") (pinfunction "PA5/SPI1_SCK/DAC_OUT2/ADC12_IN5_21") (pintype "bidirectional"))
      (node (ref "TP54") (pin "1") (pinfunction "P$1_1") (pintype "bidirectional"))
      (node (ref "U3") (pin "18") (pinfunction "D0/SPI_SCLK/I2C_SCK_18") (pintype "bidirectional"))
    )
    (net (code "150") (name "SDIN{slash}DB1") (class "Default")
      (node (ref "IC2") (pin "22") (pinfunction "PA6/SPI1_MISO/TIM8_BKIN/ADC12_IN6/TIM3_CH1/TIM1_BKIN_22") (pintype "bidirectional"))
      (node (ref "SJ1") (pin "1") (pinfunction "1_1") (pintype "passive"))
      (node (ref "TP55") (pin "1") (pinfunction "P$1_1") (pintype "bidirectional"))
      (node (ref "U3") (pin "19") (pinfunction "D1/SPI_SDIN/I2C_SDA_19") (pintype "bidirectional"))
    )
    (net (code "151") (name "SD_MISO") (class "Default")
      (node (ref "IC2") (pin "56") (pinfunction "PB4/JNTRST/SPI3_MISO/TIM3_CH1/SPI1_MISO_56") (pintype "input"))
      (node (ref "R62") (pin "1") (pinfunction "1_1") (pintype "passive"))
      (node (ref "TP11") (pin "1") (pinfunction "P$1_1") (pintype "bidirectional"))
      (node (ref "U4") (pin "7") (pinfunction "DO_7") (pintype "bidirectional"))
    )
    (net (code "152") (name "SD_MOSI") (class "Default")
      (node (ref "IC2") (pin "57") (pinfunction "PB5/I2C1_SMBA/SPI3_MOSI/I2S3_SD/TIM3_CH2/SPI1_MOSI_57") (pintype "bidirectional"))
      (node (ref "R63") (pin "1") (pinfunction "1_1") (pintype "passive"))
      (node (ref "TP32") (pin "1") (pinfunction "P$1_1") (pintype "bidirectional"))
      (node (ref "U4") (pin "3") (pinfunction "DI_3") (pintype "bidirectional"))
    )
    (net (code "153") (name "SD_RSV") (class "Default")
      (node (ref "R61") (pin "1") (pinfunction "1_1") (pintype "passive"))
      (node (ref "U4") (pin "8") (pinfunction "RSV_8") (pintype "bidirectional"))
    )
    (net (code "154") (name "SD_SCK{slash}TDO") (class "Default")
      (node (ref "IC2") (pin "55") (pinfunction "PB3/JTDO/SPI3_SCK/I2S3_CK/TIM2_CH2/SPI1_SCK/TRACESWO_55") (pintype "output"))
      (node (ref "JP4") (pin "3") (pinfunction "3_3") (pintype "passive"))
      (node (ref "TP6") (pin "1") (pinfunction "P$1_1") (pintype "bidirectional"))
      (node (ref "U4") (pin "5") (pinfunction "SCK_5") (pintype "bidirectional"))
    )
    (net (code "155") (name "SPCK") (class "Default")
      (node (ref "IC2") (pin "2") (pinfunction "PC13/TAMPER-RTC_2") (pintype "bidirectional"))
      (node (ref "SPCK_TP") (pin "1") (pinfunction "P$1_1") (pintype "bidirectional"))
      (node (ref "U2") (pin "1") (pinfunction "L01P_7/VRN_7_1") (pintype "bidirectional"))
    )
    (net (code "156") (name "SPEAKER") (class "Default")
      (node (ref "IC2") (pin "37") (pinfunction "PC6/I2S2_MCK/TIM8_CH1/SDIO_D6/TIM3_CH1/FT_37") (pintype "bidirectional"))
      (node (ref "R319") (pin "2") (pinfunction "2_2") (pintype "passive"))
    )
    (net (code "157") (name "SSP_CLK") (class "Default")
      (node (ref "IC2") (pin "34") (pinfunction "PB13/SPI2_SCK/I2S2_CK/USART3_CTS/TIM1_CH1N/FT_34") (pintype "bidirectional"))
      (node (ref "TP50") (pin "1") (pinfunction "P$1_1") (pintype "bidirectional"))
      (node (ref "U2") (pin "9") (pinfunction "L23N_7_9") (pintype "bidirectional"))
    )
    (net (code "158") (name "SSP_MISO") (class "Default")
      (node (ref "IC2") (pin "35") (pinfunction "PB14/SPI2_MISO/TIM1_CH2N/USART3_RTS/FT_35") (pintype "bidirectional"))
      (node (ref "TP49") (pin "1") (pinfunction "P$1_1") (pintype "bidirectional"))
      (node (ref "U2") (pin "8") (pinfunction "L23P_7_8") (pintype "bidirectional"))
    )
    (net (code "159") (name "SSP_MOSI") (class "Default")
      (node (ref "IC2") (pin "36") (pinfunction "PB15/SPI2_MOSI/TIM1_CH3N/I2S2_SD/FT_36") (pintype "bidirectional"))
      (node (ref "TP48") (pin "1") (pinfunction "P$1_1") (pintype "bidirectional"))
      (node (ref "U2") (pin "5") (pinfunction "L21N_7_5") (pintype "bidirectional"))
    )
    (net (code "160") (name "SSP_NSS") (class "Default")
      (node (ref "IC2") (pin "33") (pinfunction "PB12/SPI2_NSS/I2C2_WS/I2C2_SMBA/USART3_CK/TIM1_BKIN/FT_33") (pintype "bidirectional"))
      (node (ref "TP51") (pin "1") (pinfunction "P$1_1") (pintype "bidirectional"))
      (node (ref "U2") (pin "4") (pinfunction "L21P_7_4") (pintype "bidirectional"))
    )
    (net (code "161") (name "SW_K1") (class "Default")
      (node (ref "IC2") (pin "62") (pinfunction "PB9/TIM4_CH4/SDIO_D5/I2C1_SDA/CAN_TX/FT_62") (pintype "bidirectional"))
      (node (ref "K1") (pin "2") (pinfunction "S_2") (pintype "passive"))
      (node (ref "R71") (pin "1") (pinfunction "1_1") (pintype "passive"))
    )
    (net (code "162") (name "SW_K2") (class "Default")
      (node (ref "IC2") (pin "17") (pinfunction "PA3/USART2_RX/TIM5_CH4/ADC123_IN3/TIM2_CH4_17") (pintype "bidirectional"))
      (node (ref "K2") (pin "2") (pinfunction "S_2") (pintype "passive"))
      (node (ref "R70") (pin "1") (pinfunction "1_1") (pintype "passive"))
    )
    (net (code "163") (name "SW_K3") (class "Default")
      (node (ref "IC2") (pin "16") (pinfunction "PA2/USART2_TX/TIM5_CH3/ADC123_IN2/TIM2_CH3_16") (pintype "bidirectional"))
      (node (ref "K3") (pin "2") (pinfunction "S_2") (pintype "passive"))
      (node (ref "R69") (pin "1") (pinfunction "1_1") (pintype "passive"))
    )
    (net (code "164") (name "USBD_N") (class "Default")
      (node (ref "D6") (pin "2") (pinfunction "P$2_2") (pintype "passive"))
      (node (ref "R7") (pin "1") (pinfunction "1_1") (pintype "passive"))
      (node (ref "SV1") (pin "2") (pinfunction "D-/2_2") (pintype "bidirectional"))
      (node (ref "USB-MICRO") (pin "D-") (pinfunction "D-_D-") (pintype "bidirectional"))
    )
    (net (code "165") (name "USBD_P") (class "Default")
      (node (ref "D6") (pin "3") (pinfunction "P$3_3") (pintype "passive"))
      (node (ref "R68") (pin "1") (pinfunction "1_1") (pintype "passive"))
      (node (ref "R8") (pin "1") (pinfunction "1_1") (pintype "passive"))
      (node (ref "SV1") (pin "3") (pinfunction "D+/3_3") (pintype "bidirectional"))
      (node (ref "USB-MICRO") (pin "D+") (pinfunction "D+_D+") (pintype "bidirectional"))
    )
    (net (code "166") (name "USB_ON") (class "Default")
      (node (ref "IC2") (pin "29") (pinfunction "PB10/I2C2_SCL/USART3_TX/TIM2_CH3/FT_29") (pintype "bidirectional"))
      (node (ref "R58") (pin "1") (pinfunction "1_1") (pintype "passive"))
      (node (ref "TP23") (pin "1") (pinfunction "P$1_1") (pintype "bidirectional"))
    )
    (net (code "167") (name "VBAT+") (class "Default")
      (node (ref "C61") (pin "1") (pinfunction "1_1") (pintype "passive"))
      (node (ref "C62") (pin "1") (pinfunction "1_1") (pintype "passive"))
      (node (ref "IC1") (pin "5") (pinfunction "VIN_5") (pintype "input"))
      (node (ref "JP2") (pin "3") (pinfunction "3_3") (pintype "passive"))
      (node (ref "L2") (pin "P$1") (pinfunction "1_P$1") (pintype "passive"))
      (node (ref "R55") (pin "2") (pinfunction "2_2") (pintype "passive"))
      (node (ref "S1") (pin "3") (pinfunction "S_3") (pintype "passive"))
      (node (ref "TP9") (pin "1") (pinfunction "P$1_1") (pintype "bidirectional"))
      (node (ref "U$7") (pin "8") (pinfunction "BAT_8") (pintype "bidirectional"))
      (node (ref "U$9") (pin "3") (pinfunction "POS_3") (pintype "power_in"))
    )
    (net (code "168") (name "VBUS") (class "Default")
      (node (ref "C1") (pin "1") (pinfunction "1_1") (pintype "passive"))
      (node (ref "C59") (pin "1") (pinfunction "1_1") (pintype "passive"))
      (node (ref "LED1") (pin "A") (pinfunction "A_A") (pintype "passive"))
      (node (ref "LED2") (pin "A") (pinfunction "A_A") (pintype "passive"))
      (node (ref "R56") (pin "1") (pinfunction "1_1") (pintype "passive"))
      (node (ref "TP8") (pin "1") (pinfunction "P$1_1") (pintype "bidirectional"))
      (node (ref "U$7") (pin "1") (pinfunction "VIN_1") (pintype "bidirectional"))
      (node (ref "U1") (pin "2") (pinfunction "B_2") (pintype "bidirectional"))
    )
    (net (code "169") (name "VDDA") (class "Default")
      (node (ref "C52") (pin "1") (pinfunction "1_1") (pintype "passive"))
      (node (ref "C55") (pin "A") (pinfunction "+_A") (pintype "passive"))
      (node (ref "IC2") (pin "13") (pinfunction "VDDA_13") (pintype "power_in"))
      (node (ref "L1") (pin "2") (pinfunction "P$2_2") (pintype "bidirectional"))
    )
    (net (code "170") (name "VMID") (class "Default")
      (node (ref "C10") (pin "1") (pinfunction "1_1") (pintype "passive"))
      (node (ref "C45") (pin "1") (pinfunction "1_1") (pintype "passive"))
      (node (ref "IC6") (pin "1") (pinfunction "OUT_1") (pintype "output"))
      (node (ref "IC6") (pin "2") (pinfunction "-IN_2") (pintype "input"))
      (node (ref "R12") (pin "1") (pinfunction "1_1") (pintype "passive"))
      (node (ref "R13") (pin "1") (pinfunction "1_1") (pintype "passive"))
      (node (ref "R17") (pin "1") (pinfunction "1_1") (pintype "passive"))
      (node (ref "R19") (pin "1") (pinfunction "1_1") (pintype "passive"))
      (node (ref "R36") (pin "1") (pinfunction "1_1") (pintype "passive"))
      (node (ref "R38") (pin "1") (pinfunction "1_1") (pintype "passive"))
      (node (ref "R48") (pin "1") (pinfunction "1_1") (pintype "passive"))
      (node (ref "R49") (pin "1") (pinfunction "1_1") (pintype "passive"))
      (node (ref "R50") (pin "1") (pinfunction "1_1") (pintype "passive"))
      (node (ref "R51") (pin "1") (pinfunction "1_1") (pintype "passive"))
    )
    (net (code "171") (name "unconnected-(IC2-PC0{slash}ADC123_IN10-Pad8)") (class "Default")
      (node (ref "IC2") (pin "8") (pinfunction "PC0/ADC123_IN10_8") (pintype "bidirectional"))
    )
    (net (code "172") (name "unconnected-(IC2-PC1{slash}ADC123_IN11-Pad9)") (class "Default")
      (node (ref "IC2") (pin "9") (pinfunction "PC1/ADC123_IN11_9") (pintype "bidirectional"))
    )
    (net (code "173") (name "unconnected-(IC2-PC2{slash}ADC123_IN12-Pad10)") (class "Default")
      (node (ref "IC2") (pin "10") (pinfunction "PC2/ADC123_IN12_10") (pintype "bidirectional"))
    )
    (net (code "174") (name "unconnected-(IC2-PC10{slash}UART4_TX{slash}SDIO_D2{slash}USART3_TX{slash}FT-Pad51)") (class "Default")
      (node (ref "IC2") (pin "51") (pinfunction "PC10/UART4_TX/SDIO_D2/USART3_TX/FT_51") (pintype "bidirectional"))
    )
    (net (code "175") (name "unconnected-(IC6D-OUT-Pad14)") (class "Default")
      (node (ref "IC6") (pin "14") (pinfunction "OUT_14") (pintype "output"))
    )
    (net (code "176") (name "unconnected-(IC8-REFBS-Pad22)") (class "Default")
      (node (ref "IC8") (pin "22") (pinfunction "REFBS_22") (pintype "bidirectional"))
    )
    (net (code "177") (name "unconnected-(IC8-REFTS-Pad16)") (class "Default")
      (node (ref "IC8") (pin "16") (pinfunction "REFTS_16") (pintype "bidirectional"))
    )
    (net (code "178") (name "unconnected-(IC105-NR-Pad4)") (class "Default")
      (node (ref "IC105") (pin "4") (pinfunction "NR_4") (pintype "bidirectional"))
    )
    (net (code "179") (name "unconnected-(IC106-NR-Pad4)") (class "Default")
      (node (ref "IC106") (pin "4") (pinfunction "NR_4") (pintype "bidirectional"))
    )
    (net (code "180") (name "unconnected-(SV1-ID{slash}4-Pad4)") (class "Default")
      (node (ref "SV1") (pin "4") (pinfunction "ID/4_4") (pintype "bidirectional"))
    )
    (net (code "181") (name "unconnected-(U2A-IO0_3-Pad55)") (class "Default")
      (node (ref "U2") (pin "55") (pinfunction "IO0_3_55") (pintype "bidirectional"))
    )
    (net (code "182") (name "unconnected-(U2A-IO0_6-Pad17)") (class "Default")
      (node (ref "U2") (pin "17") (pinfunction "IO0_6_17") (pintype "bidirectional"))
    )
    (net (code "183") (name "unconnected-(U2A-IO1_3-Pad59)") (class "Default")
      (node (ref "U2") (pin "59") (pinfunction "IO1_3_59") (pintype "bidirectional"))
    )
    (net (code "184") (name "unconnected-(U2A-IO1_6-Pad21)") (class "Default")
      (node (ref "U2") (pin "21") (pinfunction "IO1_6_21") (pintype "bidirectional"))
    )
    (net (code "185") (name "unconnected-(U2A-IO_1-Pad81)") (class "Default")
      (node (ref "U2") (pin "81") (pinfunction "IO_1_81") (pintype "bidirectional"))
    )
    (net (code "186") (name "unconnected-(U2A-L01N_0{slash}VRP_0-Pad97)") (class "Default")
      (node (ref "U2") (pin "97") (pinfunction "L01N_0/VRP_0_97") (pintype "bidirectional"))
    )
    (net (code "187") (name "unconnected-(U2A-L01N_1{slash}VRP_1-Pad80)") (class "Default")
      (node (ref "U2") (pin "80") (pinfunction "L01N_1/VRP_1_80") (pintype "bidirectional"))
    )
    (net (code "188") (name "unconnected-(U2A-L01N_3{slash}VRP_3-Pad54)") (class "Default")
      (node (ref "U2") (pin "54") (pinfunction "L01N_3/VRP_3_54") (pintype "bidirectional"))
    )
    (net (code "189") (name "unconnected-(U2A-L01N_6{slash}VRP_6-Pad23)") (class "Default")
      (node (ref "U2") (pin "23") (pinfunction "L01N_6/VRP_6_23") (pintype "bidirectional"))
    )
    (net (code "190") (name "unconnected-(U2A-L01N_7{slash}VRP_7-Pad2)") (class "Default")
      (node (ref "U2") (pin "2") (pinfunction "L01N_7/VRP_7_2") (pintype "bidirectional"))
    )
    (net (code "191") (name "unconnected-(U2A-L01P_0{slash}VRN_0-Pad96)") (class "Default")
      (node (ref "U2") (pin "96") (pinfunction "L01P_0/VRN_0_96") (pintype "bidirectional"))
    )
    (net (code "192") (name "unconnected-(U2A-L01P_1{slash}VRN_1-Pad79)") (class "Default")
      (node (ref "U2") (pin "79") (pinfunction "L01P_1/VRN_1_79") (pintype "bidirectional"))
    )
    (net (code "193") (name "unconnected-(U2A-L01P_2{slash}VRN_2-Pad74)") (class "Default")
      (node (ref "U2") (pin "74") (pinfunction "L01P_2/VRN_2_74") (pintype "bidirectional"))
    )
    (net (code "194") (name "unconnected-(U2A-L01P_3{slash}VRN_3-Pad53)") (class "Default")
      (node (ref "U2") (pin "53") (pinfunction "L01P_3/VRN_3_53") (pintype "bidirectional"))
    )
    (net (code "195") (name "unconnected-(U2A-L01P_6{slash}VRN_6-Pad22)") (class "Default")
      (node (ref "U2") (pin "22") (pinfunction "L01P_6/VRN_6_22") (pintype "bidirectional"))
    )
    (net (code "196") (name "unconnected-(U2A-L24N_2-Pad68)") (class "Default")
      (node (ref "U2") (pin "68") (pinfunction "L24N_2_68") (pintype "bidirectional"))
    )
    (net (code "197") (name "unconnected-(U2A-L24N_6{slash}VREF_6-Pad16)") (class "Default")
      (node (ref "U2") (pin "16") (pinfunction "L24N_6/VREF_6_16") (pintype "bidirectional"))
    )
    (net (code "198") (name "unconnected-(U2A-L24P_2-Pad67)") (class "Default")
      (node (ref "U2") (pin "67") (pinfunction "L24P_2_67") (pintype "bidirectional"))
    )
    (net (code "199") (name "unconnected-(U2A-L24P_3-Pad60)") (class "Default")
      (node (ref "U2") (pin "60") (pinfunction "L24P_3_60") (pintype "bidirectional"))
    )
    (net (code "200") (name "unconnected-(U2A-L31N_0-Pad92)") (class "Default")
      (node (ref "U2") (pin "92") (pinfunction "L31N_0_92") (pintype "bidirectional"))
    )
    (net (code "201") (name "unconnected-(U2A-L31N_1{slash}VREF_1-Pad86)") (class "Default")
      (node (ref "U2") (pin "86") (pinfunction "L31N_1/VREF_1_86") (pintype "bidirectional"))
    )
    (net (code "202") (name "unconnected-(U2A-L31P_0{slash}VREF_0-Pad91)") (class "Default")
      (node (ref "U2") (pin "91") (pinfunction "L31P_0/VREF_0_91") (pintype "bidirectional"))
    )
    (net (code "203") (name "unconnected-(U2A-L31P_1-Pad85)") (class "Default")
      (node (ref "U2") (pin "85") (pinfunction "L31P_1_85") (pintype "bidirectional"))
    )
    (net (code "204") (name "unconnected-(U2A-L32N_4{slash}GCLK1-Pad39)") (class "Default")
      (node (ref "U2") (pin "39") (pinfunction "L32N_4/GCLK1_39") (pintype "bidirectional"))
    )
    (net (code "205") (name "unconnected-(U2A-L32P_1{slash}GCLK4-Pad87)") (class "Default")
      (node (ref "U2") (pin "87") (pinfunction "L32P_1/GCLK4_87") (pintype "bidirectional"))
    )
    (net (code "206") (name "unconnected-(U2A-L40N_3{slash}VREF_3-Pad63)") (class "Default")
      (node (ref "U2") (pin "63") (pinfunction "L40N_3/VREF_3_63") (pintype "bidirectional"))
    )
    (net (code "207") (name "unconnected-(U2A-L40N_7{slash}VREF_7-Pad12)") (class "Default")
      (node (ref "U2") (pin "12") (pinfunction "L40N_7/VREF_7_12") (pintype "bidirectional"))
    )
    (net (code "208") (name "unconnected-(U2A-L40P_6{slash}VREF_6-Pad13)") (class "Default")
      (node (ref "U2") (pin "13") (pinfunction "L40P_6/VREF_6_13") (pintype "bidirectional"))
    )
    (net (code "209") (name "unconnected-(U2A-L40P_7-Pad11)") (class "Default")
      (node (ref "U2") (pin "11") (pinfunction "L40P_7_11") (pintype "bidirectional"))
    )
    (net (code "210") (name "unconnected-(U2B-HSWAP_EN-Pad98)") (class "Default")
      (node (ref "U2") (pin "98") (pinfunction "HSWAP_EN_98") (pintype "bidirectional"))
    )
    (net (code "211") (name "unconnected-(U2B-M0-Pad25)") (class "Default")
      (node (ref "U2") (pin "25") (pinfunction "M0_25") (pintype "bidirectional"))
    )
    (net (code "212") (name "unconnected-(U2B-M1-Pad24)") (class "Default")
      (node (ref "U2") (pin "24") (pinfunction "M1_24") (pintype "bidirectional"))
    )
    (net (code "213") (name "unconnected-(U2B-M2-Pad26)") (class "Default")
      (node (ref "U2") (pin "26") (pinfunction "M2_26") (pintype "bidirectional"))
    )
    (net (code "214") (name "unconnected-(U3-D3-Pad21)") (class "Default")
      (node (ref "U3") (pin "21") (pinfunction "D3_21") (pintype "bidirectional"))
    )
    (net (code "215") (name "unconnected-(U3-D4-Pad22)") (class "Default")
      (node (ref "U3") (pin "22") (pinfunction "D4_22") (pintype "bidirectional"))
    )
    (net (code "216") (name "unconnected-(U3-D5-Pad23)") (class "Default")
      (node (ref "U3") (pin "23") (pinfunction "D5_23") (pintype "bidirectional"))
    )
    (net (code "217") (name "unconnected-(U3-D6-Pad24)") (class "Default")
      (node (ref "U3") (pin "24") (pinfunction "D6_24") (pintype "bidirectional"))
    )
    (net (code "218") (name "unconnected-(U3-D7-Pad25)") (class "Default")
      (node (ref "U3") (pin "25") (pinfunction "D7_25") (pintype "bidirectional"))
    )
    (net (code "219") (name "unconnected-(U3-E{slash}RD-Pad17)") (class "Default")
      (node (ref "U3") (pin "17") (pinfunction "E/RD_17") (pintype "input"))
    )
    (net (code "220") (name "unconnected-(U3-NC-Pad7)") (class "Default")
      (node (ref "U3") (pin "7") (pinfunction "NC_7") (pintype "no_connect"))
    )
    (net (code "221") (name "unconnected-(U3-R{slash}W-Pad16)") (class "Default")
      (node (ref "U3") (pin "16") (pinfunction "R/W_16") (pintype "input"))
    )
    (net (code "222") (name "unconnected-(U4-NC-Pad1)") (class "Default")
      (node (ref "U4") (pin "1") (pinfunction "NC_1") (pintype "bidirectional"))
    )
    (net (code "223") (name "~{OLED_CS}") (class "Default")
      (node (ref "IC2") (pin "20") (pinfunction "PA4/SPI1_NSS/USART2_CK/DAC_OUT1/ADC12_IN4_20") (pintype "bidirectional"))
      (node (ref "TP28") (pin "1") (pinfunction "P$1_1") (pintype "bidirectional"))
      (node (ref "U3") (pin "13") (pinfunction "/CS_13") (pintype "input"))
    )
    (net (code "224") (name "~{RES}") (class "Default")
      (node (ref "IC2") (pin "61") (pinfunction "PB8/TIM4_CH3/SDIO_D4/I2C1_SCL/CAN_RX/FT_61") (pintype "bidirectional"))
      (node (ref "TP29") (pin "1") (pinfunction "P$1_1") (pintype "bidirectional"))
      (node (ref "U3") (pin "14") (pinfunction "/RES_14") (pintype "input"))
    )
    (net (code "225") (name "~{SD_CS{slash}JTAG_TDI}") (class "Default")
      (node (ref "IC2") (pin "50") (pinfunction "PA15/JTDI/SPI3_NSS/I2S3_WS/TIM2_CH1_ETR/SPI1_NSS_50") (pintype "input"))
      (node (ref "JP4") (pin "2") (pinfunction "2_2") (pintype "passive"))
      (node (ref "R64") (pin "1") (pinfunction "1_1") (pintype "passive"))
      (node (ref "U4") (pin "2") (pinfunction "CS_2") (pintype "bidirectional"))
    )
  )
)
